# Controller.net
KiCad netlist of a schematic drawn in Altium Designer
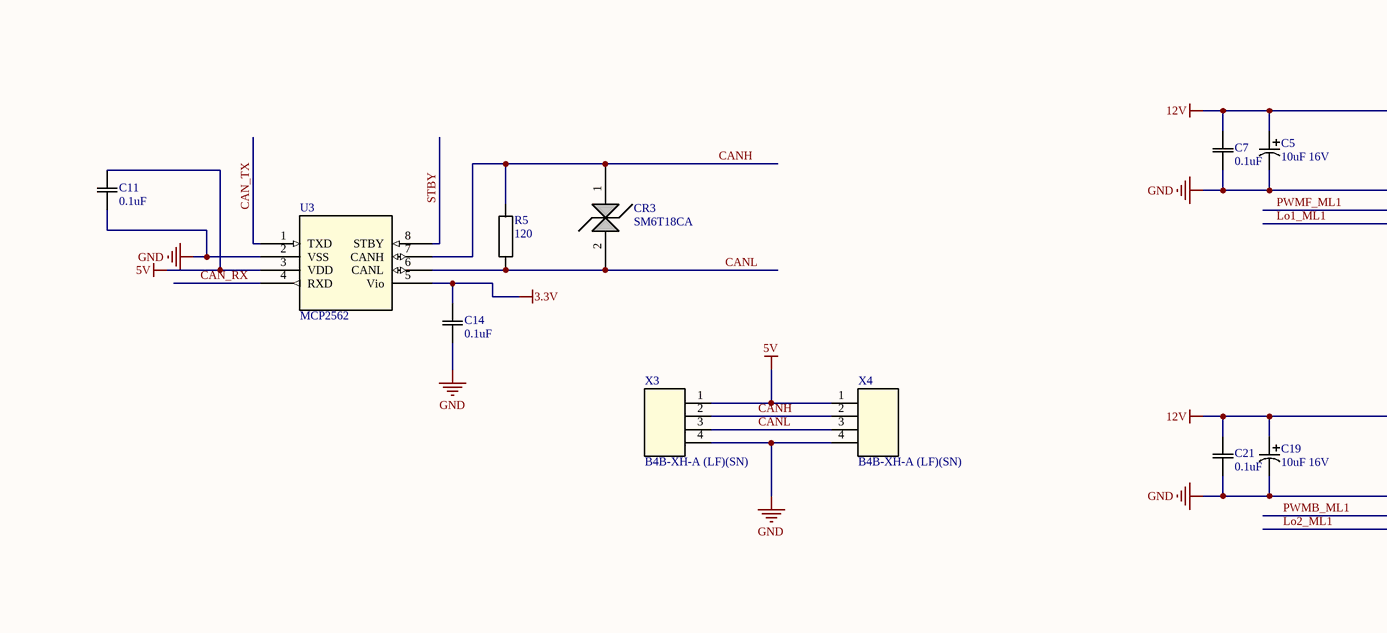
[diagram p0: Controller.SchDoc, top left]
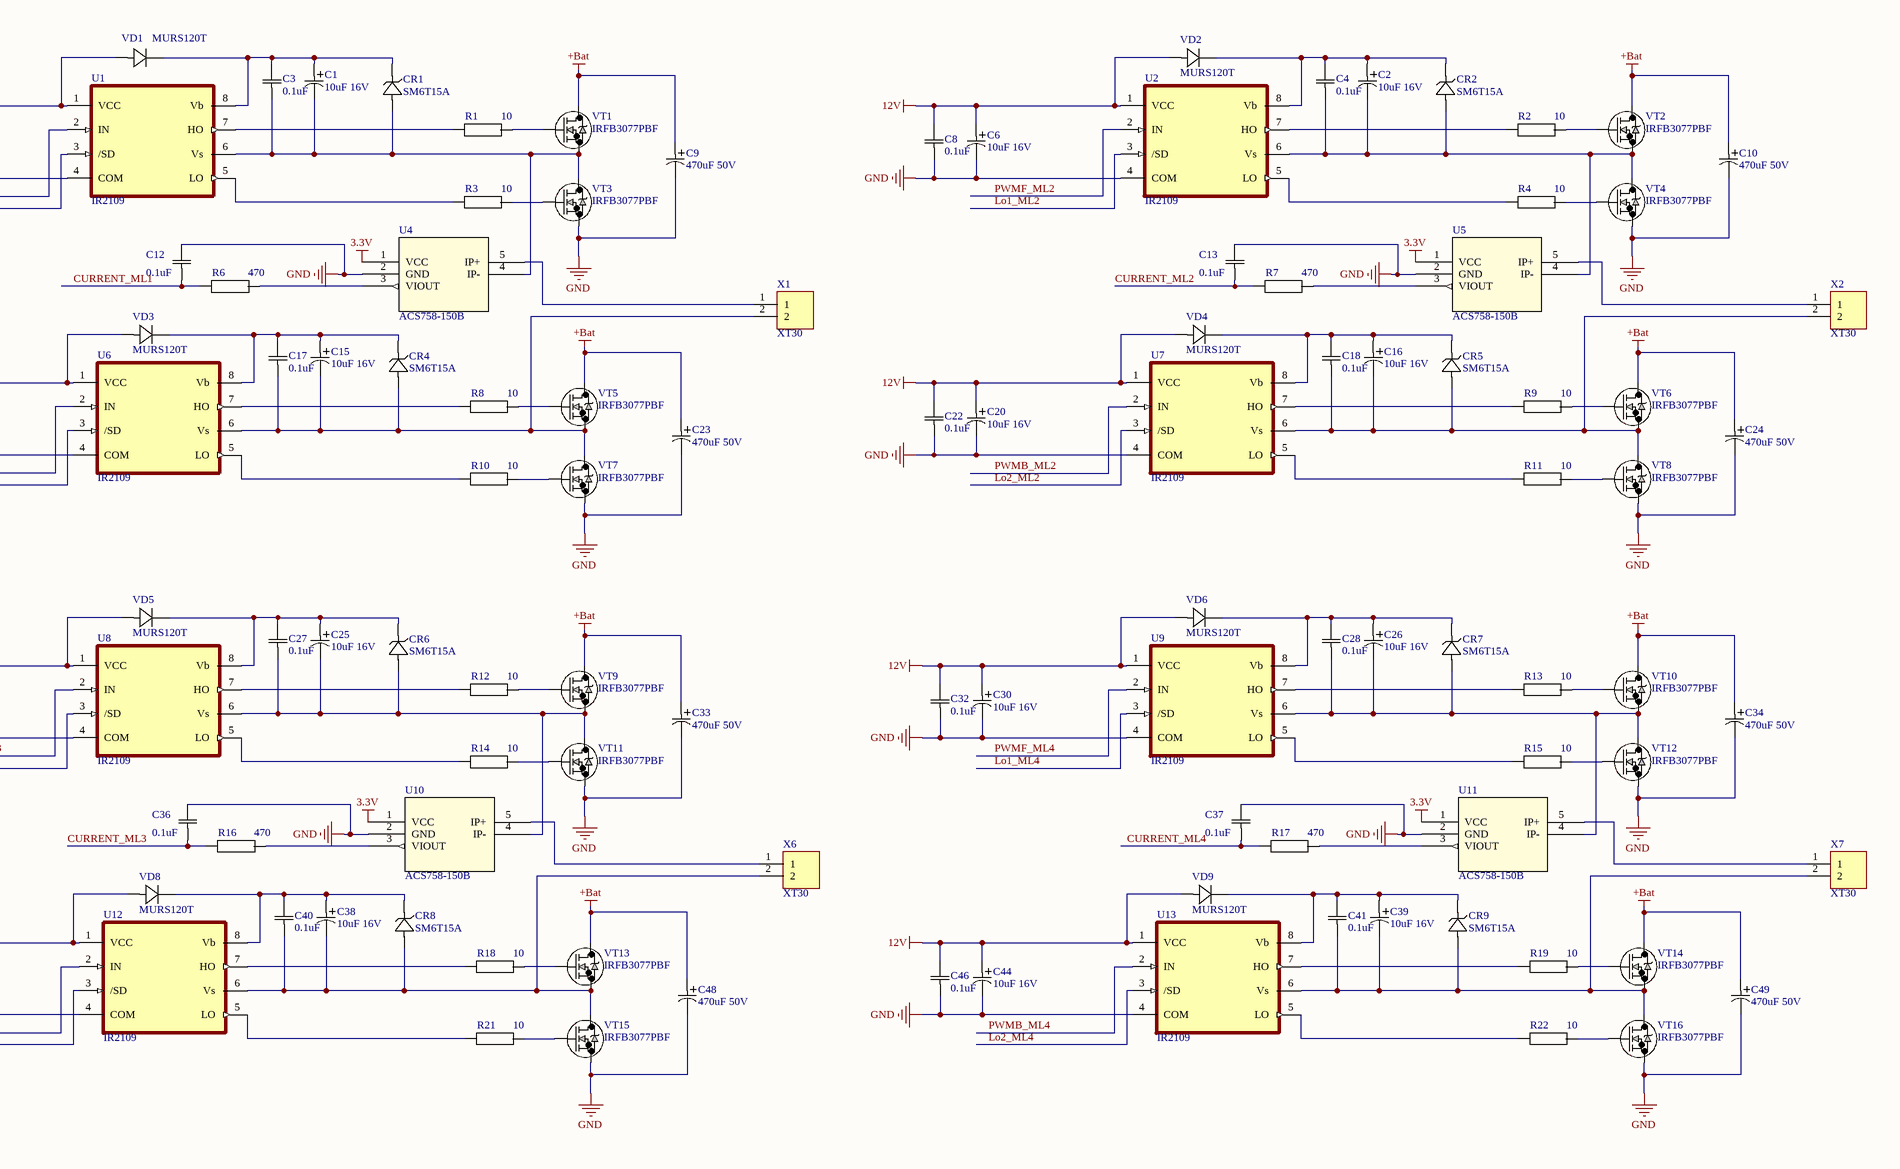
[diagram p1: Controller.SchDoc, top right]
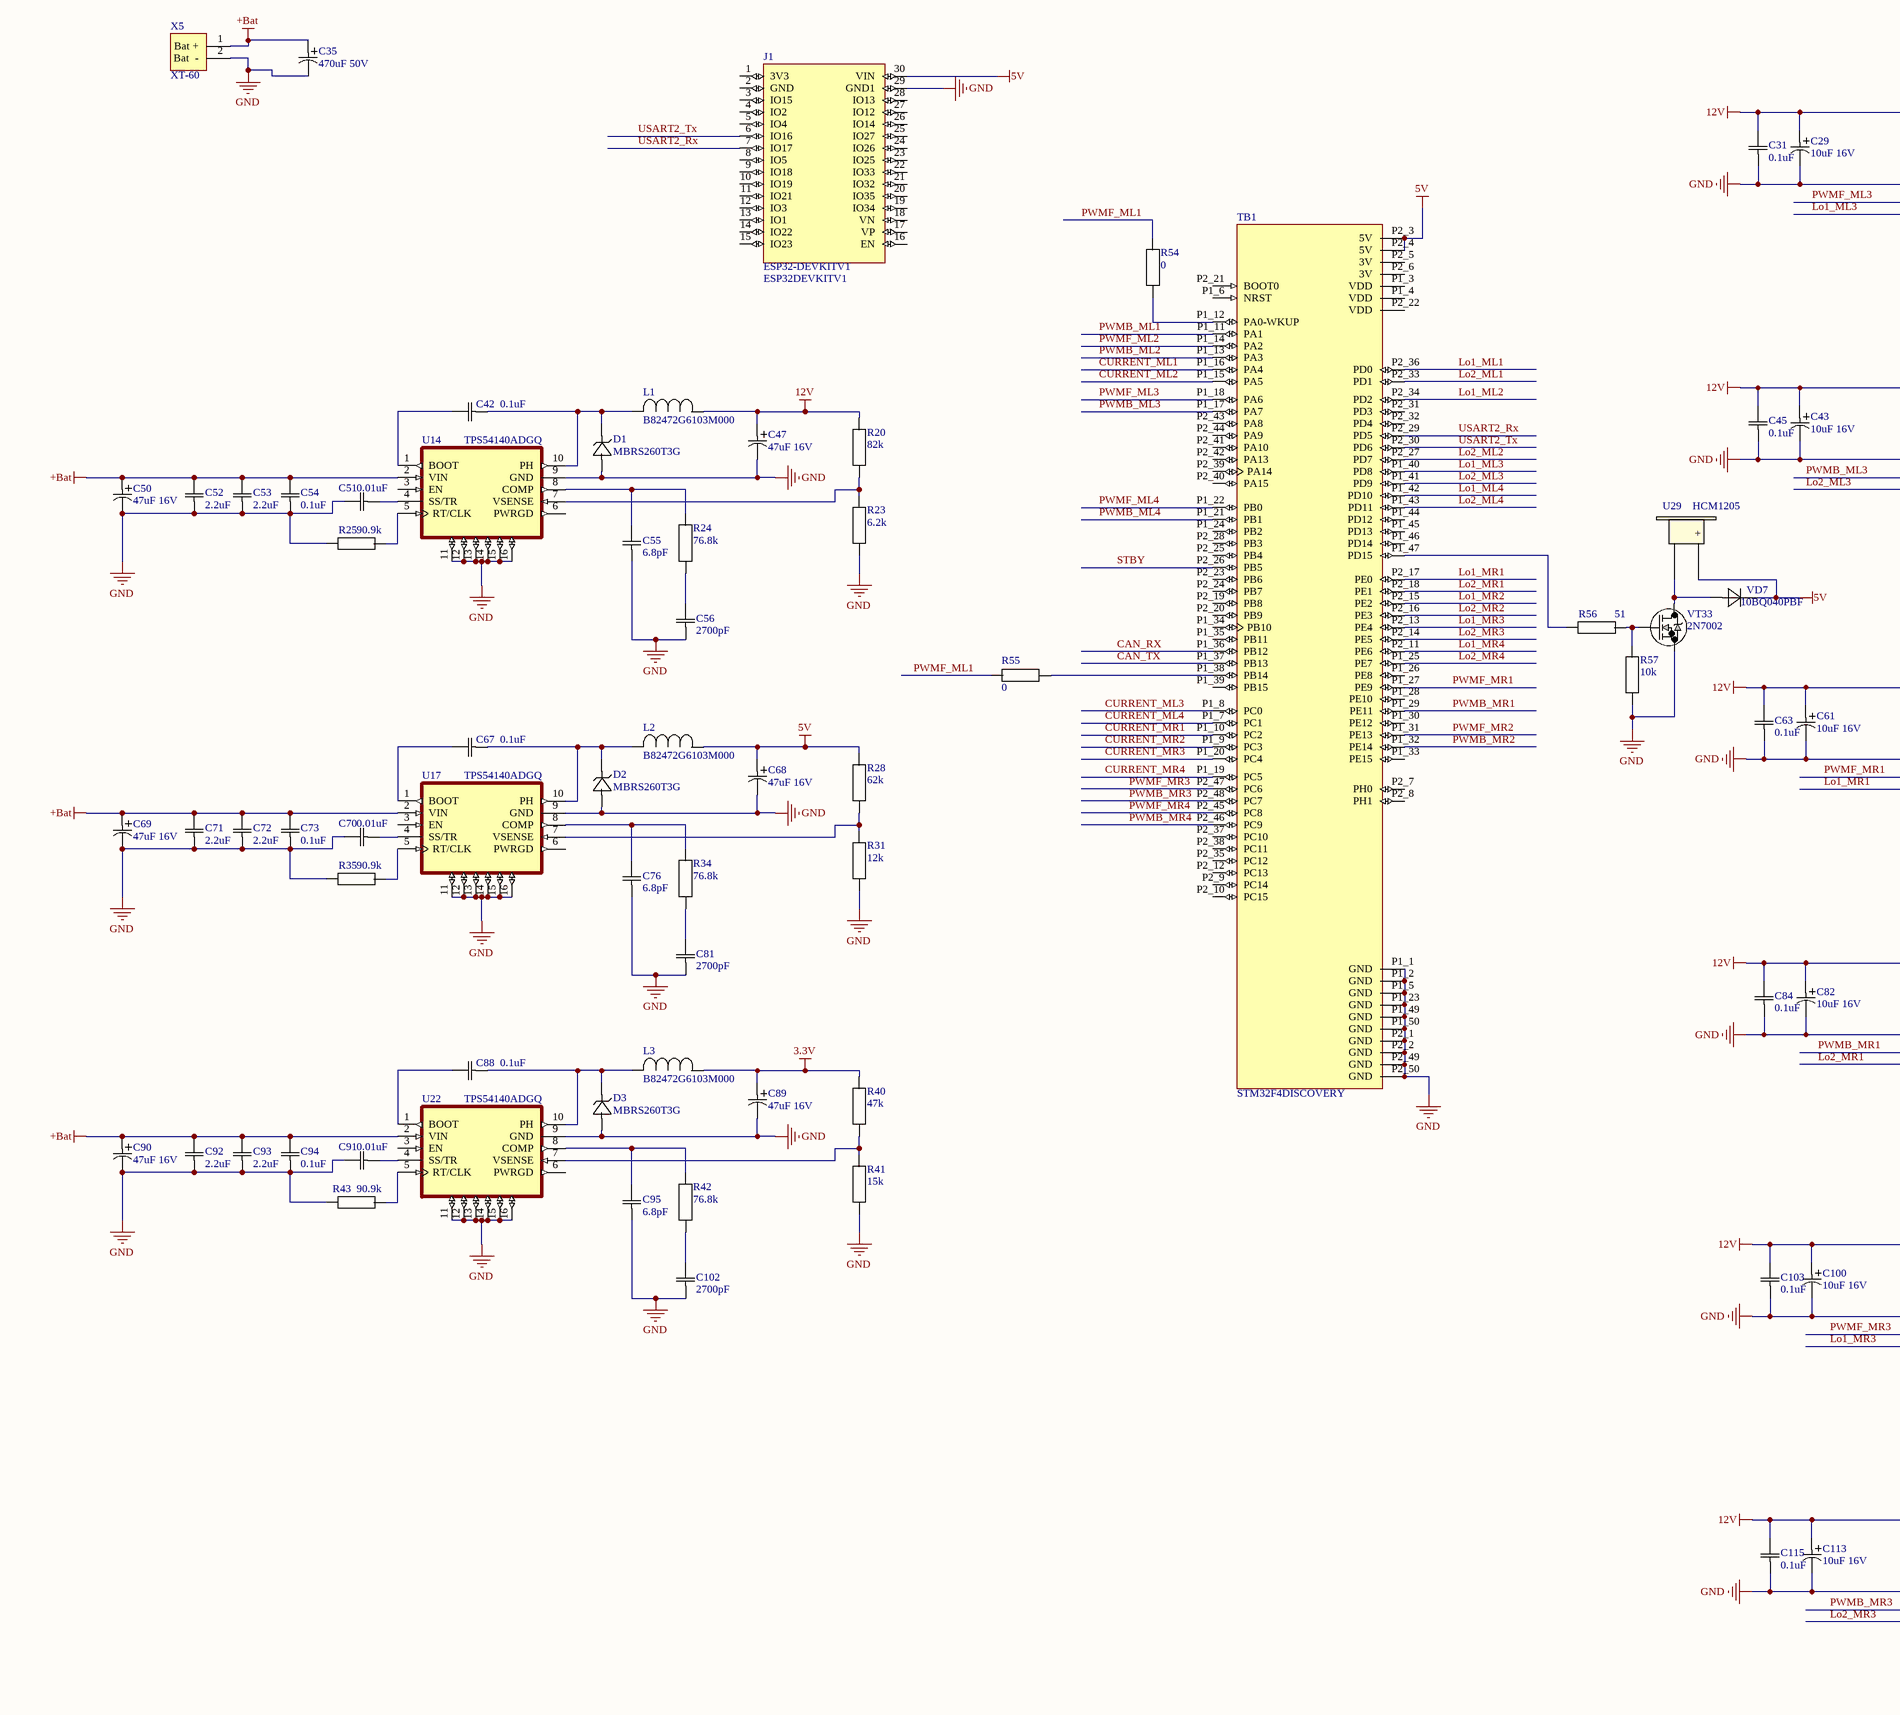
[diagram p2: Controller.SchDoc, bottom left]
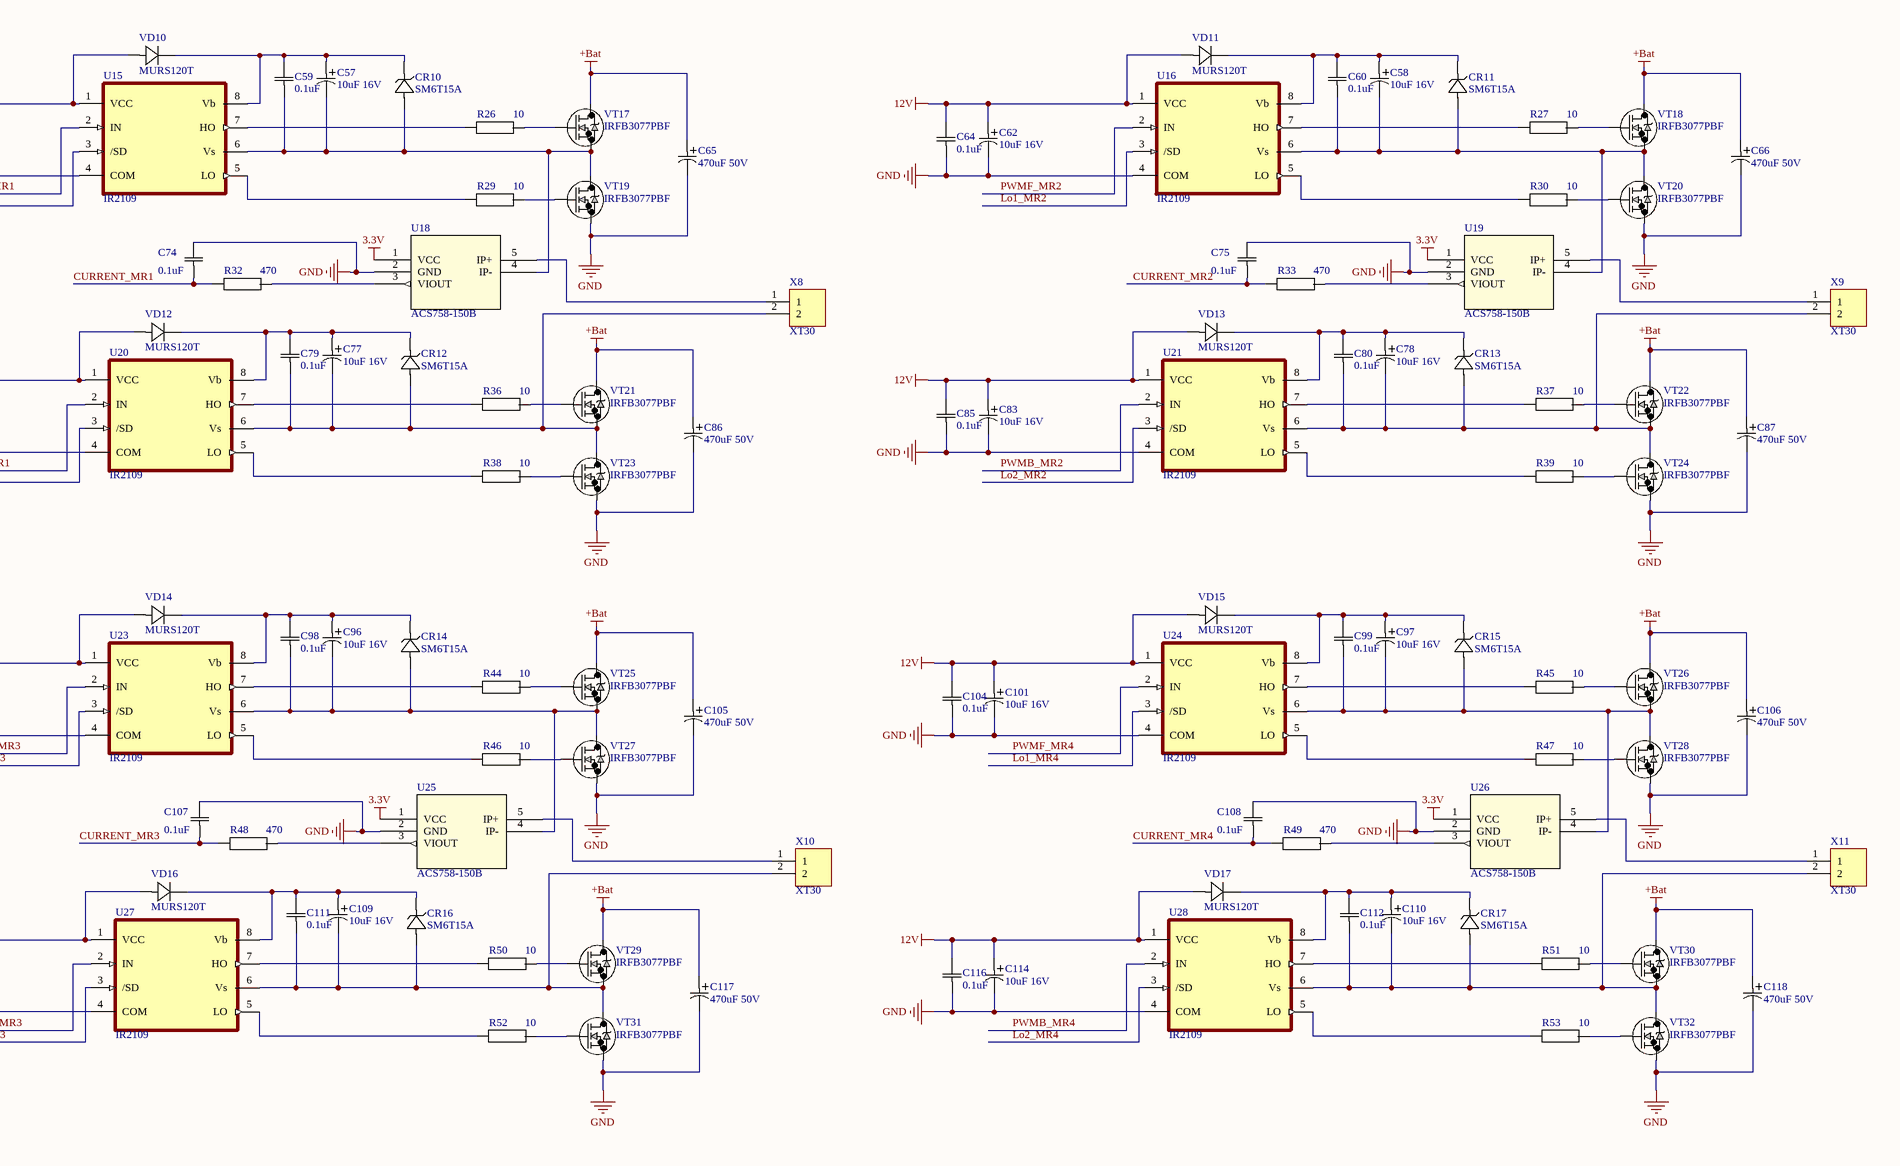
[diagram p3: Controller.SchDoc, bottom right]

(export (version "E")
  (design (tool "Eeschema 10.0.6"))
  (components
    (comp (ref "C1")
      (value "10uF 16V")
      (footprint "PCAP_5x11-THRU-E")
      (description "No Description Available")
      (fields
        (field (name "MANUFACTURER_PART_NUMBER") "UPS1C470MDD")
        (field (name "COPYRIGHT") "Copyright (C) 2018 Accelerated Designs. All rights reserved")
      )
      (libsource (lib "47u") (part "UPS1C470MDD"))
    )
    (comp (ref "C2")
      (value "10uF 16V")
      (footprint "PCAP_5x11-THRU-E")
      (description "No Description Available")
      (fields
        (field (name "MANUFACTURER_PART_NUMBER") "UPS1C470MDD")
        (field (name "COPYRIGHT") "Copyright (C) 2018 Accelerated Designs. All rights reserved")
      )
      (libsource (lib "47u") (part "UPS1C470MDD"))
    )
    (comp (ref "C3")
      (value "0.1uF")
      (footprint "0603")
      (description "No Description Available")
      (fields
        (field (name "MANUFACTURER_PART_NUMBER") "0603ZC224JAT2A")
        (field (name "COPYRIGHT") "Copyright (C) 2018 Accelerated Designs. All rights reserved")
      )
      (libsource (lib "Cap0603") (part "0603ZC224JAT2A"))
    )
    (comp (ref "C4")
      (value "0.1uF")
      (footprint "0603")
      (description "No Description Available")
      (fields
        (field (name "MANUFACTURER_PART_NUMBER") "0603ZC224JAT2A")
        (field (name "COPYRIGHT") "Copyright (C) 2018 Accelerated Designs. All rights reserved")
      )
      (libsource (lib "Cap0603") (part "0603ZC224JAT2A"))
    )
    (comp (ref "C5")
      (value "10uF 16V")
      (footprint "PCAP_5x11-THRU-E")
      (description "No Description Available")
      (fields
        (field (name "MANUFACTURER_PART_NUMBER") "UPS1C470MDD")
        (field (name "COPYRIGHT") "Copyright (C) 2018 Accelerated Designs. All rights reserved")
      )
      (libsource (lib "47u") (part "UPS1C470MDD"))
    )
    (comp (ref "C6")
      (value "10uF 16V")
      (footprint "PCAP_5x11-THRU-E")
      (description "No Description Available")
      (fields
        (field (name "MANUFACTURER_PART_NUMBER") "UPS1C470MDD")
        (field (name "COPYRIGHT") "Copyright (C) 2018 Accelerated Designs. All rights reserved")
      )
      (libsource (lib "47u") (part "UPS1C470MDD"))
    )
    (comp (ref "C7")
      (value "0.1uF")
      (footprint "0603")
      (description "No Description Available")
      (fields
        (field (name "MANUFACTURER_PART_NUMBER") "0603ZC224JAT2A")
        (field (name "COPYRIGHT") "Copyright (C) 2018 Accelerated Designs. All rights reserved")
      )
      (libsource (lib "Cap0603") (part "0603ZC224JAT2A"))
    )
    (comp (ref "C8")
      (value "0.1uF")
      (footprint "0603")
      (description "No Description Available")
      (fields
        (field (name "MANUFACTURER_PART_NUMBER") "0603ZC224JAT2A")
        (field (name "COPYRIGHT") "Copyright (C) 2018 Accelerated Designs. All rights reserved")
      )
      (libsource (lib "Cap0603") (part "0603ZC224JAT2A"))
    )
    (comp (ref "C9")
      (value "470uF 50V")
      (footprint "CAP_UAQ_12P5X20")
      (description "No Description Available")
      (fields
        (field (name "MANUFACTURER_PART_NUMBER") "UVR1H471MHD1TO")
        (field (name "COPYRIGHT") "Copyright (C) 2018 Accelerated Designs. All rights reserved")
      )
      (libsource (lib "470uF") (part "UVR1H471MHD1TO"))
    )
    (comp (ref "C10")
      (value "470uF 50V")
      (footprint "CAP_UAQ_12P5X20")
      (description "No Description Available")
      (fields
        (field (name "MANUFACTURER_PART_NUMBER") "UVR1H471MHD1TO")
        (field (name "COPYRIGHT") "Copyright (C) 2018 Accelerated Designs. All rights reserved")
      )
      (libsource (lib "470uF") (part "UVR1H471MHD1TO"))
    )
    (comp (ref "C11")
      (value "0.1uF")
      (footprint "0603")
      (description "No Description Available")
      (fields
        (field (name "MANUFACTURER_PART_NUMBER") "0603ZC224JAT2A")
        (field (name "COPYRIGHT") "Copyright (C) 2018 Accelerated Designs. All rights reserved")
      )
      (libsource (lib "Cap0603") (part "0603ZC224JAT2A"))
    )
    (comp (ref "C12")
      (value "0.1uF")
      (footprint "0603")
      (description "No Description Available")
      (fields
        (field (name "MANUFACTURER_PART_NUMBER") "0603ZC224JAT2A")
        (field (name "COPYRIGHT") "Copyright (C) 2018 Accelerated Designs. All rights reserved")
      )
      (libsource (lib "Cap0603") (part "0603ZC224JAT2A"))
    )
    (comp (ref "C13")
      (value "0.1uF")
      (footprint "0603")
      (description "No Description Available")
      (fields
        (field (name "MANUFACTURER_PART_NUMBER") "0603ZC224JAT2A")
        (field (name "COPYRIGHT") "Copyright (C) 2018 Accelerated Designs. All rights reserved")
      )
      (libsource (lib "Cap0603") (part "0603ZC224JAT2A"))
    )
    (comp (ref "C14")
      (value "0.1uF")
      (footprint "0603")
      (description "No Description Available")
      (fields
        (field (name "MANUFACTURER_PART_NUMBER") "0603ZC224JAT2A")
        (field (name "COPYRIGHT") "Copyright (C) 2018 Accelerated Designs. All rights reserved")
      )
      (libsource (lib "Cap0603") (part "0603ZC224JAT2A"))
    )
    (comp (ref "C15")
      (value "10uF 16V")
      (footprint "PCAP_5x11-THRU-E")
      (description "No Description Available")
      (fields
        (field (name "MANUFACTURER_PART_NUMBER") "UPS1C470MDD")
        (field (name "COPYRIGHT") "Copyright (C) 2018 Accelerated Designs. All rights reserved")
      )
      (libsource (lib "47u") (part "UPS1C470MDD"))
    )
    (comp (ref "C16")
      (value "10uF 16V")
      (footprint "PCAP_5x11-THRU-E")
      (description "No Description Available")
      (fields
        (field (name "MANUFACTURER_PART_NUMBER") "UPS1C470MDD")
        (field (name "COPYRIGHT") "Copyright (C) 2018 Accelerated Designs. All rights reserved")
      )
      (libsource (lib "47u") (part "UPS1C470MDD"))
    )
    (comp (ref "C17")
      (value "0.1uF")
      (footprint "0603")
      (description "No Description Available")
      (fields
        (field (name "MANUFACTURER_PART_NUMBER") "0603ZC224JAT2A")
        (field (name "COPYRIGHT") "Copyright (C) 2018 Accelerated Designs. All rights reserved")
      )
      (libsource (lib "Cap0603") (part "0603ZC224JAT2A"))
    )
    (comp (ref "C18")
      (value "0.1uF")
      (footprint "0603")
      (description "No Description Available")
      (fields
        (field (name "MANUFACTURER_PART_NUMBER") "0603ZC224JAT2A")
        (field (name "COPYRIGHT") "Copyright (C) 2018 Accelerated Designs. All rights reserved")
      )
      (libsource (lib "Cap0603") (part "0603ZC224JAT2A"))
    )
    (comp (ref "C19")
      (value "10uF 16V")
      (footprint "PCAP_5x11-THRU-E")
      (description "No Description Available")
      (fields
        (field (name "MANUFACTURER_PART_NUMBER") "UPS1C470MDD")
        (field (name "COPYRIGHT") "Copyright (C) 2018 Accelerated Designs. All rights reserved")
      )
      (libsource (lib "47u") (part "UPS1C470MDD"))
    )
    (comp (ref "C20")
      (value "10uF 16V")
      (footprint "PCAP_5x11-THRU-E")
      (description "No Description Available")
      (fields
        (field (name "MANUFACTURER_PART_NUMBER") "UPS1C470MDD")
        (field (name "COPYRIGHT") "Copyright (C) 2018 Accelerated Designs. All rights reserved")
      )
      (libsource (lib "47u") (part "UPS1C470MDD"))
    )
    (comp (ref "C21")
      (value "0.1uF")
      (footprint "0603")
      (description "No Description Available")
      (fields
        (field (name "MANUFACTURER_PART_NUMBER") "0603ZC224JAT2A")
        (field (name "COPYRIGHT") "Copyright (C) 2018 Accelerated Designs. All rights reserved")
      )
      (libsource (lib "Cap0603") (part "0603ZC224JAT2A"))
    )
    (comp (ref "C22")
      (value "0.1uF")
      (footprint "0603")
      (description "No Description Available")
      (fields
        (field (name "MANUFACTURER_PART_NUMBER") "0603ZC224JAT2A")
        (field (name "COPYRIGHT") "Copyright (C) 2018 Accelerated Designs. All rights reserved")
      )
      (libsource (lib "Cap0603") (part "0603ZC224JAT2A"))
    )
    (comp (ref "C23")
      (value "470uF 50V")
      (footprint "CAP_UAQ_12P5X20")
      (description "No Description Available")
      (fields
        (field (name "MANUFACTURER_PART_NUMBER") "UVR1H471MHD1TO")
        (field (name "COPYRIGHT") "Copyright (C) 2018 Accelerated Designs. All rights reserved")
      )
      (libsource (lib "470uF") (part "UVR1H471MHD1TO"))
    )
    (comp (ref "C24")
      (value "470uF 50V")
      (footprint "CAP_UAQ_12P5X20")
      (description "No Description Available")
      (fields
        (field (name "MANUFACTURER_PART_NUMBER") "UVR1H471MHD1TO")
        (field (name "COPYRIGHT") "Copyright (C) 2018 Accelerated Designs. All rights reserved")
      )
      (libsource (lib "470uF") (part "UVR1H471MHD1TO"))
    )
    (comp (ref "C25")
      (value "10uF 16V")
      (footprint "PCAP_5x11-THRU-E")
      (description "No Description Available")
      (fields
        (field (name "MANUFACTURER_PART_NUMBER") "UPS1C470MDD")
        (field (name "COPYRIGHT") "Copyright (C) 2018 Accelerated Designs. All rights reserved")
      )
      (libsource (lib "47u") (part "UPS1C470MDD"))
    )
    (comp (ref "C26")
      (value "10uF 16V")
      (footprint "PCAP_5x11-THRU-E")
      (description "No Description Available")
      (fields
        (field (name "MANUFACTURER_PART_NUMBER") "UPS1C470MDD")
        (field (name "COPYRIGHT") "Copyright (C) 2018 Accelerated Designs. All rights reserved")
      )
      (libsource (lib "47u") (part "UPS1C470MDD"))
    )
    (comp (ref "C27")
      (value "0.1uF")
      (footprint "0603")
      (description "No Description Available")
      (fields
        (field (name "MANUFACTURER_PART_NUMBER") "0603ZC224JAT2A")
        (field (name "COPYRIGHT") "Copyright (C) 2018 Accelerated Designs. All rights reserved")
      )
      (libsource (lib "Cap0603") (part "0603ZC224JAT2A"))
    )
    (comp (ref "C28")
      (value "0.1uF")
      (footprint "0603")
      (description "No Description Available")
      (fields
        (field (name "MANUFACTURER_PART_NUMBER") "0603ZC224JAT2A")
        (field (name "COPYRIGHT") "Copyright (C) 2018 Accelerated Designs. All rights reserved")
      )
      (libsource (lib "Cap0603") (part "0603ZC224JAT2A"))
    )
    (comp (ref "C29")
      (value "10uF 16V")
      (footprint "PCAP_5x11-THRU-E")
      (description "No Description Available")
      (fields
        (field (name "MANUFACTURER_PART_NUMBER") "UPS1C470MDD")
        (field (name "COPYRIGHT") "Copyright (C) 2018 Accelerated Designs. All rights reserved")
      )
      (libsource (lib "47u") (part "UPS1C470MDD"))
    )
    (comp (ref "C30")
      (value "10uF 16V")
      (footprint "PCAP_5x11-THRU-E")
      (description "No Description Available")
      (fields
        (field (name "MANUFACTURER_PART_NUMBER") "UPS1C470MDD")
        (field (name "COPYRIGHT") "Copyright (C) 2018 Accelerated Designs. All rights reserved")
      )
      (libsource (lib "47u") (part "UPS1C470MDD"))
    )
    (comp (ref "C31")
      (value "0.1uF")
      (footprint "0603")
      (description "No Description Available")
      (fields
        (field (name "MANUFACTURER_PART_NUMBER") "0603ZC224JAT2A")
        (field (name "COPYRIGHT") "Copyright (C) 2018 Accelerated Designs. All rights reserved")
      )
      (libsource (lib "Cap0603") (part "0603ZC224JAT2A"))
    )
    (comp (ref "C32")
      (value "0.1uF")
      (footprint "0603")
      (description "No Description Available")
      (fields
        (field (name "MANUFACTURER_PART_NUMBER") "0603ZC224JAT2A")
        (field (name "COPYRIGHT") "Copyright (C) 2018 Accelerated Designs. All rights reserved")
      )
      (libsource (lib "Cap0603") (part "0603ZC224JAT2A"))
    )
    (comp (ref "C33")
      (value "470uF 50V")
      (footprint "CAP_UAQ_12P5X20")
      (description "No Description Available")
      (fields
        (field (name "MANUFACTURER_PART_NUMBER") "UVR1H471MHD1TO")
        (field (name "COPYRIGHT") "Copyright (C) 2018 Accelerated Designs. All rights reserved")
      )
      (libsource (lib "470uF") (part "UVR1H471MHD1TO"))
    )
    (comp (ref "C34")
      (value "470uF 50V")
      (footprint "CAP_UAQ_12P5X20")
      (description "No Description Available")
      (fields
        (field (name "MANUFACTURER_PART_NUMBER") "UVR1H471MHD1TO")
        (field (name "COPYRIGHT") "Copyright (C) 2018 Accelerated Designs. All rights reserved")
      )
      (libsource (lib "470uF") (part "UVR1H471MHD1TO"))
    )
    (comp (ref "C35")
      (value "470uF 50V")
      (footprint "CAP_UAQ_12P5X20")
      (description "No Description Available")
      (fields
        (field (name "MANUFACTURER_PART_NUMBER") "UVR1H471MHD1TO")
        (field (name "COPYRIGHT") "Copyright (C) 2018 Accelerated Designs. All rights reserved")
      )
      (libsource (lib "470uF") (part "UVR1H471MHD1TO"))
    )
    (comp (ref "C36")
      (value "0.1uF")
      (footprint "0603")
      (description "No Description Available")
      (fields
        (field (name "MANUFACTURER_PART_NUMBER") "0603ZC224JAT2A")
        (field (name "COPYRIGHT") "Copyright (C) 2018 Accelerated Designs. All rights reserved")
      )
      (libsource (lib "Cap0603") (part "0603ZC224JAT2A"))
    )
    (comp (ref "C37")
      (value "0.1uF")
      (footprint "0603")
      (description "No Description Available")
      (fields
        (field (name "MANUFACTURER_PART_NUMBER") "0603ZC224JAT2A")
        (field (name "COPYRIGHT") "Copyright (C) 2018 Accelerated Designs. All rights reserved")
      )
      (libsource (lib "Cap0603") (part "0603ZC224JAT2A"))
    )
    (comp (ref "C38")
      (value "10uF 16V")
      (footprint "PCAP_5x11-THRU-E")
      (description "No Description Available")
      (fields
        (field (name "MANUFACTURER_PART_NUMBER") "UPS1C470MDD")
        (field (name "COPYRIGHT") "Copyright (C) 2018 Accelerated Designs. All rights reserved")
      )
      (libsource (lib "47u") (part "UPS1C470MDD"))
    )
    (comp (ref "C39")
      (value "10uF 16V")
      (footprint "PCAP_5x11-THRU-E")
      (description "No Description Available")
      (fields
        (field (name "MANUFACTURER_PART_NUMBER") "UPS1C470MDD")
        (field (name "COPYRIGHT") "Copyright (C) 2018 Accelerated Designs. All rights reserved")
      )
      (libsource (lib "47u") (part "UPS1C470MDD"))
    )
    (comp (ref "C40")
      (value "0.1uF")
      (footprint "0603")
      (description "No Description Available")
      (fields
        (field (name "MANUFACTURER_PART_NUMBER") "0603ZC224JAT2A")
        (field (name "COPYRIGHT") "Copyright (C) 2018 Accelerated Designs. All rights reserved")
      )
      (libsource (lib "Cap0603") (part "0603ZC224JAT2A"))
    )
    (comp (ref "C41")
      (value "0.1uF")
      (footprint "0603")
      (description "No Description Available")
      (fields
        (field (name "MANUFACTURER_PART_NUMBER") "0603ZC224JAT2A")
        (field (name "COPYRIGHT") "Copyright (C) 2018 Accelerated Designs. All rights reserved")
      )
      (libsource (lib "Cap0603") (part "0603ZC224JAT2A"))
    )
    (comp (ref "C42")
      (value "0.1uF")
      (footprint "0603")
      (description "No Description Available")
      (fields
        (field (name "MANUFACTURER_PART_NUMBER") "0603ZC224JAT2A")
        (field (name "COPYRIGHT") "Copyright (C) 2018 Accelerated Designs. All rights reserved")
      )
      (libsource (lib "Cap0603") (part "0603ZC224JAT2A"))
    )
    (comp (ref "C43")
      (value "10uF 16V")
      (footprint "PCAP_5x11-THRU-E")
      (description "No Description Available")
      (fields
        (field (name "MANUFACTURER_PART_NUMBER") "UPS1C470MDD")
        (field (name "COPYRIGHT") "Copyright (C) 2018 Accelerated Designs. All rights reserved")
      )
      (libsource (lib "47u") (part "UPS1C470MDD"))
    )
    (comp (ref "C44")
      (value "10uF 16V")
      (footprint "PCAP_5x11-THRU-E")
      (description "No Description Available")
      (fields
        (field (name "MANUFACTURER_PART_NUMBER") "UPS1C470MDD")
        (field (name "COPYRIGHT") "Copyright (C) 2018 Accelerated Designs. All rights reserved")
      )
      (libsource (lib "47u") (part "UPS1C470MDD"))
    )
    (comp (ref "C45")
      (value "0.1uF")
      (footprint "0603")
      (description "No Description Available")
      (fields
        (field (name "MANUFACTURER_PART_NUMBER") "0603ZC224JAT2A")
        (field (name "COPYRIGHT") "Copyright (C) 2018 Accelerated Designs. All rights reserved")
      )
      (libsource (lib "Cap0603") (part "0603ZC224JAT2A"))
    )
    (comp (ref "C46")
      (value "0.1uF")
      (footprint "0603")
      (description "No Description Available")
      (fields
        (field (name "MANUFACTURER_PART_NUMBER") "0603ZC224JAT2A")
        (field (name "COPYRIGHT") "Copyright (C) 2018 Accelerated Designs. All rights reserved")
      )
      (libsource (lib "Cap0603") (part "0603ZC224JAT2A"))
    )
    (comp (ref "C47")
      (value "47uF 16V")
      (footprint "PCAP_5x11-THRU-E")
      (description "No Description Available")
      (fields
        (field (name "MANUFACTURER_PART_NUMBER") "UPS1C470MDD")
        (field (name "COPYRIGHT") "Copyright (C) 2018 Accelerated Designs. All rights reserved")
      )
      (libsource (lib "47u") (part "UPS1C470MDD"))
    )
    (comp (ref "C48")
      (value "470uF 50V")
      (footprint "CAP_UAQ_12P5X20")
      (description "No Description Available")
      (fields
        (field (name "MANUFACTURER_PART_NUMBER") "UVR1H471MHD1TO")
        (field (name "COPYRIGHT") "Copyright (C) 2018 Accelerated Designs. All rights reserved")
      )
      (libsource (lib "470uF") (part "UVR1H471MHD1TO"))
    )
    (comp (ref "C49")
      (value "470uF 50V")
      (footprint "CAP_UAQ_12P5X20")
      (description "No Description Available")
      (fields
        (field (name "MANUFACTURER_PART_NUMBER") "UVR1H471MHD1TO")
        (field (name "COPYRIGHT") "Copyright (C) 2018 Accelerated Designs. All rights reserved")
      )
      (libsource (lib "470uF") (part "UVR1H471MHD1TO"))
    )
    (comp (ref "C50")
      (value "47uF 16V")
      (footprint "PCAP_5x11-THRU-E")
      (description "No Description Available")
      (fields
        (field (name "MANUFACTURER_PART_NUMBER") "UPS1C470MDD")
        (field (name "COPYRIGHT") "Copyright (C) 2018 Accelerated Designs. All rights reserved")
      )
      (libsource (lib "47u") (part "UPS1C470MDD"))
    )
    (comp (ref "C51")
      (value "0.01uF")
      (footprint "0603")
      (description "No Description Available")
      (fields
        (field (name "MANUFACTURER_PART_NUMBER") "0603ZC224JAT2A")
        (field (name "COPYRIGHT") "Copyright (C) 2018 Accelerated Designs. All rights reserved")
      )
      (libsource (lib "Cap0603") (part "0603ZC224JAT2A"))
    )
    (comp (ref "C52")
      (value "2.2uF")
      (footprint "CAP_0805J_AVX")
      (description "No Description Available")
      (fields
        (field (name "MANUFACTURER_PART_NUMBER") "08051A102JAT2A")
        (field (name "COPYRIGHT") "Copyright (C) 2018 Accelerated Designs. All rights reserved")
      )
      (libsource (lib "Cap0805") (part "08051A102JAT2A"))
    )
    (comp (ref "C53")
      (value "2.2uF")
      (footprint "CAP_0805J_AVX")
      (description "No Description Available")
      (fields
        (field (name "MANUFACTURER_PART_NUMBER") "08051A102JAT2A")
        (field (name "COPYRIGHT") "Copyright (C) 2018 Accelerated Designs. All rights reserved")
      )
      (libsource (lib "Cap0805") (part "08051A102JAT2A"))
    )
    (comp (ref "C54")
      (value "0.1uF")
      (footprint "0603")
      (description "No Description Available")
      (fields
        (field (name "MANUFACTURER_PART_NUMBER") "0603ZC224JAT2A")
        (field (name "COPYRIGHT") "Copyright (C) 2018 Accelerated Designs. All rights reserved")
      )
      (libsource (lib "Cap0603") (part "0603ZC224JAT2A"))
    )
    (comp (ref "C55")
      (value "6.8pF")
      (footprint "0603")
      (description "No Description Available")
      (fields
        (field (name "MANUFACTURER_PART_NUMBER") "0603ZC224JAT2A")
        (field (name "COPYRIGHT") "Copyright (C) 2018 Accelerated Designs. All rights reserved")
      )
      (libsource (lib "Cap0603") (part "0603ZC224JAT2A"))
    )
    (comp (ref "C56")
      (value "2700pF")
      (footprint "0603")
      (description "No Description Available")
      (fields
        (field (name "MANUFACTURER_PART_NUMBER") "0603ZC224JAT2A")
        (field (name "COPYRIGHT") "Copyright (C) 2018 Accelerated Designs. All rights reserved")
      )
      (libsource (lib "Cap0603") (part "0603ZC224JAT2A"))
    )
    (comp (ref "C57")
      (value "10uF 16V")
      (footprint "PCAP_5x11-THRU-E")
      (description "No Description Available")
      (fields
        (field (name "MANUFACTURER_PART_NUMBER") "UPS1C470MDD")
        (field (name "COPYRIGHT") "Copyright (C) 2018 Accelerated Designs. All rights reserved")
      )
      (libsource (lib "47u") (part "UPS1C470MDD"))
    )
    (comp (ref "C58")
      (value "10uF 16V")
      (footprint "PCAP_5x11-THRU-E")
      (description "No Description Available")
      (fields
        (field (name "MANUFACTURER_PART_NUMBER") "UPS1C470MDD")
        (field (name "COPYRIGHT") "Copyright (C) 2018 Accelerated Designs. All rights reserved")
      )
      (libsource (lib "47u") (part "UPS1C470MDD"))
    )
    (comp (ref "C59")
      (value "0.1uF")
      (footprint "0603")
      (description "No Description Available")
      (fields
        (field (name "MANUFACTURER_PART_NUMBER") "0603ZC224JAT2A")
        (field (name "COPYRIGHT") "Copyright (C) 2018 Accelerated Designs. All rights reserved")
      )
      (libsource (lib "Cap0603") (part "0603ZC224JAT2A"))
    )
    (comp (ref "C60")
      (value "0.1uF")
      (footprint "0603")
      (description "No Description Available")
      (fields
        (field (name "MANUFACTURER_PART_NUMBER") "0603ZC224JAT2A")
        (field (name "COPYRIGHT") "Copyright (C) 2018 Accelerated Designs. All rights reserved")
      )
      (libsource (lib "Cap0603") (part "0603ZC224JAT2A"))
    )
    (comp (ref "C61")
      (value "10uF 16V")
      (footprint "PCAP_5x11-THRU-E")
      (description "No Description Available")
      (fields
        (field (name "MANUFACTURER_PART_NUMBER") "UPS1C470MDD")
        (field (name "COPYRIGHT") "Copyright (C) 2018 Accelerated Designs. All rights reserved")
      )
      (libsource (lib "47u") (part "UPS1C470MDD"))
    )
    (comp (ref "C62")
      (value "10uF 16V")
      (footprint "PCAP_5x11-THRU-E")
      (description "No Description Available")
      (fields
        (field (name "MANUFACTURER_PART_NUMBER") "UPS1C470MDD")
        (field (name "COPYRIGHT") "Copyright (C) 2018 Accelerated Designs. All rights reserved")
      )
      (libsource (lib "47u") (part "UPS1C470MDD"))
    )
    (comp (ref "C63")
      (value "0.1uF")
      (footprint "0603")
      (description "No Description Available")
      (fields
        (field (name "MANUFACTURER_PART_NUMBER") "0603ZC224JAT2A")
        (field (name "COPYRIGHT") "Copyright (C) 2018 Accelerated Designs. All rights reserved")
      )
      (libsource (lib "Cap0603") (part "0603ZC224JAT2A"))
    )
    (comp (ref "C64")
      (value "0.1uF")
      (footprint "0603")
      (description "No Description Available")
      (fields
        (field (name "MANUFACTURER_PART_NUMBER") "0603ZC224JAT2A")
        (field (name "COPYRIGHT") "Copyright (C) 2018 Accelerated Designs. All rights reserved")
      )
      (libsource (lib "Cap0603") (part "0603ZC224JAT2A"))
    )
    (comp (ref "C65")
      (value "470uF 50V")
      (footprint "CAP_UAQ_12P5X20")
      (description "No Description Available")
      (fields
        (field (name "MANUFACTURER_PART_NUMBER") "UVR1H471MHD1TO")
        (field (name "COPYRIGHT") "Copyright (C) 2018 Accelerated Designs. All rights reserved")
      )
      (libsource (lib "470uF") (part "UVR1H471MHD1TO"))
    )
    (comp (ref "C66")
      (value "470uF 50V")
      (footprint "CAP_UAQ_12P5X20")
      (description "No Description Available")
      (fields
        (field (name "MANUFACTURER_PART_NUMBER") "UVR1H471MHD1TO")
        (field (name "COPYRIGHT") "Copyright (C) 2018 Accelerated Designs. All rights reserved")
      )
      (libsource (lib "470uF") (part "UVR1H471MHD1TO"))
    )
    (comp (ref "C67")
      (value "0.1uF")
      (footprint "0603")
      (description "No Description Available")
      (fields
        (field (name "MANUFACTURER_PART_NUMBER") "0603ZC224JAT2A")
        (field (name "COPYRIGHT") "Copyright (C) 2018 Accelerated Designs. All rights reserved")
      )
      (libsource (lib "Cap0603") (part "0603ZC224JAT2A"))
    )
    (comp (ref "C68")
      (value "47uF 16V")
      (footprint "PCAP_5x11-THRU-E")
      (description "No Description Available")
      (fields
        (field (name "MANUFACTURER_PART_NUMBER") "UPS1C470MDD")
        (field (name "COPYRIGHT") "Copyright (C) 2018 Accelerated Designs. All rights reserved")
      )
      (libsource (lib "47u") (part "UPS1C470MDD"))
    )
    (comp (ref "C69")
      (value "47uF 16V")
      (footprint "PCAP_5x11-THRU-E")
      (description "No Description Available")
      (fields
        (field (name "MANUFACTURER_PART_NUMBER") "UPS1C470MDD")
        (field (name "COPYRIGHT") "Copyright (C) 2018 Accelerated Designs. All rights reserved")
      )
      (libsource (lib "47u") (part "UPS1C470MDD"))
    )
    (comp (ref "C70")
      (value "0.01uF")
      (footprint "0603")
      (description "No Description Available")
      (fields
        (field (name "MANUFACTURER_PART_NUMBER") "0603ZC224JAT2A")
        (field (name "COPYRIGHT") "Copyright (C) 2018 Accelerated Designs. All rights reserved")
      )
      (libsource (lib "Cap0603") (part "0603ZC224JAT2A"))
    )
    (comp (ref "C71")
      (value "2.2uF")
      (footprint "CAP_0805J_AVX")
      (description "No Description Available")
      (fields
        (field (name "MANUFACTURER_PART_NUMBER") "08051A102JAT2A")
        (field (name "COPYRIGHT") "Copyright (C) 2018 Accelerated Designs. All rights reserved")
      )
      (libsource (lib "Cap0805") (part "08051A102JAT2A"))
    )
    (comp (ref "C72")
      (value "2.2uF")
      (footprint "CAP_0805J_AVX")
      (description "No Description Available")
      (fields
        (field (name "MANUFACTURER_PART_NUMBER") "08051A102JAT2A")
        (field (name "COPYRIGHT") "Copyright (C) 2018 Accelerated Designs. All rights reserved")
      )
      (libsource (lib "Cap0805") (part "08051A102JAT2A"))
    )
    (comp (ref "C73")
      (value "0.1uF")
      (footprint "0603")
      (description "No Description Available")
      (fields
        (field (name "MANUFACTURER_PART_NUMBER") "0603ZC224JAT2A")
        (field (name "COPYRIGHT") "Copyright (C) 2018 Accelerated Designs. All rights reserved")
      )
      (libsource (lib "Cap0603") (part "0603ZC224JAT2A"))
    )
    (comp (ref "C74")
      (value "0.1uF")
      (footprint "0603")
      (description "No Description Available")
      (fields
        (field (name "MANUFACTURER_PART_NUMBER") "0603ZC224JAT2A")
        (field (name "COPYRIGHT") "Copyright (C) 2018 Accelerated Designs. All rights reserved")
      )
      (libsource (lib "Cap0603") (part "0603ZC224JAT2A"))
    )
    (comp (ref "C75")
      (value "0.1uF")
      (footprint "0603")
      (description "No Description Available")
      (fields
        (field (name "MANUFACTURER_PART_NUMBER") "0603ZC224JAT2A")
        (field (name "COPYRIGHT") "Copyright (C) 2018 Accelerated Designs. All rights reserved")
      )
      (libsource (lib "Cap0603") (part "0603ZC224JAT2A"))
    )
    (comp (ref "C76")
      (value "6.8pF")
      (footprint "0603")
      (description "No Description Available")
      (fields
        (field (name "MANUFACTURER_PART_NUMBER") "0603ZC224JAT2A")
        (field (name "COPYRIGHT") "Copyright (C) 2018 Accelerated Designs. All rights reserved")
      )
      (libsource (lib "Cap0603") (part "0603ZC224JAT2A"))
    )
    (comp (ref "C77")
      (value "10uF 16V")
      (footprint "PCAP_5x11-THRU-E")
      (description "No Description Available")
      (fields
        (field (name "MANUFACTURER_PART_NUMBER") "UPS1C470MDD")
        (field (name "COPYRIGHT") "Copyright (C) 2018 Accelerated Designs. All rights reserved")
      )
      (libsource (lib "47u") (part "UPS1C470MDD"))
    )
    (comp (ref "C78")
      (value "10uF 16V")
      (footprint "PCAP_5x11-THRU-E")
      (description "No Description Available")
      (fields
        (field (name "MANUFACTURER_PART_NUMBER") "UPS1C470MDD")
        (field (name "COPYRIGHT") "Copyright (C) 2018 Accelerated Designs. All rights reserved")
      )
      (libsource (lib "47u") (part "UPS1C470MDD"))
    )
    (comp (ref "C79")
      (value "0.1uF")
      (footprint "0603")
      (description "No Description Available")
      (fields
        (field (name "MANUFACTURER_PART_NUMBER") "0603ZC224JAT2A")
        (field (name "COPYRIGHT") "Copyright (C) 2018 Accelerated Designs. All rights reserved")
      )
      (libsource (lib "Cap0603") (part "0603ZC224JAT2A"))
    )
    (comp (ref "C80")
      (value "0.1uF")
      (footprint "0603")
      (description "No Description Available")
      (fields
        (field (name "MANUFACTURER_PART_NUMBER") "0603ZC224JAT2A")
        (field (name "COPYRIGHT") "Copyright (C) 2018 Accelerated Designs. All rights reserved")
      )
      (libsource (lib "Cap0603") (part "0603ZC224JAT2A"))
    )
    (comp (ref "C81")
      (value "2700pF")
      (footprint "0603")
      (description "No Description Available")
      (fields
        (field (name "MANUFACTURER_PART_NUMBER") "0603ZC224JAT2A")
        (field (name "COPYRIGHT") "Copyright (C) 2018 Accelerated Designs. All rights reserved")
      )
      (libsource (lib "Cap0603") (part "0603ZC224JAT2A"))
    )
    (comp (ref "C82")
      (value "10uF 16V")
      (footprint "PCAP_5x11-THRU-E")
      (description "No Description Available")
      (fields
        (field (name "MANUFACTURER_PART_NUMBER") "UPS1C470MDD")
        (field (name "COPYRIGHT") "Copyright (C) 2018 Accelerated Designs. All rights reserved")
      )
      (libsource (lib "47u") (part "UPS1C470MDD"))
    )
    (comp (ref "C83")
      (value "10uF 16V")
      (footprint "PCAP_5x11-THRU-E")
      (description "No Description Available")
      (fields
        (field (name "MANUFACTURER_PART_NUMBER") "UPS1C470MDD")
        (field (name "COPYRIGHT") "Copyright (C) 2018 Accelerated Designs. All rights reserved")
      )
      (libsource (lib "47u") (part "UPS1C470MDD"))
    )
    (comp (ref "C84")
      (value "0.1uF")
      (footprint "0603")
      (description "No Description Available")
      (fields
        (field (name "MANUFACTURER_PART_NUMBER") "0603ZC224JAT2A")
        (field (name "COPYRIGHT") "Copyright (C) 2018 Accelerated Designs. All rights reserved")
      )
      (libsource (lib "Cap0603") (part "0603ZC224JAT2A"))
    )
    (comp (ref "C85")
      (value "0.1uF")
      (footprint "0603")
      (description "No Description Available")
      (fields
        (field (name "MANUFACTURER_PART_NUMBER") "0603ZC224JAT2A")
        (field (name "COPYRIGHT") "Copyright (C) 2018 Accelerated Designs. All rights reserved")
      )
      (libsource (lib "Cap0603") (part "0603ZC224JAT2A"))
    )
    (comp (ref "C86")
      (value "470uF 50V")
      (footprint "CAP_UAQ_12P5X20")
      (description "No Description Available")
      (fields
        (field (name "MANUFACTURER_PART_NUMBER") "UVR1H471MHD1TO")
        (field (name "COPYRIGHT") "Copyright (C) 2018 Accelerated Designs. All rights reserved")
      )
      (libsource (lib "470uF") (part "UVR1H471MHD1TO"))
    )
    (comp (ref "C87")
      (value "470uF 50V")
      (footprint "CAP_UAQ_12P5X20")
      (description "No Description Available")
      (fields
        (field (name "MANUFACTURER_PART_NUMBER") "UVR1H471MHD1TO")
        (field (name "COPYRIGHT") "Copyright (C) 2018 Accelerated Designs. All rights reserved")
      )
      (libsource (lib "470uF") (part "UVR1H471MHD1TO"))
    )
    (comp (ref "C88")
      (value "0.1uF")
      (footprint "0603")
      (description "No Description Available")
      (fields
        (field (name "MANUFACTURER_PART_NUMBER") "0603ZC224JAT2A")
        (field (name "COPYRIGHT") "Copyright (C) 2018 Accelerated Designs. All rights reserved")
      )
      (libsource (lib "Cap0603") (part "0603ZC224JAT2A"))
    )
    (comp (ref "C89")
      (value "47uF 16V")
      (footprint "PCAP_5x11-THRU-E")
      (description "No Description Available")
      (fields
        (field (name "MANUFACTURER_PART_NUMBER") "UPS1C470MDD")
        (field (name "COPYRIGHT") "Copyright (C) 2018 Accelerated Designs. All rights reserved")
      )
      (libsource (lib "47u") (part "UPS1C470MDD"))
    )
    (comp (ref "C90")
      (value "47uF 16V")
      (footprint "PCAP_5x11-THRU-E")
      (description "No Description Available")
      (fields
        (field (name "MANUFACTURER_PART_NUMBER") "UPS1C470MDD")
        (field (name "COPYRIGHT") "Copyright (C) 2018 Accelerated Designs. All rights reserved")
      )
      (libsource (lib "47u") (part "UPS1C470MDD"))
    )
    (comp (ref "C91")
      (value "0.01uF")
      (footprint "0603")
      (description "No Description Available")
      (fields
        (field (name "MANUFACTURER_PART_NUMBER") "0603ZC224JAT2A")
        (field (name "COPYRIGHT") "Copyright (C) 2018 Accelerated Designs. All rights reserved")
      )
      (libsource (lib "Cap0603") (part "0603ZC224JAT2A"))
    )
    (comp (ref "C92")
      (value "2.2uF")
      (footprint "CAP_0805J_AVX")
      (description "No Description Available")
      (fields
        (field (name "MANUFACTURER_PART_NUMBER") "08051A102JAT2A")
        (field (name "COPYRIGHT") "Copyright (C) 2018 Accelerated Designs. All rights reserved")
      )
      (libsource (lib "Cap0805") (part "08051A102JAT2A"))
    )
    (comp (ref "C93")
      (value "2.2uF")
      (footprint "CAP_0805J_AVX")
      (description "No Description Available")
      (fields
        (field (name "MANUFACTURER_PART_NUMBER") "08051A102JAT2A")
        (field (name "COPYRIGHT") "Copyright (C) 2018 Accelerated Designs. All rights reserved")
      )
      (libsource (lib "Cap0805") (part "08051A102JAT2A"))
    )
    (comp (ref "C94")
      (value "0.1uF")
      (footprint "0603")
      (description "No Description Available")
      (fields
        (field (name "MANUFACTURER_PART_NUMBER") "0603ZC224JAT2A")
        (field (name "COPYRIGHT") "Copyright (C) 2018 Accelerated Designs. All rights reserved")
      )
      (libsource (lib "Cap0603") (part "0603ZC224JAT2A"))
    )
    (comp (ref "C95")
      (value "6.8pF")
      (footprint "0603")
      (description "No Description Available")
      (fields
        (field (name "MANUFACTURER_PART_NUMBER") "0603ZC224JAT2A")
        (field (name "COPYRIGHT") "Copyright (C) 2018 Accelerated Designs. All rights reserved")
      )
      (libsource (lib "Cap0603") (part "0603ZC224JAT2A"))
    )
    (comp (ref "C96")
      (value "10uF 16V")
      (footprint "PCAP_5x11-THRU-E")
      (description "No Description Available")
      (fields
        (field (name "MANUFACTURER_PART_NUMBER") "UPS1C470MDD")
        (field (name "COPYRIGHT") "Copyright (C) 2018 Accelerated Designs. All rights reserved")
      )
      (libsource (lib "47u") (part "UPS1C470MDD"))
    )
    (comp (ref "C97")
      (value "10uF 16V")
      (footprint "PCAP_5x11-THRU-E")
      (description "No Description Available")
      (fields
        (field (name "MANUFACTURER_PART_NUMBER") "UPS1C470MDD")
        (field (name "COPYRIGHT") "Copyright (C) 2018 Accelerated Designs. All rights reserved")
      )
      (libsource (lib "47u") (part "UPS1C470MDD"))
    )
    (comp (ref "C98")
      (value "0.1uF")
      (footprint "0603")
      (description "No Description Available")
      (fields
        (field (name "MANUFACTURER_PART_NUMBER") "0603ZC224JAT2A")
        (field (name "COPYRIGHT") "Copyright (C) 2018 Accelerated Designs. All rights reserved")
      )
      (libsource (lib "Cap0603") (part "0603ZC224JAT2A"))
    )
    (comp (ref "C99")
      (value "0.1uF")
      (footprint "0603")
      (description "No Description Available")
      (fields
        (field (name "MANUFACTURER_PART_NUMBER") "0603ZC224JAT2A")
        (field (name "COPYRIGHT") "Copyright (C) 2018 Accelerated Designs. All rights reserved")
      )
      (libsource (lib "Cap0603") (part "0603ZC224JAT2A"))
    )
    (comp (ref "C100")
      (value "10uF 16V")
      (footprint "PCAP_5x11-THRU-E")
      (description "No Description Available")
      (fields
        (field (name "MANUFACTURER_PART_NUMBER") "UPS1C470MDD")
        (field (name "COPYRIGHT") "Copyright (C) 2018 Accelerated Designs. All rights reserved")
      )
      (libsource (lib "47u") (part "UPS1C470MDD"))
    )
    (comp (ref "C101")
      (value "10uF 16V")
      (footprint "PCAP_5x11-THRU-E")
      (description "No Description Available")
      (fields
        (field (name "MANUFACTURER_PART_NUMBER") "UPS1C470MDD")
        (field (name "COPYRIGHT") "Copyright (C) 2018 Accelerated Designs. All rights reserved")
      )
      (libsource (lib "47u") (part "UPS1C470MDD"))
    )
    (comp (ref "C102")
      (value "2700pF")
      (footprint "0603")
      (description "No Description Available")
      (fields
        (field (name "MANUFACTURER_PART_NUMBER") "0603ZC224JAT2A")
        (field (name "COPYRIGHT") "Copyright (C) 2018 Accelerated Designs. All rights reserved")
      )
      (libsource (lib "Cap0603") (part "0603ZC224JAT2A"))
    )
    (comp (ref "C103")
      (value "0.1uF")
      (footprint "0603")
      (description "No Description Available")
      (fields
        (field (name "MANUFACTURER_PART_NUMBER") "0603ZC224JAT2A")
        (field (name "COPYRIGHT") "Copyright (C) 2018 Accelerated Designs. All rights reserved")
      )
      (libsource (lib "Cap0603") (part "0603ZC224JAT2A"))
    )
    (comp (ref "C104")
      (value "0.1uF")
      (footprint "0603")
      (description "No Description Available")
      (fields
        (field (name "MANUFACTURER_PART_NUMBER") "0603ZC224JAT2A")
        (field (name "COPYRIGHT") "Copyright (C) 2018 Accelerated Designs. All rights reserved")
      )
      (libsource (lib "Cap0603") (part "0603ZC224JAT2A"))
    )
    (comp (ref "C105")
      (value "470uF 50V")
      (footprint "CAP_UAQ_12P5X20")
      (description "No Description Available")
      (fields
        (field (name "MANUFACTURER_PART_NUMBER") "UVR1H471MHD1TO")
        (field (name "COPYRIGHT") "Copyright (C) 2018 Accelerated Designs. All rights reserved")
      )
      (libsource (lib "470uF") (part "UVR1H471MHD1TO"))
    )
    (comp (ref "C106")
      (value "470uF 50V")
      (footprint "CAP_UAQ_12P5X20")
      (description "No Description Available")
      (fields
        (field (name "MANUFACTURER_PART_NUMBER") "UVR1H471MHD1TO")
        (field (name "COPYRIGHT") "Copyright (C) 2018 Accelerated Designs. All rights reserved")
      )
      (libsource (lib "470uF") (part "UVR1H471MHD1TO"))
    )
    (comp (ref "C107")
      (value "0.1uF")
      (footprint "0603")
      (description "No Description Available")
      (fields
        (field (name "MANUFACTURER_PART_NUMBER") "0603ZC224JAT2A")
        (field (name "COPYRIGHT") "Copyright (C) 2018 Accelerated Designs. All rights reserved")
      )
      (libsource (lib "Cap0603") (part "0603ZC224JAT2A"))
    )
    (comp (ref "C108")
      (value "0.1uF")
      (footprint "0603")
      (description "No Description Available")
      (fields
        (field (name "MANUFACTURER_PART_NUMBER") "0603ZC224JAT2A")
        (field (name "COPYRIGHT") "Copyright (C) 2018 Accelerated Designs. All rights reserved")
      )
      (libsource (lib "Cap0603") (part "0603ZC224JAT2A"))
    )
    (comp (ref "C109")
      (value "10uF 16V")
      (footprint "PCAP_5x11-THRU-E")
      (description "No Description Available")
      (fields
        (field (name "MANUFACTURER_PART_NUMBER") "UPS1C470MDD")
        (field (name "COPYRIGHT") "Copyright (C) 2018 Accelerated Designs. All rights reserved")
      )
      (libsource (lib "47u") (part "UPS1C470MDD"))
    )
    (comp (ref "C110")
      (value "10uF 16V")
      (footprint "PCAP_5x11-THRU-E")
      (description "No Description Available")
      (fields
        (field (name "MANUFACTURER_PART_NUMBER") "UPS1C470MDD")
        (field (name "COPYRIGHT") "Copyright (C) 2018 Accelerated Designs. All rights reserved")
      )
      (libsource (lib "47u") (part "UPS1C470MDD"))
    )
    (comp (ref "C111")
      (value "0.1uF")
      (footprint "0603")
      (description "No Description Available")
      (fields
        (field (name "MANUFACTURER_PART_NUMBER") "0603ZC224JAT2A")
        (field (name "COPYRIGHT") "Copyright (C) 2018 Accelerated Designs. All rights reserved")
      )
      (libsource (lib "Cap0603") (part "0603ZC224JAT2A"))
    )
    (comp (ref "C112")
      (value "0.1uF")
      (footprint "0603")
      (description "No Description Available")
      (fields
        (field (name "MANUFACTURER_PART_NUMBER") "0603ZC224JAT2A")
        (field (name "COPYRIGHT") "Copyright (C) 2018 Accelerated Designs. All rights reserved")
      )
      (libsource (lib "Cap0603") (part "0603ZC224JAT2A"))
    )
    (comp (ref "C113")
      (value "10uF 16V")
      (footprint "PCAP_5x11-THRU-E")
      (description "No Description Available")
      (fields
        (field (name "MANUFACTURER_PART_NUMBER") "UPS1C470MDD")
        (field (name "COPYRIGHT") "Copyright (C) 2018 Accelerated Designs. All rights reserved")
      )
      (libsource (lib "47u") (part "UPS1C470MDD"))
    )
    (comp (ref "C114")
      (value "10uF 16V")
      (footprint "PCAP_5x11-THRU-E")
      (description "No Description Available")
      (fields
        (field (name "MANUFACTURER_PART_NUMBER") "UPS1C470MDD")
        (field (name "COPYRIGHT") "Copyright (C) 2018 Accelerated Designs. All rights reserved")
      )
      (libsource (lib "47u") (part "UPS1C470MDD"))
    )
    (comp (ref "C115")
      (value "0.1uF")
      (footprint "0603")
      (description "No Description Available")
      (fields
        (field (name "MANUFACTURER_PART_NUMBER") "0603ZC224JAT2A")
        (field (name "COPYRIGHT") "Copyright (C) 2018 Accelerated Designs. All rights reserved")
      )
      (libsource (lib "Cap0603") (part "0603ZC224JAT2A"))
    )
    (comp (ref "C116")
      (value "0.1uF")
      (footprint "0603")
      (description "No Description Available")
      (fields
        (field (name "MANUFACTURER_PART_NUMBER") "0603ZC224JAT2A")
        (field (name "COPYRIGHT") "Copyright (C) 2018 Accelerated Designs. All rights reserved")
      )
      (libsource (lib "Cap0603") (part "0603ZC224JAT2A"))
    )
    (comp (ref "C117")
      (value "470uF 50V")
      (footprint "CAP_UAQ_12P5X20")
      (description "No Description Available")
      (fields
        (field (name "MANUFACTURER_PART_NUMBER") "UVR1H471MHD1TO")
        (field (name "COPYRIGHT") "Copyright (C) 2018 Accelerated Designs. All rights reserved")
      )
      (libsource (lib "470uF") (part "UVR1H471MHD1TO"))
    )
    (comp (ref "C118")
      (value "470uF 50V")
      (footprint "CAP_UAQ_12P5X20")
      (description "No Description Available")
      (fields
        (field (name "MANUFACTURER_PART_NUMBER") "UVR1H471MHD1TO")
        (field (name "COPYRIGHT") "Copyright (C) 2018 Accelerated Designs. All rights reserved")
      )
      (libsource (lib "470uF") (part "UVR1H471MHD1TO"))
    )
    (comp (ref "CR1")
      (value "SM6T15A")
      (footprint "SMB_STM")
      (description "No Description Available")
      (fields (field (name "COPYRIGHT") "Copyright (C) 2018 Accelerated Designs. All rights reserved"))
      (libsource (lib "SM6T15A") (part "SM6T15A"))
    )
    (comp (ref "CR2")
      (value "SM6T15A")
      (footprint "SMB_STM")
      (description "No Description Available")
      (fields (field (name "COPYRIGHT") "Copyright (C) 2018 Accelerated Designs. All rights reserved"))
      (libsource (lib "SM6T15A") (part "SM6T15A"))
    )
    (comp (ref "CR3")
      (value "SM6T18CA")
      (footprint "SMB_STM")
      (description "No Description Available")
      (fields (field (name "COPYRIGHT") "Copyright (C) 2018 Accelerated Designs. All rights reserved"))
      (libsource (lib "SM6T18CA") (part "SM6T18CA"))
    )
    (comp (ref "CR4")
      (value "SM6T15A")
      (footprint "SMB_STM")
      (description "No Description Available")
      (fields (field (name "COPYRIGHT") "Copyright (C) 2018 Accelerated Designs. All rights reserved"))
      (libsource (lib "SM6T15A") (part "SM6T15A"))
    )
    (comp (ref "CR5")
      (value "SM6T15A")
      (footprint "SMB_STM")
      (description "No Description Available")
      (fields (field (name "COPYRIGHT") "Copyright (C) 2018 Accelerated Designs. All rights reserved"))
      (libsource (lib "SM6T15A") (part "SM6T15A"))
    )
    (comp (ref "CR6")
      (value "SM6T15A")
      (footprint "SMB_STM")
      (description "No Description Available")
      (fields (field (name "COPYRIGHT") "Copyright (C) 2018 Accelerated Designs. All rights reserved"))
      (libsource (lib "SM6T15A") (part "SM6T15A"))
    )
    (comp (ref "CR7")
      (value "SM6T15A")
      (footprint "SMB_STM")
      (description "No Description Available")
      (fields (field (name "COPYRIGHT") "Copyright (C) 2018 Accelerated Designs. All rights reserved"))
      (libsource (lib "SM6T15A") (part "SM6T15A"))
    )
    (comp (ref "CR8")
      (value "SM6T15A")
      (footprint "SMB_STM")
      (description "No Description Available")
      (fields (field (name "COPYRIGHT") "Copyright (C) 2018 Accelerated Designs. All rights reserved"))
      (libsource (lib "SM6T15A") (part "SM6T15A"))
    )
    (comp (ref "CR9")
      (value "SM6T15A")
      (footprint "SMB_STM")
      (description "No Description Available")
      (fields (field (name "COPYRIGHT") "Copyright (C) 2018 Accelerated Designs. All rights reserved"))
      (libsource (lib "SM6T15A") (part "SM6T15A"))
    )
    (comp (ref "CR10")
      (value "SM6T15A")
      (footprint "SMB_STM")
      (description "No Description Available")
      (fields (field (name "COPYRIGHT") "Copyright (C) 2018 Accelerated Designs. All rights reserved"))
      (libsource (lib "SM6T15A") (part "SM6T15A"))
    )
    (comp (ref "CR11")
      (value "SM6T15A")
      (footprint "SMB_STM")
      (description "No Description Available")
      (fields (field (name "COPYRIGHT") "Copyright (C) 2018 Accelerated Designs. All rights reserved"))
      (libsource (lib "SM6T15A") (part "SM6T15A"))
    )
    (comp (ref "CR12")
      (value "SM6T15A")
      (footprint "SMB_STM")
      (description "No Description Available")
      (fields (field (name "COPYRIGHT") "Copyright (C) 2018 Accelerated Designs. All rights reserved"))
      (libsource (lib "SM6T15A") (part "SM6T15A"))
    )
    (comp (ref "CR13")
      (value "SM6T15A")
      (footprint "SMB_STM")
      (description "No Description Available")
      (fields (field (name "COPYRIGHT") "Copyright (C) 2018 Accelerated Designs. All rights reserved"))
      (libsource (lib "SM6T15A") (part "SM6T15A"))
    )
    (comp (ref "CR14")
      (value "SM6T15A")
      (footprint "SMB_STM")
      (description "No Description Available")
      (fields (field (name "COPYRIGHT") "Copyright (C) 2018 Accelerated Designs. All rights reserved"))
      (libsource (lib "SM6T15A") (part "SM6T15A"))
    )
    (comp (ref "CR15")
      (value "SM6T15A")
      (footprint "SMB_STM")
      (description "No Description Available")
      (fields (field (name "COPYRIGHT") "Copyright (C) 2018 Accelerated Designs. All rights reserved"))
      (libsource (lib "SM6T15A") (part "SM6T15A"))
    )
    (comp (ref "CR16")
      (value "SM6T15A")
      (footprint "SMB_STM")
      (description "No Description Available")
      (fields (field (name "COPYRIGHT") "Copyright (C) 2018 Accelerated Designs. All rights reserved"))
      (libsource (lib "SM6T15A") (part "SM6T15A"))
    )
    (comp (ref "CR17")
      (value "SM6T15A")
      (footprint "SMB_STM")
      (description "No Description Available")
      (fields (field (name "COPYRIGHT") "Copyright (C) 2018 Accelerated Designs. All rights reserved"))
      (libsource (lib "SM6T15A") (part "SM6T15A"))
    )
    (comp (ref "D1")
      (value "MBRS260T3G")
      (footprint "SMB")
      (description "Diode Schottky 60V 2A Surface Mount SMB")
      (fields
        (field (name "MF") "ON Semiconductor")
        (field (name "DIGI-KEY_PART_NUMBER") "MBRS260T3GOSCT-ND")
      )
      (libsource (lib "MBRS260T3G") (part "MBRS260T3G"))
    )
    (comp (ref "D2")
      (value "MBRS260T3G")
      (footprint "SMB")
      (description "Diode Schottky 60V 2A Surface Mount SMB")
      (fields
        (field (name "MF") "ON Semiconductor")
        (field (name "DIGI-KEY_PART_NUMBER") "MBRS260T3GOSCT-ND")
      )
      (libsource (lib "MBRS260T3G") (part "MBRS260T3G"))
    )
    (comp (ref "D3")
      (value "MBRS260T3G")
      (footprint "SMB")
      (description "Diode Schottky 60V 2A Surface Mount SMB")
      (fields
        (field (name "MF") "ON Semiconductor")
        (field (name "DIGI-KEY_PART_NUMBER") "MBRS260T3GOSCT-ND")
      )
      (libsource (lib "MBRS260T3G") (part "MBRS260T3G"))
    )
    (comp (ref "J1")
      (value "ESP32DEVKITV1")
      (footprint "ESP32-DEVKITV1")
      (fields (field (name "MF") "Do it") (field (name "MP") "ESP32 DEVKIT V1"))
      (libsource (lib "ESP32DEVKITV1") (part "ESP32DEVKITV1"))
    )
    (comp (ref "L1")
      (value "B82472G6103M000")
      (footprint "IND_EPCOS_B82472G6_EPC")
      (description "No Description Available")
      (fields (field (name "COPYRIGHT") "Copyright (C) 2018 Accelerated Designs. All rights reserved"))
      (libsource (lib "Ind10uH") (part "B82472G6103M000"))
    )
    (comp (ref "L2")
      (value "B82472G6103M000")
      (footprint "IND_EPCOS_B82472G6_EPC")
      (description "No Description Available")
      (fields (field (name "COPYRIGHT") "Copyright (C) 2018 Accelerated Designs. All rights reserved"))
      (libsource (lib "Ind10uH") (part "B82472G6103M000"))
    )
    (comp (ref "L3")
      (value "B82472G6103M000")
      (footprint "IND_EPCOS_B82472G6_EPC")
      (description "No Description Available")
      (fields (field (name "COPYRIGHT") "Copyright (C) 2018 Accelerated Designs. All rights reserved"))
      (libsource (lib "Ind10uH") (part "B82472G6103M000"))
    )
    (comp (ref "R1")
      (value "10")
      (footprint "RC0603N")
      (description "No Description Available")
      (fields
        (field (name "MANUFACTURER_PART_NUMBER") "ERA-3AEB101V")
        (field (name "COPYRIGHT") "Copyright (C) 2018 Accelerated Designs. All rights reserved")
      )
      (libsource (lib "Res0603") (part "ERA-3AEB101V"))
    )
    (comp (ref "R2")
      (value "10")
      (footprint "RC0603N")
      (description "No Description Available")
      (fields
        (field (name "MANUFACTURER_PART_NUMBER") "ERA-3AEB101V")
        (field (name "COPYRIGHT") "Copyright (C) 2018 Accelerated Designs. All rights reserved")
      )
      (libsource (lib "Res0603") (part "ERA-3AEB101V"))
    )
    (comp (ref "R3")
      (value "10")
      (footprint "RC0603N")
      (description "No Description Available")
      (fields
        (field (name "MANUFACTURER_PART_NUMBER") "ERA-3AEB101V")
        (field (name "COPYRIGHT") "Copyright (C) 2018 Accelerated Designs. All rights reserved")
      )
      (libsource (lib "Res0603") (part "ERA-3AEB101V"))
    )
    (comp (ref "R4")
      (value "10")
      (footprint "RC0603N")
      (description "No Description Available")
      (fields
        (field (name "MANUFACTURER_PART_NUMBER") "ERA-3AEB101V")
        (field (name "COPYRIGHT") "Copyright (C) 2018 Accelerated Designs. All rights reserved")
      )
      (libsource (lib "Res0603") (part "ERA-3AEB101V"))
    )
    (comp (ref "R5")
      (value "120")
      (footprint "RC0603N")
      (description "No Description Available")
      (fields
        (field (name "MANUFACTURER_PART_NUMBER") "ERA-3AEB101V")
        (field (name "COPYRIGHT") "Copyright (C) 2018 Accelerated Designs. All rights reserved")
      )
      (libsource (lib "Res0603") (part "ERA-3AEB101V"))
    )
    (comp (ref "R6")
      (value "470")
      (footprint "RC0603N")
      (description "No Description Available")
      (fields
        (field (name "MANUFACTURER_PART_NUMBER") "ERA-3AEB101V")
        (field (name "COPYRIGHT") "Copyright (C) 2018 Accelerated Designs. All rights reserved")
      )
      (libsource (lib "Res0603") (part "ERA-3AEB101V"))
    )
    (comp (ref "R7")
      (value "470")
      (footprint "RC0603N")
      (description "No Description Available")
      (fields
        (field (name "MANUFACTURER_PART_NUMBER") "ERA-3AEB101V")
        (field (name "COPYRIGHT") "Copyright (C) 2018 Accelerated Designs. All rights reserved")
      )
      (libsource (lib "Res0603") (part "ERA-3AEB101V"))
    )
    (comp (ref "R8")
      (value "10")
      (footprint "RC0603N")
      (description "No Description Available")
      (fields
        (field (name "MANUFACTURER_PART_NUMBER") "ERA-3AEB101V")
        (field (name "COPYRIGHT") "Copyright (C) 2018 Accelerated Designs. All rights reserved")
      )
      (libsource (lib "Res0603") (part "ERA-3AEB101V"))
    )
    (comp (ref "R9")
      (value "10")
      (footprint "RC0603N")
      (description "No Description Available")
      (fields
        (field (name "MANUFACTURER_PART_NUMBER") "ERA-3AEB101V")
        (field (name "COPYRIGHT") "Copyright (C) 2018 Accelerated Designs. All rights reserved")
      )
      (libsource (lib "Res0603") (part "ERA-3AEB101V"))
    )
    (comp (ref "R10")
      (value "10")
      (footprint "RC0603N")
      (description "No Description Available")
      (fields
        (field (name "MANUFACTURER_PART_NUMBER") "ERA-3AEB101V")
        (field (name "COPYRIGHT") "Copyright (C) 2018 Accelerated Designs. All rights reserved")
      )
      (libsource (lib "Res0603") (part "ERA-3AEB101V"))
    )
    (comp (ref "R11")
      (value "10")
      (footprint "RC0603N")
      (description "No Description Available")
      (fields
        (field (name "MANUFACTURER_PART_NUMBER") "ERA-3AEB101V")
        (field (name "COPYRIGHT") "Copyright (C) 2018 Accelerated Designs. All rights reserved")
      )
      (libsource (lib "Res0603") (part "ERA-3AEB101V"))
    )
    (comp (ref "R12")
      (value "10")
      (footprint "RC0603N")
      (description "No Description Available")
      (fields
        (field (name "MANUFACTURER_PART_NUMBER") "ERA-3AEB101V")
        (field (name "COPYRIGHT") "Copyright (C) 2018 Accelerated Designs. All rights reserved")
      )
      (libsource (lib "Res0603") (part "ERA-3AEB101V"))
    )
    (comp (ref "R13")
      (value "10")
      (footprint "RC0603N")
      (description "No Description Available")
      (fields
        (field (name "MANUFACTURER_PART_NUMBER") "ERA-3AEB101V")
        (field (name "COPYRIGHT") "Copyright (C) 2018 Accelerated Designs. All rights reserved")
      )
      (libsource (lib "Res0603") (part "ERA-3AEB101V"))
    )
    (comp (ref "R14")
      (value "10")
      (footprint "RC0603N")
      (description "No Description Available")
      (fields
        (field (name "MANUFACTURER_PART_NUMBER") "ERA-3AEB101V")
        (field (name "COPYRIGHT") "Copyright (C) 2018 Accelerated Designs. All rights reserved")
      )
      (libsource (lib "Res0603") (part "ERA-3AEB101V"))
    )
    (comp (ref "R15")
      (value "10")
      (footprint "RC0603N")
      (description "No Description Available")
      (fields
        (field (name "MANUFACTURER_PART_NUMBER") "ERA-3AEB101V")
        (field (name "COPYRIGHT") "Copyright (C) 2018 Accelerated Designs. All rights reserved")
      )
      (libsource (lib "Res0603") (part "ERA-3AEB101V"))
    )
    (comp (ref "R16")
      (value "470")
      (footprint "RC0603N")
      (description "No Description Available")
      (fields
        (field (name "MANUFACTURER_PART_NUMBER") "ERA-3AEB101V")
        (field (name "COPYRIGHT") "Copyright (C) 2018 Accelerated Designs. All rights reserved")
      )
      (libsource (lib "Res0603") (part "ERA-3AEB101V"))
    )
    (comp (ref "R17")
      (value "470")
      (footprint "RC0603N")
      (description "No Description Available")
      (fields
        (field (name "MANUFACTURER_PART_NUMBER") "ERA-3AEB101V")
        (field (name "COPYRIGHT") "Copyright (C) 2018 Accelerated Designs. All rights reserved")
      )
      (libsource (lib "Res0603") (part "ERA-3AEB101V"))
    )
    (comp (ref "R18")
      (value "10")
      (footprint "RC0603N")
      (description "No Description Available")
      (fields
        (field (name "MANUFACTURER_PART_NUMBER") "ERA-3AEB101V")
        (field (name "COPYRIGHT") "Copyright (C) 2018 Accelerated Designs. All rights reserved")
      )
      (libsource (lib "Res0603") (part "ERA-3AEB101V"))
    )
    (comp (ref "R19")
      (value "10")
      (footprint "RC0603N")
      (description "No Description Available")
      (fields
        (field (name "MANUFACTURER_PART_NUMBER") "ERA-3AEB101V")
        (field (name "COPYRIGHT") "Copyright (C) 2018 Accelerated Designs. All rights reserved")
      )
      (libsource (lib "Res0603") (part "ERA-3AEB101V"))
    )
    (comp (ref "R20")
      (value "82k")
      (footprint "RC0603N")
      (description "No Description Available")
      (fields
        (field (name "MANUFACTURER_PART_NUMBER") "ERA-3AEB101V")
        (field (name "COPYRIGHT") "Copyright (C) 2018 Accelerated Designs. All rights reserved")
      )
      (libsource (lib "Res0603") (part "ERA-3AEB101V"))
    )
    (comp (ref "R21")
      (value "10")
      (footprint "RC0603N")
      (description "No Description Available")
      (fields
        (field (name "MANUFACTURER_PART_NUMBER") "ERA-3AEB101V")
        (field (name "COPYRIGHT") "Copyright (C) 2018 Accelerated Designs. All rights reserved")
      )
      (libsource (lib "Res0603") (part "ERA-3AEB101V"))
    )
    (comp (ref "R22")
      (value "10")
      (footprint "RC0603N")
      (description "No Description Available")
      (fields
        (field (name "MANUFACTURER_PART_NUMBER") "ERA-3AEB101V")
        (field (name "COPYRIGHT") "Copyright (C) 2018 Accelerated Designs. All rights reserved")
      )
      (libsource (lib "Res0603") (part "ERA-3AEB101V"))
    )
    (comp (ref "R23")
      (value "6.2k")
      (footprint "RC0603N")
      (description "No Description Available")
      (fields
        (field (name "MANUFACTURER_PART_NUMBER") "ERA-3AEB101V")
        (field (name "COPYRIGHT") "Copyright (C) 2018 Accelerated Designs. All rights reserved")
      )
      (libsource (lib "Res0603") (part "ERA-3AEB101V"))
    )
    (comp (ref "R24")
      (value "76.8k")
      (footprint "RC0603N")
      (description "No Description Available")
      (fields
        (field (name "MANUFACTURER_PART_NUMBER") "ERA-3AEB101V")
        (field (name "COPYRIGHT") "Copyright (C) 2018 Accelerated Designs. All rights reserved")
      )
      (libsource (lib "Res0603") (part "ERA-3AEB101V"))
    )
    (comp (ref "R25")
      (value "90.9k")
      (footprint "RC0603N")
      (description "No Description Available")
      (fields
        (field (name "MANUFACTURER_PART_NUMBER") "ERA-3AEB101V")
        (field (name "COPYRIGHT") "Copyright (C) 2018 Accelerated Designs. All rights reserved")
      )
      (libsource (lib "Res0603") (part "ERA-3AEB101V"))
    )
    (comp (ref "R26")
      (value "10")
      (footprint "RC0603N")
      (description "No Description Available")
      (fields
        (field (name "MANUFACTURER_PART_NUMBER") "ERA-3AEB101V")
        (field (name "COPYRIGHT") "Copyright (C) 2018 Accelerated Designs. All rights reserved")
      )
      (libsource (lib "Res0603") (part "ERA-3AEB101V"))
    )
    (comp (ref "R27")
      (value "10")
      (footprint "RC0603N")
      (description "No Description Available")
      (fields
        (field (name "MANUFACTURER_PART_NUMBER") "ERA-3AEB101V")
        (field (name "COPYRIGHT") "Copyright (C) 2018 Accelerated Designs. All rights reserved")
      )
      (libsource (lib "Res0603") (part "ERA-3AEB101V"))
    )
    (comp (ref "R28")
      (value "62k")
      (footprint "RC0603N")
      (description "No Description Available")
      (fields
        (field (name "MANUFACTURER_PART_NUMBER") "ERA-3AEB101V")
        (field (name "COPYRIGHT") "Copyright (C) 2018 Accelerated Designs. All rights reserved")
      )
      (libsource (lib "Res0603") (part "ERA-3AEB101V"))
    )
    (comp (ref "R29")
      (value "10")
      (footprint "RC0603N")
      (description "No Description Available")
      (fields
        (field (name "MANUFACTURER_PART_NUMBER") "ERA-3AEB101V")
        (field (name "COPYRIGHT") "Copyright (C) 2018 Accelerated Designs. All rights reserved")
      )
      (libsource (lib "Res0603") (part "ERA-3AEB101V"))
    )
    (comp (ref "R30")
      (value "10")
      (footprint "RC0603N")
      (description "No Description Available")
      (fields
        (field (name "MANUFACTURER_PART_NUMBER") "ERA-3AEB101V")
        (field (name "COPYRIGHT") "Copyright (C) 2018 Accelerated Designs. All rights reserved")
      )
      (libsource (lib "Res0603") (part "ERA-3AEB101V"))
    )
    (comp (ref "R31")
      (value "12k")
      (footprint "RC0603N")
      (description "No Description Available")
      (fields
        (field (name "MANUFACTURER_PART_NUMBER") "ERA-3AEB101V")
        (field (name "COPYRIGHT") "Copyright (C) 2018 Accelerated Designs. All rights reserved")
      )
      (libsource (lib "Res0603") (part "ERA-3AEB101V"))
    )
    (comp (ref "R32")
      (value "470")
      (footprint "RC0603N")
      (description "No Description Available")
      (fields
        (field (name "MANUFACTURER_PART_NUMBER") "ERA-3AEB101V")
        (field (name "COPYRIGHT") "Copyright (C) 2018 Accelerated Designs. All rights reserved")
      )
      (libsource (lib "Res0603") (part "ERA-3AEB101V"))
    )
    (comp (ref "R33")
      (value "470")
      (footprint "RC0603N")
      (description "No Description Available")
      (fields
        (field (name "MANUFACTURER_PART_NUMBER") "ERA-3AEB101V")
        (field (name "COPYRIGHT") "Copyright (C) 2018 Accelerated Designs. All rights reserved")
      )
      (libsource (lib "Res0603") (part "ERA-3AEB101V"))
    )
    (comp (ref "R34")
      (value "76.8k")
      (footprint "RC0603N")
      (description "No Description Available")
      (fields
        (field (name "MANUFACTURER_PART_NUMBER") "ERA-3AEB101V")
        (field (name "COPYRIGHT") "Copyright (C) 2018 Accelerated Designs. All rights reserved")
      )
      (libsource (lib "Res0603") (part "ERA-3AEB101V"))
    )
    (comp (ref "R35")
      (value "90.9k")
      (footprint "RC0603N")
      (description "No Description Available")
      (fields
        (field (name "MANUFACTURER_PART_NUMBER") "ERA-3AEB101V")
        (field (name "COPYRIGHT") "Copyright (C) 2018 Accelerated Designs. All rights reserved")
      )
      (libsource (lib "Res0603") (part "ERA-3AEB101V"))
    )
    (comp (ref "R36")
      (value "10")
      (footprint "RC0603N")
      (description "No Description Available")
      (fields
        (field (name "MANUFACTURER_PART_NUMBER") "ERA-3AEB101V")
        (field (name "COPYRIGHT") "Copyright (C) 2018 Accelerated Designs. All rights reserved")
      )
      (libsource (lib "Res0603") (part "ERA-3AEB101V"))
    )
    (comp (ref "R37")
      (value "10")
      (footprint "RC0603N")
      (description "No Description Available")
      (fields
        (field (name "MANUFACTURER_PART_NUMBER") "ERA-3AEB101V")
        (field (name "COPYRIGHT") "Copyright (C) 2018 Accelerated Designs. All rights reserved")
      )
      (libsource (lib "Res0603") (part "ERA-3AEB101V"))
    )
    (comp (ref "R38")
      (value "10")
      (footprint "RC0603N")
      (description "No Description Available")
      (fields
        (field (name "MANUFACTURER_PART_NUMBER") "ERA-3AEB101V")
        (field (name "COPYRIGHT") "Copyright (C) 2018 Accelerated Designs. All rights reserved")
      )
      (libsource (lib "Res0603") (part "ERA-3AEB101V"))
    )
    (comp (ref "R39")
      (value "10")
      (footprint "RC0603N")
      (description "No Description Available")
      (fields
        (field (name "MANUFACTURER_PART_NUMBER") "ERA-3AEB101V")
        (field (name "COPYRIGHT") "Copyright (C) 2018 Accelerated Designs. All rights reserved")
      )
      (libsource (lib "Res0603") (part "ERA-3AEB101V"))
    )
    (comp (ref "R40")
      (value "47k")
      (footprint "RC0603N")
      (description "No Description Available")
      (fields
        (field (name "MANUFACTURER_PART_NUMBER") "ERA-3AEB101V")
        (field (name "COPYRIGHT") "Copyright (C) 2018 Accelerated Designs. All rights reserved")
      )
      (libsource (lib "Res0603") (part "ERA-3AEB101V"))
    )
    (comp (ref "R41")
      (value "15k")
      (footprint "RC0603N")
      (description "No Description Available")
      (fields
        (field (name "MANUFACTURER_PART_NUMBER") "ERA-3AEB101V")
        (field (name "COPYRIGHT") "Copyright (C) 2018 Accelerated Designs. All rights reserved")
      )
      (libsource (lib "Res0603") (part "ERA-3AEB101V"))
    )
    (comp (ref "R42")
      (value "76.8k")
      (footprint "RC0603N")
      (description "No Description Available")
      (fields
        (field (name "MANUFACTURER_PART_NUMBER") "ERA-3AEB101V")
        (field (name "COPYRIGHT") "Copyright (C) 2018 Accelerated Designs. All rights reserved")
      )
      (libsource (lib "Res0603") (part "ERA-3AEB101V"))
    )
    (comp (ref "R43")
      (value "90.9k")
      (footprint "RC0603N")
      (description "No Description Available")
      (fields
        (field (name "MANUFACTURER_PART_NUMBER") "ERA-3AEB101V")
        (field (name "COPYRIGHT") "Copyright (C) 2018 Accelerated Designs. All rights reserved")
      )
      (libsource (lib "Res0603") (part "ERA-3AEB101V"))
    )
    (comp (ref "R44")
      (value "10")
      (footprint "RC0603N")
      (description "No Description Available")
      (fields
        (field (name "MANUFACTURER_PART_NUMBER") "ERA-3AEB101V")
        (field (name "COPYRIGHT") "Copyright (C) 2018 Accelerated Designs. All rights reserved")
      )
      (libsource (lib "Res0603") (part "ERA-3AEB101V"))
    )
    (comp (ref "R45")
      (value "10")
      (footprint "RC0603N")
      (description "No Description Available")
      (fields
        (field (name "MANUFACTURER_PART_NUMBER") "ERA-3AEB101V")
        (field (name "COPYRIGHT") "Copyright (C) 2018 Accelerated Designs. All rights reserved")
      )
      (libsource (lib "Res0603") (part "ERA-3AEB101V"))
    )
    (comp (ref "R46")
      (value "10")
      (footprint "RC0603N")
      (description "No Description Available")
      (fields
        (field (name "MANUFACTURER_PART_NUMBER") "ERA-3AEB101V")
        (field (name "COPYRIGHT") "Copyright (C) 2018 Accelerated Designs. All rights reserved")
      )
      (libsource (lib "Res0603") (part "ERA-3AEB101V"))
    )
    (comp (ref "R47")
      (value "10")
      (footprint "RC0603N")
      (description "No Description Available")
      (fields
        (field (name "MANUFACTURER_PART_NUMBER") "ERA-3AEB101V")
        (field (name "COPYRIGHT") "Copyright (C) 2018 Accelerated Designs. All rights reserved")
      )
      (libsource (lib "Res0603") (part "ERA-3AEB101V"))
    )
    (comp (ref "R48")
      (value "470")
      (footprint "RC0603N")
      (description "No Description Available")
      (fields
        (field (name "MANUFACTURER_PART_NUMBER") "ERA-3AEB101V")
        (field (name "COPYRIGHT") "Copyright (C) 2018 Accelerated Designs. All rights reserved")
      )
      (libsource (lib "Res0603") (part "ERA-3AEB101V"))
    )
    (comp (ref "R49")
      (value "470")
      (footprint "RC0603N")
      (description "No Description Available")
      (fields
        (field (name "MANUFACTURER_PART_NUMBER") "ERA-3AEB101V")
        (field (name "COPYRIGHT") "Copyright (C) 2018 Accelerated Designs. All rights reserved")
      )
      (libsource (lib "Res0603") (part "ERA-3AEB101V"))
    )
    (comp (ref "R50")
      (value "10")
      (footprint "RC0603N")
      (description "No Description Available")
      (fields
        (field (name "MANUFACTURER_PART_NUMBER") "ERA-3AEB101V")
        (field (name "COPYRIGHT") "Copyright (C) 2018 Accelerated Designs. All rights reserved")
      )
      (libsource (lib "Res0603") (part "ERA-3AEB101V"))
    )
    (comp (ref "R51")
      (value "10")
      (footprint "RC0603N")
      (description "No Description Available")
      (fields
        (field (name "MANUFACTURER_PART_NUMBER") "ERA-3AEB101V")
        (field (name "COPYRIGHT") "Copyright (C) 2018 Accelerated Designs. All rights reserved")
      )
      (libsource (lib "Res0603") (part "ERA-3AEB101V"))
    )
    (comp (ref "R52")
      (value "10")
      (footprint "RC0603N")
      (description "No Description Available")
      (fields
        (field (name "MANUFACTURER_PART_NUMBER") "ERA-3AEB101V")
        (field (name "COPYRIGHT") "Copyright (C) 2018 Accelerated Designs. All rights reserved")
      )
      (libsource (lib "Res0603") (part "ERA-3AEB101V"))
    )
    (comp (ref "R53")
      (value "10")
      (footprint "RC0603N")
      (description "No Description Available")
      (fields
        (field (name "MANUFACTURER_PART_NUMBER") "ERA-3AEB101V")
        (field (name "COPYRIGHT") "Copyright (C) 2018 Accelerated Designs. All rights reserved")
      )
      (libsource (lib "Res0603") (part "ERA-3AEB101V"))
    )
    (comp (ref "R54")
      (value "0")
      (footprint "RC0603N")
      (description "No Description Available")
      (fields
        (field (name "MANUFACTURER_PART_NUMBER") "ERA-3AEB101V")
        (field (name "COPYRIGHT") "Copyright (C) 2018 Accelerated Designs. All rights reserved")
      )
      (libsource (lib "Res0603") (part "ERA-3AEB101V"))
    )
    (comp (ref "R55")
      (value "0")
      (footprint "RC0603N")
      (description "No Description Available")
      (fields
        (field (name "MANUFACTURER_PART_NUMBER") "ERA-3AEB101V")
        (field (name "COPYRIGHT") "Copyright (C) 2018 Accelerated Designs. All rights reserved")
      )
      (libsource (lib "Res0603") (part "ERA-3AEB101V"))
    )
    (comp (ref "R56")
      (value "51")
      (footprint "RC0603N")
      (description "No Description Available")
      (fields
        (field (name "MANUFACTURER_PART_NUMBER") "ERA-3AEB101V")
        (field (name "COPYRIGHT") "Copyright (C) 2018 Accelerated Designs. All rights reserved")
      )
      (libsource (lib "Res0603") (part "ERA-3AEB101V"))
    )
    (comp (ref "R57")
      (value "10k")
      (footprint "RC0603N")
      (description "No Description Available")
      (fields
        (field (name "MANUFACTURER_PART_NUMBER") "ERA-3AEB101V")
        (field (name "COPYRIGHT") "Copyright (C) 2018 Accelerated Designs. All rights reserved")
      )
      (libsource (lib "Res0603") (part "ERA-3AEB101V"))
    )
    (comp (ref "TB1")
      (value "STM32F4DISCOVERY")
      (footprint "MODULE_STM32F4DISCOVERY")
      (description "STM32F407VGT6 Discovery STM32F4 ARMÂ® CortexÂ®-M4 MCU 32-Bit Embedded Evaluation Board")
      (fields (field (name "MF") "STMicroelectronics"))
      (libsource (lib "STM32F407Disc") (part "STM32F4DISCOVERY"))
    )
    (comp (ref "U1")
      (value "IR2109")
      (footprint "SOIC127P600X175-8N")
      (fields (field (name "MF") "Infineon"))
      (libsource (lib "IR2109") (part "IR2109"))
    )
    (comp (ref "U2")
      (value "IR2109")
      (footprint "SOIC127P600X175-8N")
      (fields (field (name "MF") "Infineon"))
      (libsource (lib "IR2109") (part "IR2109"))
    )
    (comp (ref "U3")
      (value "MCP2562")
      (footprint "SOIC8-N_MC_MCH")
      (description "No Description Available")
      (fields (field (name "COPYRIGHT") "Copyright (C) 2018 Accelerated Designs. All rights reserved"))
      (libsource (lib "MCP2561") (part "MCP2562"))
    )
    (comp (ref "U4")
      (value "ACS758-150B")
      (footprint "PFF-5_ALM")
      (description "No Description Available")
      (fields
        (field (name "MANUFACTURER_PART_NUMBER") "ACS756SCA-050B-PFF-T")
        (field (name "COPYRIGHT") "Copyright (C) 2018 Accelerated Designs. All rights reserved")
      )
      (libsource (lib "ACS756") (part "ACS756SCA-050B-PFF-T"))
    )
    (comp (ref "U5")
      (value "ACS758-150B")
      (footprint "PFF-5_ALM")
      (description "No Description Available")
      (fields
        (field (name "MANUFACTURER_PART_NUMBER") "ACS756SCA-050B-PFF-T")
        (field (name "COPYRIGHT") "Copyright (C) 2018 Accelerated Designs. All rights reserved")
      )
      (libsource (lib "ACS756") (part "ACS756SCA-050B-PFF-T"))
    )
    (comp (ref "U6")
      (value "IR2109")
      (footprint "SOIC127P600X175-8N")
      (fields (field (name "MF") "Infineon"))
      (libsource (lib "IR2109") (part "IR2109"))
    )
    (comp (ref "U7")
      (value "IR2109")
      (footprint "SOIC127P600X175-8N")
      (fields (field (name "MF") "Infineon"))
      (libsource (lib "IR2109") (part "IR2109"))
    )
    (comp (ref "U8")
      (value "IR2109")
      (footprint "SOIC127P600X175-8N")
      (fields (field (name "MF") "Infineon"))
      (libsource (lib "IR2109") (part "IR2109"))
    )
    (comp (ref "U9")
      (value "IR2109")
      (footprint "SOIC127P600X175-8N")
      (fields (field (name "MF") "Infineon"))
      (libsource (lib "IR2109") (part "IR2109"))
    )
    (comp (ref "U10")
      (value "ACS758-150B")
      (footprint "PFF-5_ALM")
      (description "No Description Available")
      (fields
        (field (name "MANUFACTURER_PART_NUMBER") "ACS756SCA-050B-PFF-T")
        (field (name "COPYRIGHT") "Copyright (C) 2018 Accelerated Designs. All rights reserved")
      )
      (libsource (lib "ACS756") (part "ACS756SCA-050B-PFF-T"))
    )
    (comp (ref "U11")
      (value "ACS758-150B")
      (footprint "PFF-5_ALM")
      (description "No Description Available")
      (fields
        (field (name "MANUFACTURER_PART_NUMBER") "ACS756SCA-050B-PFF-T")
        (field (name "COPYRIGHT") "Copyright (C) 2018 Accelerated Designs. All rights reserved")
      )
      (libsource (lib "ACS756") (part "ACS756SCA-050B-PFF-T"))
    )
    (comp (ref "U12")
      (value "IR2109")
      (footprint "SOIC127P600X175-8N")
      (fields (field (name "MF") "Infineon"))
      (libsource (lib "IR2109") (part "IR2109"))
    )
    (comp (ref "U13")
      (value "IR2109")
      (footprint "SOIC127P600X175-8N")
      (fields (field (name "MF") "Infineon"))
      (libsource (lib "IR2109") (part "IR2109"))
    )
    (comp (ref "U14")
      (value "TPS54140ADGQ")
      (footprint "IC_XTR111AIDGQR")
      (description "3.5V to 42V Input, 1.5A Step-Down Converter with Eco-Mode 10-HVSSOP -40 to 125")
      (fields (field (name "MF") "Texas Instruments"))
      (libsource (lib "TPS54140A") (part "TPS54140ADGQ"))
    )
    (comp (ref "U15")
      (value "IR2109")
      (footprint "SOIC127P600X175-8N")
      (fields (field (name "MF") "Infineon"))
      (libsource (lib "IR2109") (part "IR2109"))
    )
    (comp (ref "U16")
      (value "IR2109")
      (footprint "SOIC127P600X175-8N")
      (fields (field (name "MF") "Infineon"))
      (libsource (lib "IR2109") (part "IR2109"))
    )
    (comp (ref "U17")
      (value "TPS54140ADGQ")
      (footprint "IC_XTR111AIDGQR")
      (description "3.5V to 42V Input, 1.5A Step-Down Converter with Eco-Mode 10-HVSSOP -40 to 125")
      (fields (field (name "MF") "Texas Instruments"))
      (libsource (lib "TPS54140A") (part "TPS54140ADGQ"))
    )
    (comp (ref "U18")
      (value "ACS758-150B")
      (footprint "PFF-5_ALM")
      (description "No Description Available")
      (fields
        (field (name "MANUFACTURER_PART_NUMBER") "ACS756SCA-050B-PFF-T")
        (field (name "COPYRIGHT") "Copyright (C) 2018 Accelerated Designs. All rights reserved")
      )
      (libsource (lib "ACS756") (part "ACS756SCA-050B-PFF-T"))
    )
    (comp (ref "U19")
      (value "ACS758-150B")
      (footprint "PFF-5_ALM")
      (description "No Description Available")
      (fields
        (field (name "MANUFACTURER_PART_NUMBER") "ACS756SCA-050B-PFF-T")
        (field (name "COPYRIGHT") "Copyright (C) 2018 Accelerated Designs. All rights reserved")
      )
      (libsource (lib "ACS756") (part "ACS756SCA-050B-PFF-T"))
    )
    (comp (ref "U20")
      (value "IR2109")
      (footprint "SOIC127P600X175-8N")
      (fields (field (name "MF") "Infineon"))
      (libsource (lib "IR2109") (part "IR2109"))
    )
    (comp (ref "U21")
      (value "IR2109")
      (footprint "SOIC127P600X175-8N")
      (fields (field (name "MF") "Infineon"))
      (libsource (lib "IR2109") (part "IR2109"))
    )
    (comp (ref "U22")
      (value "TPS54140ADGQ")
      (footprint "IC_XTR111AIDGQR")
      (description "3.5V to 42V Input, 1.5A Step-Down Converter with Eco-Mode 10-HVSSOP -40 to 125")
      (fields (field (name "MF") "Texas Instruments"))
      (libsource (lib "TPS54140A") (part "TPS54140ADGQ"))
    )
    (comp (ref "U23")
      (value "IR2109")
      (footprint "SOIC127P600X175-8N")
      (fields (field (name "MF") "Infineon"))
      (libsource (lib "IR2109") (part "IR2109"))
    )
    (comp (ref "U24")
      (value "IR2109")
      (footprint "SOIC127P600X175-8N")
      (fields (field (name "MF") "Infineon"))
      (libsource (lib "IR2109") (part "IR2109"))
    )
    (comp (ref "U25")
      (value "ACS758-150B")
      (footprint "PFF-5_ALM")
      (description "No Description Available")
      (fields
        (field (name "MANUFACTURER_PART_NUMBER") "ACS756SCA-050B-PFF-T")
        (field (name "COPYRIGHT") "Copyright (C) 2018 Accelerated Designs. All rights reserved")
      )
      (libsource (lib "ACS756") (part "ACS756SCA-050B-PFF-T"))
    )
    (comp (ref "U26")
      (value "ACS758-150B")
      (footprint "PFF-5_ALM")
      (description "No Description Available")
      (fields
        (field (name "MANUFACTURER_PART_NUMBER") "ACS756SCA-050B-PFF-T")
        (field (name "COPYRIGHT") "Copyright (C) 2018 Accelerated Designs. All rights reserved")
      )
      (libsource (lib "ACS756") (part "ACS756SCA-050B-PFF-T"))
    )
    (comp (ref "U27")
      (value "IR2109")
      (footprint "SOIC127P600X175-8N")
      (fields (field (name "MF") "Infineon"))
      (libsource (lib "IR2109") (part "IR2109"))
    )
    (comp (ref "U28")
      (value "IR2109")
      (footprint "SOIC127P600X175-8N")
      (fields (field (name "MF") "Infineon"))
      (libsource (lib "IR2109") (part "IR2109"))
    )
    (comp (ref "U29")
      (value "HCM1205")
      (footprint "KXG1205CL")
      (description "No Description Available")
      (fields (field (name "COPYRIGHT") "Copyright (C) 2018 Accelerated Designs. All rights reserved"))
      (libsource (lib "Buzzer") (part "HCM1205"))
    )
    (comp (ref "VD1")
      (value "MURS120T")
      (footprint "DIOM5436X247N")
      (description "No Description Available")
      (fields (field (name "COPYRIGHT") "Copyright (C) 2018 Accelerated Designs. All rights reserved"))
      (libsource (lib "MURS120T3") (part "MURS120T"))
    )
    (comp (ref "VD2")
      (value "MURS120T")
      (footprint "DIOM5436X247N")
      (description "No Description Available")
      (fields (field (name "COPYRIGHT") "Copyright (C) 2018 Accelerated Designs. All rights reserved"))
      (libsource (lib "MURS120T3") (part "MURS120T"))
    )
    (comp (ref "VD3")
      (value "MURS120T")
      (footprint "DIOM5436X247N")
      (description "No Description Available")
      (fields (field (name "COPYRIGHT") "Copyright (C) 2018 Accelerated Designs. All rights reserved"))
      (libsource (lib "MURS120T3") (part "MURS120T"))
    )
    (comp (ref "VD4")
      (value "MURS120T")
      (footprint "DIOM5436X247N")
      (description "No Description Available")
      (fields (field (name "COPYRIGHT") "Copyright (C) 2018 Accelerated Designs. All rights reserved"))
      (libsource (lib "MURS120T3") (part "MURS120T"))
    )
    (comp (ref "VD5")
      (value "MURS120T")
      (footprint "DIOM5436X247N")
      (description "No Description Available")
      (fields (field (name "COPYRIGHT") "Copyright (C) 2018 Accelerated Designs. All rights reserved"))
      (libsource (lib "MURS120T3") (part "MURS120T"))
    )
    (comp (ref "VD6")
      (value "MURS120T")
      (footprint "DIOM5436X247N")
      (description "No Description Available")
      (fields (field (name "COPYRIGHT") "Copyright (C) 2018 Accelerated Designs. All rights reserved"))
      (libsource (lib "MURS120T3") (part "MURS120T"))
    )
    (comp (ref "VD7")
      (value "10BQ040PBF")
      (footprint "DIODE_SMB")
      (description "No Description Available")
      (fields
        (field (name "MANUFACTURER_PART_NUMBER") "VS-10BQ040PBF")
        (field (name "COPYRIGHT") "Copyright (C) 2018 Accelerated Designs. All rights reserved")
      )
      (libsource (lib "10BQ040") (part "VS-10BQ040PBF"))
    )
    (comp (ref "VD8")
      (value "MURS120T")
      (footprint "DIOM5436X247N")
      (description "No Description Available")
      (fields (field (name "COPYRIGHT") "Copyright (C) 2018 Accelerated Designs. All rights reserved"))
      (libsource (lib "MURS120T3") (part "MURS120T"))
    )
    (comp (ref "VD9")
      (value "MURS120T")
      (footprint "DIOM5436X247N")
      (description "No Description Available")
      (fields (field (name "COPYRIGHT") "Copyright (C) 2018 Accelerated Designs. All rights reserved"))
      (libsource (lib "MURS120T3") (part "MURS120T"))
    )
    (comp (ref "VD10")
      (value "MURS120T")
      (footprint "DIOM5436X247N")
      (description "No Description Available")
      (fields (field (name "COPYRIGHT") "Copyright (C) 2018 Accelerated Designs. All rights reserved"))
      (libsource (lib "MURS120T3") (part "MURS120T"))
    )
    (comp (ref "VD11")
      (value "MURS120T")
      (footprint "DIOM5436X247N")
      (description "No Description Available")
      (fields (field (name "COPYRIGHT") "Copyright (C) 2018 Accelerated Designs. All rights reserved"))
      (libsource (lib "MURS120T3") (part "MURS120T"))
    )
    (comp (ref "VD12")
      (value "MURS120T")
      (footprint "DIOM5436X247N")
      (description "No Description Available")
      (fields (field (name "COPYRIGHT") "Copyright (C) 2018 Accelerated Designs. All rights reserved"))
      (libsource (lib "MURS120T3") (part "MURS120T"))
    )
    (comp (ref "VD13")
      (value "MURS120T")
      (footprint "DIOM5436X247N")
      (description "No Description Available")
      (fields (field (name "COPYRIGHT") "Copyright (C) 2018 Accelerated Designs. All rights reserved"))
      (libsource (lib "MURS120T3") (part "MURS120T"))
    )
    (comp (ref "VD14")
      (value "MURS120T")
      (footprint "DIOM5436X247N")
      (description "No Description Available")
      (fields (field (name "COPYRIGHT") "Copyright (C) 2018 Accelerated Designs. All rights reserved"))
      (libsource (lib "MURS120T3") (part "MURS120T"))
    )
    (comp (ref "VD15")
      (value "MURS120T")
      (footprint "DIOM5436X247N")
      (description "No Description Available")
      (fields (field (name "COPYRIGHT") "Copyright (C) 2018 Accelerated Designs. All rights reserved"))
      (libsource (lib "MURS120T3") (part "MURS120T"))
    )
    (comp (ref "VD16")
      (value "MURS120T")
      (footprint "DIOM5436X247N")
      (description "No Description Available")
      (fields (field (name "COPYRIGHT") "Copyright (C) 2018 Accelerated Designs. All rights reserved"))
      (libsource (lib "MURS120T3") (part "MURS120T"))
    )
    (comp (ref "VD17")
      (value "MURS120T")
      (footprint "DIOM5436X247N")
      (description "No Description Available")
      (fields (field (name "COPYRIGHT") "Copyright (C) 2018 Accelerated Designs. All rights reserved"))
      (libsource (lib "MURS120T3") (part "MURS120T"))
    )
    (comp (ref "VT1")
      (value "IRFB3077PBF")
      (footprint "PG-TO220-3")
      (description "No Description Available")
      (fields (field (name "COPYRIGHT") "Copyright (C) 2018 Accelerated Designs. All rights reserved"))
      (libsource (lib "TO220") (part "IRFB3077PBF"))
    )
    (comp (ref "VT2")
      (value "IRFB3077PBF")
      (footprint "PG-TO220-3")
      (description "No Description Available")
      (fields (field (name "COPYRIGHT") "Copyright (C) 2018 Accelerated Designs. All rights reserved"))
      (libsource (lib "TO220") (part "IRFB3077PBF"))
    )
    (comp (ref "VT3")
      (value "IRFB3077PBF")
      (footprint "PG-TO220-3")
      (description "No Description Available")
      (fields (field (name "COPYRIGHT") "Copyright (C) 2018 Accelerated Designs. All rights reserved"))
      (libsource (lib "TO220") (part "IRFB3077PBF"))
    )
    (comp (ref "VT4")
      (value "IRFB3077PBF")
      (footprint "PG-TO220-3")
      (description "No Description Available")
      (fields (field (name "COPYRIGHT") "Copyright (C) 2018 Accelerated Designs. All rights reserved"))
      (libsource (lib "TO220") (part "IRFB3077PBF"))
    )
    (comp (ref "VT5")
      (value "IRFB3077PBF")
      (footprint "PG-TO220-3")
      (description "No Description Available")
      (fields (field (name "COPYRIGHT") "Copyright (C) 2018 Accelerated Designs. All rights reserved"))
      (libsource (lib "TO220") (part "IRFB3077PBF"))
    )
    (comp (ref "VT6")
      (value "IRFB3077PBF")
      (footprint "PG-TO220-3")
      (description "No Description Available")
      (fields (field (name "COPYRIGHT") "Copyright (C) 2018 Accelerated Designs. All rights reserved"))
      (libsource (lib "TO220") (part "IRFB3077PBF"))
    )
    (comp (ref "VT7")
      (value "IRFB3077PBF")
      (footprint "PG-TO220-3")
      (description "No Description Available")
      (fields (field (name "COPYRIGHT") "Copyright (C) 2018 Accelerated Designs. All rights reserved"))
      (libsource (lib "TO220") (part "IRFB3077PBF"))
    )
    (comp (ref "VT8")
      (value "IRFB3077PBF")
      (footprint "PG-TO220-3")
      (description "No Description Available")
      (fields (field (name "COPYRIGHT") "Copyright (C) 2018 Accelerated Designs. All rights reserved"))
      (libsource (lib "TO220") (part "IRFB3077PBF"))
    )
    (comp (ref "VT9")
      (value "IRFB3077PBF")
      (footprint "PG-TO220-3")
      (description "No Description Available")
      (fields (field (name "COPYRIGHT") "Copyright (C) 2018 Accelerated Designs. All rights reserved"))
      (libsource (lib "TO220") (part "IRFB3077PBF"))
    )
    (comp (ref "VT10")
      (value "IRFB3077PBF")
      (footprint "PG-TO220-3")
      (description "No Description Available")
      (fields (field (name "COPYRIGHT") "Copyright (C) 2018 Accelerated Designs. All rights reserved"))
      (libsource (lib "TO220") (part "IRFB3077PBF"))
    )
    (comp (ref "VT11")
      (value "IRFB3077PBF")
      (footprint "PG-TO220-3")
      (description "No Description Available")
      (fields (field (name "COPYRIGHT") "Copyright (C) 2018 Accelerated Designs. All rights reserved"))
      (libsource (lib "TO220") (part "IRFB3077PBF"))
    )
    (comp (ref "VT12")
      (value "IRFB3077PBF")
      (footprint "PG-TO220-3")
      (description "No Description Available")
      (fields (field (name "COPYRIGHT") "Copyright (C) 2018 Accelerated Designs. All rights reserved"))
      (libsource (lib "TO220") (part "IRFB3077PBF"))
    )
    (comp (ref "VT13")
      (value "IRFB3077PBF")
      (footprint "PG-TO220-3")
      (description "No Description Available")
      (fields (field (name "COPYRIGHT") "Copyright (C) 2018 Accelerated Designs. All rights reserved"))
      (libsource (lib "TO220") (part "IRFB3077PBF"))
    )
    (comp (ref "VT14")
      (value "IRFB3077PBF")
      (footprint "PG-TO220-3")
      (description "No Description Available")
      (fields (field (name "COPYRIGHT") "Copyright (C) 2018 Accelerated Designs. All rights reserved"))
      (libsource (lib "TO220") (part "IRFB3077PBF"))
    )
    (comp (ref "VT15")
      (value "IRFB3077PBF")
      (footprint "PG-TO220-3")
      (description "No Description Available")
      (fields (field (name "COPYRIGHT") "Copyright (C) 2018 Accelerated Designs. All rights reserved"))
      (libsource (lib "TO220") (part "IRFB3077PBF"))
    )
    (comp (ref "VT16")
      (value "IRFB3077PBF")
      (footprint "PG-TO220-3")
      (description "No Description Available")
      (fields (field (name "COPYRIGHT") "Copyright (C) 2018 Accelerated Designs. All rights reserved"))
      (libsource (lib "TO220") (part "IRFB3077PBF"))
    )
    (comp (ref "VT17")
      (value "IRFB3077PBF")
      (footprint "PG-TO220-3")
      (description "No Description Available")
      (fields (field (name "COPYRIGHT") "Copyright (C) 2018 Accelerated Designs. All rights reserved"))
      (libsource (lib "TO220") (part "IRFB3077PBF"))
    )
    (comp (ref "VT18")
      (value "IRFB3077PBF")
      (footprint "PG-TO220-3")
      (description "No Description Available")
      (fields (field (name "COPYRIGHT") "Copyright (C) 2018 Accelerated Designs. All rights reserved"))
      (libsource (lib "TO220") (part "IRFB3077PBF"))
    )
    (comp (ref "VT19")
      (value "IRFB3077PBF")
      (footprint "PG-TO220-3")
      (description "No Description Available")
      (fields (field (name "COPYRIGHT") "Copyright (C) 2018 Accelerated Designs. All rights reserved"))
      (libsource (lib "TO220") (part "IRFB3077PBF"))
    )
    (comp (ref "VT20")
      (value "IRFB3077PBF")
      (footprint "PG-TO220-3")
      (description "No Description Available")
      (fields (field (name "COPYRIGHT") "Copyright (C) 2018 Accelerated Designs. All rights reserved"))
      (libsource (lib "TO220") (part "IRFB3077PBF"))
    )
    (comp (ref "VT21")
      (value "IRFB3077PBF")
      (footprint "PG-TO220-3")
      (description "No Description Available")
      (fields (field (name "COPYRIGHT") "Copyright (C) 2018 Accelerated Designs. All rights reserved"))
      (libsource (lib "TO220") (part "IRFB3077PBF"))
    )
    (comp (ref "VT22")
      (value "IRFB3077PBF")
      (footprint "PG-TO220-3")
      (description "No Description Available")
      (fields (field (name "COPYRIGHT") "Copyright (C) 2018 Accelerated Designs. All rights reserved"))
      (libsource (lib "TO220") (part "IRFB3077PBF"))
    )
    (comp (ref "VT23")
      (value "IRFB3077PBF")
      (footprint "PG-TO220-3")
      (description "No Description Available")
      (fields (field (name "COPYRIGHT") "Copyright (C) 2018 Accelerated Designs. All rights reserved"))
      (libsource (lib "TO220") (part "IRFB3077PBF"))
    )
    (comp (ref "VT24")
      (value "IRFB3077PBF")
      (footprint "PG-TO220-3")
      (description "No Description Available")
      (fields (field (name "COPYRIGHT") "Copyright (C) 2018 Accelerated Designs. All rights reserved"))
      (libsource (lib "TO220") (part "IRFB3077PBF"))
    )
    (comp (ref "VT25")
      (value "IRFB3077PBF")
      (footprint "PG-TO220-3")
      (description "No Description Available")
      (fields (field (name "COPYRIGHT") "Copyright (C) 2018 Accelerated Designs. All rights reserved"))
      (libsource (lib "TO220") (part "IRFB3077PBF"))
    )
    (comp (ref "VT26")
      (value "IRFB3077PBF")
      (footprint "PG-TO220-3")
      (description "No Description Available")
      (fields (field (name "COPYRIGHT") "Copyright (C) 2018 Accelerated Designs. All rights reserved"))
      (libsource (lib "TO220") (part "IRFB3077PBF"))
    )
    (comp (ref "VT27")
      (value "IRFB3077PBF")
      (footprint "PG-TO220-3")
      (description "No Description Available")
      (fields (field (name "COPYRIGHT") "Copyright (C) 2018 Accelerated Designs. All rights reserved"))
      (libsource (lib "TO220") (part "IRFB3077PBF"))
    )
    (comp (ref "VT28")
      (value "IRFB3077PBF")
      (footprint "PG-TO220-3")
      (description "No Description Available")
      (fields (field (name "COPYRIGHT") "Copyright (C) 2018 Accelerated Designs. All rights reserved"))
      (libsource (lib "TO220") (part "IRFB3077PBF"))
    )
    (comp (ref "VT29")
      (value "IRFB3077PBF")
      (footprint "PG-TO220-3")
      (description "No Description Available")
      (fields (field (name "COPYRIGHT") "Copyright (C) 2018 Accelerated Designs. All rights reserved"))
      (libsource (lib "TO220") (part "IRFB3077PBF"))
    )
    (comp (ref "VT30")
      (value "IRFB3077PBF")
      (footprint "PG-TO220-3")
      (description "No Description Available")
      (fields (field (name "COPYRIGHT") "Copyright (C) 2018 Accelerated Designs. All rights reserved"))
      (libsource (lib "TO220") (part "IRFB3077PBF"))
    )
    (comp (ref "VT31")
      (value "IRFB3077PBF")
      (footprint "PG-TO220-3")
      (description "No Description Available")
      (fields (field (name "COPYRIGHT") "Copyright (C) 2018 Accelerated Designs. All rights reserved"))
      (libsource (lib "TO220") (part "IRFB3077PBF"))
    )
    (comp (ref "VT32")
      (value "IRFB3077PBF")
      (footprint "PG-TO220-3")
      (description "No Description Available")
      (fields (field (name "COPYRIGHT") "Copyright (C) 2018 Accelerated Designs. All rights reserved"))
      (libsource (lib "TO220") (part "IRFB3077PBF"))
    )
    (comp (ref "VT33")
      (value "2N7002")
      (footprint "TO-236AB")
      (description "No Description Available")
      (fields
        (field (name "MANUFACTURER_PART_NUMBER") "2N7002,215")
        (field (name "COPYRIGHT") "Copyright (C) 2016 Accelerated Designs. All rights reserved")
      )
      (libsource (lib "2N7002") (part "2N7002,215"))
    )
    (comp (ref "X1") (value "XT30") (footprint "XT30") (libsource (lib "XT") (part "XT30")))
    (comp (ref "X2") (value "XT30") (footprint "XT30") (libsource (lib "XT") (part "XT30")))
    (comp (ref "X3")
      (value "B4B-XH-A (LF)(SN)")
      (footprint "CONN_B4B-XH-A (L")
      (description "No Description Available")
      (fields (field (name "COPYRIGHT") "Copyright (C) 2018 Accelerated Designs. All rights reserved"))
      (libsource (lib "B4B-XH-A") (part "B4B-XH-A (LF)(SN"))
    )
    (comp (ref "X4")
      (value "B4B-XH-A (LF)(SN)")
      (footprint "CONN_B4B-XH-A (L")
      (description "No Description Available")
      (fields (field (name "COPYRIGHT") "Copyright (C) 2018 Accelerated Designs. All rights reserved"))
      (libsource (lib "") (part "B4B-XH-A (LF)(SN_1"))
    )
    (comp (ref "X5") (value "XT-60") (footprint "XT-60") (libsource (lib "XT") (part "XT60")))
    (comp (ref "X6") (value "XT30") (footprint "XT30") (libsource (lib "XT") (part "XT30")))
    (comp (ref "X7") (value "XT30") (footprint "XT30") (libsource (lib "XT") (part "XT30")))
    (comp (ref "X8") (value "XT30") (footprint "XT30") (libsource (lib "XT") (part "XT30")))
    (comp (ref "X9") (value "XT30") (footprint "XT30") (libsource (lib "XT") (part "XT30")))
    (comp (ref "X10") (value "XT30") (footprint "XT30") (libsource (lib "XT") (part "XT30")))
    (comp (ref "X11") (value "XT30") (footprint "XT30") (libsource (lib "XT") (part "XT30")))
  )
  (nets
    (net (code "1") (name "+Bat") (class "Default")
      (node (ref "C10") (pin "1") (pinfunction "1_1") (pintype "passive"))
      (node (ref "C105") (pin "1") (pinfunction "1_1") (pintype "passive"))
      (node (ref "C106") (pin "1") (pinfunction "1_1") (pintype "passive"))
      (node (ref "C117") (pin "1") (pinfunction "1_1") (pintype "passive"))
      (node (ref "C118") (pin "1") (pinfunction "1_1") (pintype "passive"))
      (node (ref "C23") (pin "1") (pinfunction "1_1") (pintype "passive"))
      (node (ref "C24") (pin "1") (pinfunction "1_1") (pintype "passive"))
      (node (ref "C33") (pin "1") (pinfunction "1_1") (pintype "passive"))
      (node (ref "C34") (pin "1") (pinfunction "1_1") (pintype "passive"))
      (node (ref "C35") (pin "1") (pinfunction "1_1") (pintype "passive"))
      (node (ref "C48") (pin "1") (pinfunction "1_1") (pintype "passive"))
      (node (ref "C49") (pin "1") (pinfunction "1_1") (pintype "passive"))
      (node (ref "C50") (pin "1") (pinfunction "1_1") (pintype "passive"))
      (node (ref "C52") (pin "2") (pinfunction "2_2") (pintype "passive"))
      (node (ref "C53") (pin "2") (pinfunction "2_2") (pintype "passive"))
      (node (ref "C54") (pin "2") (pinfunction "2_2") (pintype "passive"))
      (node (ref "C65") (pin "1") (pinfunction "1_1") (pintype "passive"))
      (node (ref "C66") (pin "1") (pinfunction "1_1") (pintype "passive"))
      (node (ref "C69") (pin "1") (pinfunction "1_1") (pintype "passive"))
      (node (ref "C71") (pin "2") (pinfunction "2_2") (pintype "passive"))
      (node (ref "C72") (pin "2") (pinfunction "2_2") (pintype "passive"))
      (node (ref "C73") (pin "2") (pinfunction "2_2") (pintype "passive"))
      (node (ref "C86") (pin "1") (pinfunction "1_1") (pintype "passive"))
      (node (ref "C87") (pin "1") (pinfunction "1_1") (pintype "passive"))
      (node (ref "C9") (pin "1") (pinfunction "1_1") (pintype "passive"))
      (node (ref "C90") (pin "1") (pinfunction "1_1") (pintype "passive"))
      (node (ref "C92") (pin "2") (pinfunction "2_2") (pintype "passive"))
      (node (ref "C93") (pin "2") (pinfunction "2_2") (pintype "passive"))
      (node (ref "C94") (pin "2") (pinfunction "2_2") (pintype "passive"))
      (node (ref "U14") (pin "2") (pinfunction "VIN_2") (pintype "input"))
      (node (ref "U17") (pin "2") (pinfunction "VIN_2") (pintype "input"))
      (node (ref "U22") (pin "2") (pinfunction "VIN_2") (pintype "input"))
      (node (ref "VT1") (pin "2") (pinfunction "2_2") (pintype "passive"))
      (node (ref "VT10") (pin "2") (pinfunction "2_2") (pintype "passive"))
      (node (ref "VT13") (pin "2") (pinfunction "2_2") (pintype "passive"))
      (node (ref "VT14") (pin "2") (pinfunction "2_2") (pintype "passive"))
      (node (ref "VT17") (pin "2") (pinfunction "2_2") (pintype "passive"))
      (node (ref "VT18") (pin "2") (pinfunction "2_2") (pintype "passive"))
      (node (ref "VT2") (pin "2") (pinfunction "2_2") (pintype "passive"))
      (node (ref "VT21") (pin "2") (pinfunction "2_2") (pintype "passive"))
      (node (ref "VT22") (pin "2") (pinfunction "2_2") (pintype "passive"))
      (node (ref "VT25") (pin "2") (pinfunction "2_2") (pintype "passive"))
      (node (ref "VT26") (pin "2") (pinfunction "2_2") (pintype "passive"))
      (node (ref "VT29") (pin "2") (pinfunction "2_2") (pintype "passive"))
      (node (ref "VT30") (pin "2") (pinfunction "2_2") (pintype "passive"))
      (node (ref "VT5") (pin "2") (pinfunction "2_2") (pintype "passive"))
      (node (ref "VT6") (pin "2") (pinfunction "2_2") (pintype "passive"))
      (node (ref "VT9") (pin "2") (pinfunction "2_2") (pintype "passive"))
      (node (ref "X5") (pin "1") (pinfunction "Bat_+_1") (pintype "power_in"))
    )
    (net (code "2") (name "/CANH") (class "Default")
      (node (ref "CR3") (pin "1") (pinfunction "CATHODE_1") (pintype "passive"))
      (node (ref "R5") (pin "1") (pinfunction "1_1") (pintype "passive"))
      (node (ref "U3") (pin "7") (pinfunction "CANH_7") (pintype "bidirectional"))
      (node (ref "X3") (pin "2") (pinfunction "2_2") (pintype "passive"))
      (node (ref "X4") (pin "2") (pinfunction "2_2") (pintype "passive"))
    )
    (net (code "3") (name "/CANL") (class "Default")
      (node (ref "CR3") (pin "2") (pinfunction "ANODE_2") (pintype "passive"))
      (node (ref "R5") (pin "2") (pinfunction "2_2") (pintype "passive"))
      (node (ref "U3") (pin "6") (pinfunction "CANL_6") (pintype "bidirectional"))
      (node (ref "X3") (pin "3") (pinfunction "3_3") (pintype "passive"))
      (node (ref "X4") (pin "3") (pinfunction "3_3") (pintype "passive"))
    )
    (net (code "4") (name "/CAN_RX") (class "Default")
      (node (ref "TB1") (pin "P1_36") (pinfunction "PB12_P1_36") (pintype "bidirectional"))
      (node (ref "U3") (pin "4") (pinfunction "RXD_4") (pintype "output"))
    )
    (net (code "5") (name "/CAN_TX") (class "Default")
      (node (ref "TB1") (pin "P1_37") (pinfunction "PB13_P1_37") (pintype "bidirectional"))
      (node (ref "U3") (pin "1") (pinfunction "TXD_1") (pintype "input"))
    )
    (net (code "6") (name "/CURRENT_ML1") (class "Default")
      (node (ref "C12") (pin "1") (pinfunction "1_1") (pintype "passive"))
      (node (ref "R6") (pin "2") (pinfunction "2_2") (pintype "passive"))
      (node (ref "TB1") (pin "P1_16") (pinfunction "PA4_P1_16") (pintype "bidirectional"))
    )
    (net (code "7") (name "/CURRENT_ML2") (class "Default")
      (node (ref "C13") (pin "1") (pinfunction "1_1") (pintype "passive"))
      (node (ref "R7") (pin "2") (pinfunction "2_2") (pintype "passive"))
      (node (ref "TB1") (pin "P1_15") (pinfunction "PA5_P1_15") (pintype "bidirectional"))
    )
    (net (code "8") (name "/CURRENT_ML3") (class "Default")
      (node (ref "C36") (pin "1") (pinfunction "1_1") (pintype "passive"))
      (node (ref "R16") (pin "2") (pinfunction "2_2") (pintype "passive"))
      (node (ref "TB1") (pin "P1_8") (pinfunction "PC0_P1_8") (pintype "bidirectional"))
    )
    (net (code "9") (name "/CURRENT_ML4") (class "Default")
      (node (ref "C37") (pin "1") (pinfunction "1_1") (pintype "passive"))
      (node (ref "R17") (pin "2") (pinfunction "2_2") (pintype "passive"))
      (node (ref "TB1") (pin "P1_7") (pinfunction "PC1_P1_7") (pintype "bidirectional"))
    )
    (net (code "10") (name "/CURRENT_MR1") (class "Default")
      (node (ref "C74") (pin "1") (pinfunction "1_1") (pintype "passive"))
      (node (ref "R32") (pin "2") (pinfunction "2_2") (pintype "passive"))
      (node (ref "TB1") (pin "P1_10") (pinfunction "PC2_P1_10") (pintype "bidirectional"))
    )
    (net (code "11") (name "/CURRENT_MR2") (class "Default")
      (node (ref "C75") (pin "1") (pinfunction "1_1") (pintype "passive"))
      (node (ref "R33") (pin "2") (pinfunction "2_2") (pintype "passive"))
      (node (ref "TB1") (pin "P1_9") (pinfunction "PC3_P1_9") (pintype "bidirectional"))
    )
    (net (code "12") (name "/CURRENT_MR3") (class "Default")
      (node (ref "C107") (pin "1") (pinfunction "1_1") (pintype "passive"))
      (node (ref "R48") (pin "2") (pinfunction "2_2") (pintype "passive"))
      (node (ref "TB1") (pin "P1_20") (pinfunction "PC4_P1_20") (pintype "bidirectional"))
    )
    (net (code "13") (name "/CURRENT_MR4") (class "Default")
      (node (ref "C108") (pin "1") (pinfunction "1_1") (pintype "passive"))
      (node (ref "R49") (pin "2") (pinfunction "2_2") (pintype "passive"))
      (node (ref "TB1") (pin "P1_19") (pinfunction "PC5_P1_19") (pintype "bidirectional"))
    )
    (net (code "14") (name "/Lo1_ML1") (class "Default")
      (node (ref "TB1") (pin "P2_36") (pinfunction "PD0_P2_36") (pintype "bidirectional"))
      (node (ref "U1") (pin "3") (pinfunction "/SD_3") (pintype "input"))
    )
    (net (code "15") (name "/Lo1_ML2") (class "Default")
      (node (ref "TB1") (pin "P2_34") (pinfunction "PD2_P2_34") (pintype "bidirectional"))
      (node (ref "U2") (pin "3") (pinfunction "/SD_3") (pintype "input"))
    )
    (net (code "16") (name "/Lo1_ML3") (class "Default")
      (node (ref "TB1") (pin "P1_40") (pinfunction "PD8_P1_40") (pintype "bidirectional"))
      (node (ref "U8") (pin "3") (pinfunction "/SD_3") (pintype "input"))
    )
    (net (code "17") (name "/Lo1_ML4") (class "Default")
      (node (ref "TB1") (pin "P1_42") (pinfunction "PD10_P1_42") (pintype "bidirectional"))
      (node (ref "U9") (pin "3") (pinfunction "/SD_3") (pintype "input"))
    )
    (net (code "18") (name "/Lo1_MR1") (class "Default")
      (node (ref "TB1") (pin "P2_17") (pinfunction "PE0_P2_17") (pintype "bidirectional"))
      (node (ref "U15") (pin "3") (pinfunction "/SD_3") (pintype "input"))
    )
    (net (code "19") (name "/Lo1_MR2") (class "Default")
      (node (ref "TB1") (pin "P2_15") (pinfunction "PE2_P2_15") (pintype "bidirectional"))
      (node (ref "U16") (pin "3") (pinfunction "/SD_3") (pintype "input"))
    )
    (net (code "20") (name "/Lo1_MR3") (class "Default")
      (node (ref "TB1") (pin "P2_13") (pinfunction "PE4_P2_13") (pintype "bidirectional"))
      (node (ref "U23") (pin "3") (pinfunction "/SD_3") (pintype "input"))
    )
    (net (code "21") (name "/Lo1_MR4") (class "Default")
      (node (ref "TB1") (pin "P2_11") (pinfunction "PE6_P2_11") (pintype "bidirectional"))
      (node (ref "U24") (pin "3") (pinfunction "/SD_3") (pintype "input"))
    )
    (net (code "22") (name "/Lo2_ML1") (class "Default")
      (node (ref "TB1") (pin "P2_33") (pinfunction "PD1_P2_33") (pintype "bidirectional"))
      (node (ref "U6") (pin "3") (pinfunction "/SD_3") (pintype "input"))
    )
    (net (code "23") (name "/Lo2_ML2") (class "Default")
      (node (ref "TB1") (pin "P2_27") (pinfunction "PD7_P2_27") (pintype "bidirectional"))
      (node (ref "U7") (pin "3") (pinfunction "/SD_3") (pintype "input"))
    )
    (net (code "24") (name "/Lo2_ML3") (class "Default")
      (node (ref "TB1") (pin "P1_41") (pinfunction "PD9_P1_41") (pintype "bidirectional"))
      (node (ref "U12") (pin "3") (pinfunction "/SD_3") (pintype "input"))
    )
    (net (code "25") (name "/Lo2_ML4") (class "Default")
      (node (ref "TB1") (pin "P1_43") (pinfunction "PD11_P1_43") (pintype "bidirectional"))
      (node (ref "U13") (pin "3") (pinfunction "/SD_3") (pintype "input"))
    )
    (net (code "26") (name "/Lo2_MR1") (class "Default")
      (node (ref "TB1") (pin "P2_18") (pinfunction "PE1_P2_18") (pintype "bidirectional"))
      (node (ref "U20") (pin "3") (pinfunction "/SD_3") (pintype "input"))
    )
    (net (code "27") (name "/Lo2_MR2") (class "Default")
      (node (ref "TB1") (pin "P2_16") (pinfunction "PE3_P2_16") (pintype "bidirectional"))
      (node (ref "U21") (pin "3") (pinfunction "/SD_3") (pintype "input"))
    )
    (net (code "28") (name "/Lo2_MR3") (class "Default")
      (node (ref "TB1") (pin "P2_14") (pinfunction "PE5_P2_14") (pintype "bidirectional"))
      (node (ref "U27") (pin "3") (pinfunction "/SD_3") (pintype "input"))
    )
    (net (code "29") (name "/Lo2_MR4") (class "Default")
      (node (ref "TB1") (pin "P1_25") (pinfunction "PE7_P1_25") (pintype "bidirectional"))
      (node (ref "U28") (pin "3") (pinfunction "/SD_3") (pintype "input"))
    )
    (net (code "30") (name "/PWMB_ML1") (class "Default")
      (node (ref "TB1") (pin "P1_11") (pinfunction "PA1_P1_11") (pintype "bidirectional"))
      (node (ref "U6") (pin "2") (pinfunction "IN_2") (pintype "input"))
    )
    (net (code "31") (name "/PWMB_ML2") (class "Default")
      (node (ref "TB1") (pin "P1_13") (pinfunction "PA3_P1_13") (pintype "bidirectional"))
      (node (ref "U7") (pin "2") (pinfunction "IN_2") (pintype "input"))
    )
    (net (code "32") (name "/PWMB_ML3") (class "Default")
      (node (ref "TB1") (pin "P1_17") (pinfunction "PA7_P1_17") (pintype "bidirectional"))
      (node (ref "U12") (pin "2") (pinfunction "IN_2") (pintype "input"))
    )
    (net (code "33") (name "/PWMB_ML4") (class "Default")
      (node (ref "TB1") (pin "P1_21") (pinfunction "PB1_P1_21") (pintype "bidirectional"))
      (node (ref "U13") (pin "2") (pinfunction "IN_2") (pintype "input"))
    )
    (net (code "34") (name "/PWMB_MR1") (class "Default")
      (node (ref "TB1") (pin "P1_29") (pinfunction "PE11_P1_29") (pintype "bidirectional"))
      (node (ref "U20") (pin "2") (pinfunction "IN_2") (pintype "input"))
    )
    (net (code "35") (name "/PWMB_MR2") (class "Default")
      (node (ref "TB1") (pin "P1_32") (pinfunction "PE14_P1_32") (pintype "bidirectional"))
      (node (ref "U21") (pin "2") (pinfunction "IN_2") (pintype "input"))
    )
    (net (code "36") (name "/PWMB_MR3") (class "Default")
      (node (ref "TB1") (pin "P2_48") (pinfunction "PC7_P2_48") (pintype "bidirectional"))
      (node (ref "U27") (pin "2") (pinfunction "IN_2") (pintype "input"))
    )
    (net (code "37") (name "/PWMB_MR4") (class "Default")
      (node (ref "TB1") (pin "P2_46") (pinfunction "PC9_P2_46") (pintype "bidirectional"))
      (node (ref "U28") (pin "2") (pinfunction "IN_2") (pintype "input"))
    )
    (net (code "38") (name "/PWMF_ML1") (class "Default")
      (node (ref "R54") (pin "1") (pinfunction "1_1") (pintype "passive"))
      (node (ref "R55") (pin "1") (pinfunction "1_1") (pintype "passive"))
      (node (ref "U1") (pin "2") (pinfunction "IN_2") (pintype "input"))
    )
    (net (code "39") (name "/PWMF_ML2") (class "Default")
      (node (ref "TB1") (pin "P1_14") (pinfunction "PA2_P1_14") (pintype "bidirectional"))
      (node (ref "U2") (pin "2") (pinfunction "IN_2") (pintype "input"))
    )
    (net (code "40") (name "/PWMF_ML3") (class "Default")
      (node (ref "TB1") (pin "P1_18") (pinfunction "PA6_P1_18") (pintype "bidirectional"))
      (node (ref "U8") (pin "2") (pinfunction "IN_2") (pintype "input"))
    )
    (net (code "41") (name "/PWMF_ML4") (class "Default")
      (node (ref "TB1") (pin "P1_22") (pinfunction "PB0_P1_22") (pintype "bidirectional"))
      (node (ref "U9") (pin "2") (pinfunction "IN_2") (pintype "input"))
    )
    (net (code "42") (name "/PWMF_MR1") (class "Default")
      (node (ref "TB1") (pin "P1_27") (pinfunction "PE9_P1_27") (pintype "bidirectional"))
      (node (ref "U15") (pin "2") (pinfunction "IN_2") (pintype "input"))
    )
    (net (code "43") (name "/PWMF_MR2") (class "Default")
      (node (ref "TB1") (pin "P1_31") (pinfunction "PE13_P1_31") (pintype "bidirectional"))
      (node (ref "U16") (pin "2") (pinfunction "IN_2") (pintype "input"))
    )
    (net (code "44") (name "/PWMF_MR3") (class "Default")
      (node (ref "TB1") (pin "P2_47") (pinfunction "PC6_P2_47") (pintype "bidirectional"))
      (node (ref "U23") (pin "2") (pinfunction "IN_2") (pintype "input"))
    )
    (net (code "45") (name "/PWMF_MR4") (class "Default")
      (node (ref "TB1") (pin "P2_45") (pinfunction "PC8_P2_45") (pintype "bidirectional"))
      (node (ref "U24") (pin "2") (pinfunction "IN_2") (pintype "input"))
    )
    (net (code "46") (name "/STBY") (class "Default")
      (node (ref "TB1") (pin "P2_26") (pinfunction "PB5_P2_26") (pintype "bidirectional"))
      (node (ref "U3") (pin "8") (pinfunction "STBY_8") (pintype "input"))
    )
    (net (code "47") (name "/USART2_Rx") (class "Default")
      (node (ref "J1") (pin "7") (pinfunction "IO17_7") (pintype "bidirectional"))
      (node (ref "TB1") (pin "P2_29") (pinfunction "PD5_P2_29") (pintype "bidirectional"))
    )
    (net (code "48") (name "/USART2_Tx") (class "Default")
      (node (ref "J1") (pin "6") (pinfunction "IO16_6") (pintype "bidirectional"))
      (node (ref "TB1") (pin "P2_30") (pinfunction "PD6_P2_30") (pintype "bidirectional"))
    )
    (net (code "49") (name "3.3V") (class "Default")
      (node (ref "C14") (pin "2") (pinfunction "2_2") (pintype "passive"))
      (node (ref "C89") (pin "1") (pinfunction "1_1") (pintype "passive"))
      (node (ref "L3") (pin "1") (pinfunction "1_1") (pintype "passive"))
      (node (ref "R40") (pin "1") (pinfunction "1_1") (pintype "passive"))
      (node (ref "U10") (pin "1") (pinfunction "VCC_1") (pintype "power_in"))
      (node (ref "U11") (pin "1") (pinfunction "VCC_1") (pintype "power_in"))
      (node (ref "U18") (pin "1") (pinfunction "VCC_1") (pintype "power_in"))
      (node (ref "U19") (pin "1") (pinfunction "VCC_1") (pintype "power_in"))
      (node (ref "U25") (pin "1") (pinfunction "VCC_1") (pintype "power_in"))
      (node (ref "U26") (pin "1") (pinfunction "VCC_1") (pintype "power_in"))
      (node (ref "U3") (pin "5") (pinfunction "Vio_5") (pintype "passive"))
      (node (ref "U4") (pin "1") (pinfunction "VCC_1") (pintype "power_in"))
      (node (ref "U5") (pin "1") (pinfunction "VCC_1") (pintype "power_in"))
    )
    (net (code "50") (name "5V") (class "Default")
      (node (ref "C11") (pin "2") (pinfunction "2_2") (pintype "passive"))
      (node (ref "C68") (pin "1") (pinfunction "1_1") (pintype "passive"))
      (node (ref "J1") (pin "30") (pinfunction "VIN_30") (pintype "bidirectional"))
      (node (ref "L2") (pin "1") (pinfunction "1_1") (pintype "passive"))
      (node (ref "R28") (pin "1") (pinfunction "1_1") (pintype "passive"))
      (node (ref "TB1") (pin "P2_3") (pinfunction "5V_P2_3") (pintype "power_in"))
      (node (ref "TB1") (pin "P2_4") (pinfunction "5V_P2_4") (pintype "power_in"))
      (node (ref "U29") (pin "2") (pinfunction "+_2") (pintype "passive"))
      (node (ref "U3") (pin "3") (pinfunction "VDD_3") (pintype "power_in"))
      (node (ref "VD7") (pin "1") (pinfunction "1_1") (pintype "passive"))
      (node (ref "X3") (pin "1") (pinfunction "1_1") (pintype "passive"))
      (node (ref "X4") (pin "1") (pinfunction "1_1") (pintype "passive"))
    )
    (net (code "51") (name "12V") (class "Default")
      (node (ref "C100") (pin "1") (pinfunction "1_1") (pintype "passive"))
      (node (ref "C101") (pin "1") (pinfunction "1_1") (pintype "passive"))
      (node (ref "C103") (pin "2") (pinfunction "2_2") (pintype "passive"))
      (node (ref "C104") (pin "2") (pinfunction "2_2") (pintype "passive"))
      (node (ref "C113") (pin "1") (pinfunction "1_1") (pintype "passive"))
      (node (ref "C114") (pin "1") (pinfunction "1_1") (pintype "passive"))
      (node (ref "C115") (pin "2") (pinfunction "2_2") (pintype "passive"))
      (node (ref "C116") (pin "2") (pinfunction "2_2") (pintype "passive"))
      (node (ref "C19") (pin "1") (pinfunction "1_1") (pintype "passive"))
      (node (ref "C20") (pin "1") (pinfunction "1_1") (pintype "passive"))
      (node (ref "C21") (pin "2") (pinfunction "2_2") (pintype "passive"))
      (node (ref "C22") (pin "2") (pinfunction "2_2") (pintype "passive"))
      (node (ref "C29") (pin "1") (pinfunction "1_1") (pintype "passive"))
      (node (ref "C30") (pin "1") (pinfunction "1_1") (pintype "passive"))
      (node (ref "C31") (pin "2") (pinfunction "2_2") (pintype "passive"))
      (node (ref "C32") (pin "2") (pinfunction "2_2") (pintype "passive"))
      (node (ref "C43") (pin "1") (pinfunction "1_1") (pintype "passive"))
      (node (ref "C44") (pin "1") (pinfunction "1_1") (pintype "passive"))
      (node (ref "C45") (pin "2") (pinfunction "2_2") (pintype "passive"))
      (node (ref "C46") (pin "2") (pinfunction "2_2") (pintype "passive"))
      (node (ref "C47") (pin "1") (pinfunction "1_1") (pintype "passive"))
      (node (ref "C5") (pin "1") (pinfunction "1_1") (pintype "passive"))
      (node (ref "C6") (pin "1") (pinfunction "1_1") (pintype "passive"))
      (node (ref "C61") (pin "1") (pinfunction "1_1") (pintype "passive"))
      (node (ref "C62") (pin "1") (pinfunction "1_1") (pintype "passive"))
      (node (ref "C63") (pin "2") (pinfunction "2_2") (pintype "passive"))
      (node (ref "C64") (pin "2") (pinfunction "2_2") (pintype "passive"))
      (node (ref "C7") (pin "2") (pinfunction "2_2") (pintype "passive"))
      (node (ref "C8") (pin "2") (pinfunction "2_2") (pintype "passive"))
      (node (ref "C82") (pin "1") (pinfunction "1_1") (pintype "passive"))
      (node (ref "C83") (pin "1") (pinfunction "1_1") (pintype "passive"))
      (node (ref "C84") (pin "2") (pinfunction "2_2") (pintype "passive"))
      (node (ref "C85") (pin "2") (pinfunction "2_2") (pintype "passive"))
      (node (ref "L1") (pin "1") (pinfunction "1_1") (pintype "passive"))
      (node (ref "R20") (pin "1") (pinfunction "1_1") (pintype "passive"))
      (node (ref "U1") (pin "1") (pinfunction "VCC_1") (pintype "power_in"))
      (node (ref "U12") (pin "1") (pinfunction "VCC_1") (pintype "power_in"))
      (node (ref "U13") (pin "1") (pinfunction "VCC_1") (pintype "power_in"))
      (node (ref "U15") (pin "1") (pinfunction "VCC_1") (pintype "power_in"))
      (node (ref "U16") (pin "1") (pinfunction "VCC_1") (pintype "power_in"))
      (node (ref "U2") (pin "1") (pinfunction "VCC_1") (pintype "power_in"))
      (node (ref "U20") (pin "1") (pinfunction "VCC_1") (pintype "power_in"))
      (node (ref "U21") (pin "1") (pinfunction "VCC_1") (pintype "power_in"))
      (node (ref "U23") (pin "1") (pinfunction "VCC_1") (pintype "power_in"))
      (node (ref "U24") (pin "1") (pinfunction "VCC_1") (pintype "power_in"))
      (node (ref "U27") (pin "1") (pinfunction "VCC_1") (pintype "power_in"))
      (node (ref "U28") (pin "1") (pinfunction "VCC_1") (pintype "power_in"))
      (node (ref "U6") (pin "1") (pinfunction "VCC_1") (pintype "power_in"))
      (node (ref "U7") (pin "1") (pinfunction "VCC_1") (pintype "power_in"))
      (node (ref "U8") (pin "1") (pinfunction "VCC_1") (pintype "power_in"))
      (node (ref "U9") (pin "1") (pinfunction "VCC_1") (pintype "power_in"))
      (node (ref "VD1") (pin "2") (pinfunction "2_2") (pintype "passive"))
      (node (ref "VD10") (pin "2") (pinfunction "2_2") (pintype "passive"))
      (node (ref "VD11") (pin "2") (pinfunction "2_2") (pintype "passive"))
      (node (ref "VD12") (pin "2") (pinfunction "2_2") (pintype "passive"))
      (node (ref "VD13") (pin "2") (pinfunction "2_2") (pintype "passive"))
      (node (ref "VD14") (pin "2") (pinfunction "2_2") (pintype "passive"))
      (node (ref "VD15") (pin "2") (pinfunction "2_2") (pintype "passive"))
      (node (ref "VD16") (pin "2") (pinfunction "2_2") (pintype "passive"))
      (node (ref "VD17") (pin "2") (pinfunction "2_2") (pintype "passive"))
      (node (ref "VD2") (pin "2") (pinfunction "2_2") (pintype "passive"))
      (node (ref "VD3") (pin "2") (pinfunction "2_2") (pintype "passive"))
      (node (ref "VD4") (pin "2") (pinfunction "2_2") (pintype "passive"))
      (node (ref "VD5") (pin "2") (pinfunction "2_2") (pintype "passive"))
      (node (ref "VD6") (pin "2") (pinfunction "2_2") (pintype "passive"))
      (node (ref "VD8") (pin "2") (pinfunction "2_2") (pintype "passive"))
      (node (ref "VD9") (pin "2") (pinfunction "2_2") (pintype "passive"))
    )
    (net (code "52") (name "GND") (class "Default")
      (node (ref "C10") (pin "2") (pinfunction "2_2") (pintype "passive"))
      (node (ref "C100") (pin "2") (pinfunction "2_2") (pintype "passive"))
      (node (ref "C101") (pin "2") (pinfunction "2_2") (pintype "passive"))
      (node (ref "C102") (pin "1") (pinfunction "1_1") (pintype "passive"))
      (node (ref "C103") (pin "1") (pinfunction "1_1") (pintype "passive"))
      (node (ref "C104") (pin "1") (pinfunction "1_1") (pintype "passive"))
      (node (ref "C105") (pin "2") (pinfunction "2_2") (pintype "passive"))
      (node (ref "C106") (pin "2") (pinfunction "2_2") (pintype "passive"))
      (node (ref "C107") (pin "2") (pinfunction "2_2") (pintype "passive"))
      (node (ref "C108") (pin "2") (pinfunction "2_2") (pintype "passive"))
      (node (ref "C11") (pin "1") (pinfunction "1_1") (pintype "passive"))
      (node (ref "C113") (pin "2") (pinfunction "2_2") (pintype "passive"))
      (node (ref "C114") (pin "2") (pinfunction "2_2") (pintype "passive"))
      (node (ref "C115") (pin "1") (pinfunction "1_1") (pintype "passive"))
      (node (ref "C116") (pin "1") (pinfunction "1_1") (pintype "passive"))
      (node (ref "C117") (pin "2") (pinfunction "2_2") (pintype "passive"))
      (node (ref "C118") (pin "2") (pinfunction "2_2") (pintype "passive"))
      (node (ref "C12") (pin "2") (pinfunction "2_2") (pintype "passive"))
      (node (ref "C13") (pin "2") (pinfunction "2_2") (pintype "passive"))
      (node (ref "C14") (pin "1") (pinfunction "1_1") (pintype "passive"))
      (node (ref "C19") (pin "2") (pinfunction "2_2") (pintype "passive"))
      (node (ref "C20") (pin "2") (pinfunction "2_2") (pintype "passive"))
      (node (ref "C21") (pin "1") (pinfunction "1_1") (pintype "passive"))
      (node (ref "C22") (pin "1") (pinfunction "1_1") (pintype "passive"))
      (node (ref "C23") (pin "2") (pinfunction "2_2") (pintype "passive"))
      (node (ref "C24") (pin "2") (pinfunction "2_2") (pintype "passive"))
      (node (ref "C29") (pin "2") (pinfunction "2_2") (pintype "passive"))
      (node (ref "C30") (pin "2") (pinfunction "2_2") (pintype "passive"))
      (node (ref "C31") (pin "1") (pinfunction "1_1") (pintype "passive"))
      (node (ref "C32") (pin "1") (pinfunction "1_1") (pintype "passive"))
      (node (ref "C33") (pin "2") (pinfunction "2_2") (pintype "passive"))
      (node (ref "C34") (pin "2") (pinfunction "2_2") (pintype "passive"))
      (node (ref "C35") (pin "2") (pinfunction "2_2") (pintype "passive"))
      (node (ref "C36") (pin "2") (pinfunction "2_2") (pintype "passive"))
      (node (ref "C37") (pin "2") (pinfunction "2_2") (pintype "passive"))
      (node (ref "C43") (pin "2") (pinfunction "2_2") (pintype "passive"))
      (node (ref "C44") (pin "2") (pinfunction "2_2") (pintype "passive"))
      (node (ref "C45") (pin "1") (pinfunction "1_1") (pintype "passive"))
      (node (ref "C46") (pin "1") (pinfunction "1_1") (pintype "passive"))
      (node (ref "C47") (pin "2") (pinfunction "2_2") (pintype "passive"))
      (node (ref "C48") (pin "2") (pinfunction "2_2") (pintype "passive"))
      (node (ref "C49") (pin "2") (pinfunction "2_2") (pintype "passive"))
      (node (ref "C5") (pin "2") (pinfunction "2_2") (pintype "passive"))
      (node (ref "C50") (pin "2") (pinfunction "2_2") (pintype "passive"))
      (node (ref "C51") (pin "2") (pinfunction "2_2") (pintype "passive"))
      (node (ref "C52") (pin "1") (pinfunction "1_1") (pintype "passive"))
      (node (ref "C53") (pin "1") (pinfunction "1_1") (pintype "passive"))
      (node (ref "C54") (pin "1") (pinfunction "1_1") (pintype "passive"))
      (node (ref "C55") (pin "1") (pinfunction "1_1") (pintype "passive"))
      (node (ref "C56") (pin "1") (pinfunction "1_1") (pintype "passive"))
      (node (ref "C6") (pin "2") (pinfunction "2_2") (pintype "passive"))
      (node (ref "C61") (pin "2") (pinfunction "2_2") (pintype "passive"))
      (node (ref "C62") (pin "2") (pinfunction "2_2") (pintype "passive"))
      (node (ref "C63") (pin "1") (pinfunction "1_1") (pintype "passive"))
      (node (ref "C64") (pin "1") (pinfunction "1_1") (pintype "passive"))
      (node (ref "C65") (pin "2") (pinfunction "2_2") (pintype "passive"))
      (node (ref "C66") (pin "2") (pinfunction "2_2") (pintype "passive"))
      (node (ref "C68") (pin "2") (pinfunction "2_2") (pintype "passive"))
      (node (ref "C69") (pin "2") (pinfunction "2_2") (pintype "passive"))
      (node (ref "C7") (pin "1") (pinfunction "1_1") (pintype "passive"))
      (node (ref "C70") (pin "2") (pinfunction "2_2") (pintype "passive"))
      (node (ref "C71") (pin "1") (pinfunction "1_1") (pintype "passive"))
      (node (ref "C72") (pin "1") (pinfunction "1_1") (pintype "passive"))
      (node (ref "C73") (pin "1") (pinfunction "1_1") (pintype "passive"))
      (node (ref "C74") (pin "2") (pinfunction "2_2") (pintype "passive"))
      (node (ref "C75") (pin "2") (pinfunction "2_2") (pintype "passive"))
      (node (ref "C76") (pin "1") (pinfunction "1_1") (pintype "passive"))
      (node (ref "C8") (pin "1") (pinfunction "1_1") (pintype "passive"))
      (node (ref "C81") (pin "1") (pinfunction "1_1") (pintype "passive"))
      (node (ref "C82") (pin "2") (pinfunction "2_2") (pintype "passive"))
      (node (ref "C83") (pin "2") (pinfunction "2_2") (pintype "passive"))
      (node (ref "C84") (pin "1") (pinfunction "1_1") (pintype "passive"))
      (node (ref "C85") (pin "1") (pinfunction "1_1") (pintype "passive"))
      (node (ref "C86") (pin "2") (pinfunction "2_2") (pintype "passive"))
      (node (ref "C87") (pin "2") (pinfunction "2_2") (pintype "passive"))
      (node (ref "C89") (pin "2") (pinfunction "2_2") (pintype "passive"))
      (node (ref "C9") (pin "2") (pinfunction "2_2") (pintype "passive"))
      (node (ref "C90") (pin "2") (pinfunction "2_2") (pintype "passive"))
      (node (ref "C91") (pin "2") (pinfunction "2_2") (pintype "passive"))
      (node (ref "C92") (pin "1") (pinfunction "1_1") (pintype "passive"))
      (node (ref "C93") (pin "1") (pinfunction "1_1") (pintype "passive"))
      (node (ref "C94") (pin "1") (pinfunction "1_1") (pintype "passive"))
      (node (ref "C95") (pin "1") (pinfunction "1_1") (pintype "passive"))
      (node (ref "D1") (pin "A") (pinfunction "2_A") (pintype "passive"))
      (node (ref "D2") (pin "A") (pinfunction "2_A") (pintype "passive"))
      (node (ref "D3") (pin "A") (pinfunction "2_A") (pintype "passive"))
      (node (ref "J1") (pin "29") (pinfunction "GND1_29") (pintype "bidirectional"))
      (node (ref "R23") (pin "2") (pinfunction "2_2") (pintype "passive"))
      (node (ref "R25") (pin "2") (pinfunction "2_2") (pintype "passive"))
      (node (ref "R31") (pin "2") (pinfunction "2_2") (pintype "passive"))
      (node (ref "R35") (pin "2") (pinfunction "2_2") (pintype "passive"))
      (node (ref "R41") (pin "2") (pinfunction "2_2") (pintype "passive"))
      (node (ref "R43") (pin "2") (pinfunction "2_2") (pintype "passive"))
      (node (ref "R57") (pin "2") (pinfunction "2_2") (pintype "passive"))
      (node (ref "TB1") (pin "P1_1") (pinfunction "GND_P1_1") (pintype "power_in"))
      (node (ref "TB1") (pin "P1_2") (pinfunction "GND_P1_2") (pintype "power_in"))
      (node (ref "TB1") (pin "P1_23") (pinfunction "GND_P1_23") (pintype "power_in"))
      (node (ref "TB1") (pin "P1_49") (pinfunction "GND_P1_49") (pintype "power_in"))
      (node (ref "TB1") (pin "P1_5") (pinfunction "GND_P1_5") (pintype "power_in"))
      (node (ref "TB1") (pin "P1_50") (pinfunction "GND_P1_50") (pintype "power_in"))
      (node (ref "TB1") (pin "P2_1") (pinfunction "GND_P2_1") (pintype "power_in"))
      (node (ref "TB1") (pin "P2_2") (pinfunction "GND_P2_2") (pintype "power_in"))
      (node (ref "TB1") (pin "P2_49") (pinfunction "GND_P2_49") (pintype "power_in"))
      (node (ref "TB1") (pin "P2_50") (pinfunction "GND_P2_50") (pintype "power_in"))
      (node (ref "U1") (pin "4") (pinfunction "COM_4") (pintype "passive"))
      (node (ref "U10") (pin "2") (pinfunction "GND_2") (pintype "power_in"))
      (node (ref "U11") (pin "2") (pinfunction "GND_2") (pintype "power_in"))
      (node (ref "U12") (pin "4") (pinfunction "COM_4") (pintype "passive"))
      (node (ref "U13") (pin "4") (pinfunction "COM_4") (pintype "passive"))
      (node (ref "U14") (pin "11") (pinfunction "THERMALPAD_11") (pintype "bidirectional"))
      (node (ref "U14") (pin "12") (pinfunction "THERMALPAD_12") (pintype "bidirectional"))
      (node (ref "U14") (pin "13") (pinfunction "THERMALPAD_13") (pintype "bidirectional"))
      (node (ref "U14") (pin "14") (pinfunction "THERMALPAD_14") (pintype "bidirectional"))
      (node (ref "U14") (pin "15") (pinfunction "THERMALPAD_15") (pintype "bidirectional"))
      (node (ref "U14") (pin "16") (pinfunction "THERMALPAD_16") (pintype "bidirectional"))
      (node (ref "U14") (pin "9") (pinfunction "GND_9") (pintype "power_in"))
      (node (ref "U15") (pin "4") (pinfunction "COM_4") (pintype "passive"))
      (node (ref "U16") (pin "4") (pinfunction "COM_4") (pintype "passive"))
      (node (ref "U17") (pin "11") (pinfunction "THERMALPAD_11") (pintype "bidirectional"))
      (node (ref "U17") (pin "12") (pinfunction "THERMALPAD_12") (pintype "bidirectional"))
      (node (ref "U17") (pin "13") (pinfunction "THERMALPAD_13") (pintype "bidirectional"))
      (node (ref "U17") (pin "14") (pinfunction "THERMALPAD_14") (pintype "bidirectional"))
      (node (ref "U17") (pin "15") (pinfunction "THERMALPAD_15") (pintype "bidirectional"))
      (node (ref "U17") (pin "16") (pinfunction "THERMALPAD_16") (pintype "bidirectional"))
      (node (ref "U17") (pin "9") (pinfunction "GND_9") (pintype "power_in"))
      (node (ref "U18") (pin "2") (pinfunction "GND_2") (pintype "power_in"))
      (node (ref "U19") (pin "2") (pinfunction "GND_2") (pintype "power_in"))
      (node (ref "U2") (pin "4") (pinfunction "COM_4") (pintype "passive"))
      (node (ref "U20") (pin "4") (pinfunction "COM_4") (pintype "passive"))
      (node (ref "U21") (pin "4") (pinfunction "COM_4") (pintype "passive"))
      (node (ref "U22") (pin "11") (pinfunction "THERMALPAD_11") (pintype "bidirectional"))
      (node (ref "U22") (pin "12") (pinfunction "THERMALPAD_12") (pintype "bidirectional"))
      (node (ref "U22") (pin "13") (pinfunction "THERMALPAD_13") (pintype "bidirectional"))
      (node (ref "U22") (pin "14") (pinfunction "THERMALPAD_14") (pintype "bidirectional"))
      (node (ref "U22") (pin "15") (pinfunction "THERMALPAD_15") (pintype "bidirectional"))
      (node (ref "U22") (pin "16") (pinfunction "THERMALPAD_16") (pintype "bidirectional"))
      (node (ref "U22") (pin "9") (pinfunction "GND_9") (pintype "power_in"))
      (node (ref "U23") (pin "4") (pinfunction "COM_4") (pintype "passive"))
      (node (ref "U24") (pin "4") (pinfunction "COM_4") (pintype "passive"))
      (node (ref "U25") (pin "2") (pinfunction "GND_2") (pintype "power_in"))
      (node (ref "U26") (pin "2") (pinfunction "GND_2") (pintype "power_in"))
      (node (ref "U27") (pin "4") (pinfunction "COM_4") (pintype "passive"))
      (node (ref "U28") (pin "4") (pinfunction "COM_4") (pintype "passive"))
      (node (ref "U3") (pin "2") (pinfunction "VSS_2") (pintype "power_in"))
      (node (ref "U4") (pin "2") (pinfunction "GND_2") (pintype "power_in"))
      (node (ref "U5") (pin "2") (pinfunction "GND_2") (pintype "power_in"))
      (node (ref "U6") (pin "4") (pinfunction "COM_4") (pintype "passive"))
      (node (ref "U7") (pin "4") (pinfunction "COM_4") (pintype "passive"))
      (node (ref "U8") (pin "4") (pinfunction "COM_4") (pintype "passive"))
      (node (ref "U9") (pin "4") (pinfunction "COM_4") (pintype "passive"))
      (node (ref "VT11") (pin "3") (pinfunction "3_3") (pintype "passive"))
      (node (ref "VT12") (pin "3") (pinfunction "3_3") (pintype "passive"))
      (node (ref "VT15") (pin "3") (pinfunction "3_3") (pintype "passive"))
      (node (ref "VT16") (pin "3") (pinfunction "3_3") (pintype "passive"))
      (node (ref "VT19") (pin "3") (pinfunction "3_3") (pintype "passive"))
      (node (ref "VT20") (pin "3") (pinfunction "3_3") (pintype "passive"))
      (node (ref "VT23") (pin "3") (pinfunction "3_3") (pintype "passive"))
      (node (ref "VT24") (pin "3") (pinfunction "3_3") (pintype "passive"))
      (node (ref "VT27") (pin "3") (pinfunction "3_3") (pintype "passive"))
      (node (ref "VT28") (pin "3") (pinfunction "3_3") (pintype "passive"))
      (node (ref "VT3") (pin "3") (pinfunction "3_3") (pintype "passive"))
      (node (ref "VT31") (pin "3") (pinfunction "3_3") (pintype "passive"))
      (node (ref "VT32") (pin "3") (pinfunction "3_3") (pintype "passive"))
      (node (ref "VT33") (pin "2") (pinfunction "3_2") (pintype "passive"))
      (node (ref "VT4") (pin "3") (pinfunction "3_3") (pintype "passive"))
      (node (ref "VT7") (pin "3") (pinfunction "3_3") (pintype "passive"))
      (node (ref "VT8") (pin "3") (pinfunction "3_3") (pintype "passive"))
      (node (ref "X3") (pin "4") (pinfunction "4_4") (pintype "passive"))
      (node (ref "X4") (pin "4") (pinfunction "4_4") (pintype "passive"))
      (node (ref "X5") (pin "2") (pinfunction "Bat__-_2") (pintype "power_in"))
    )
    (net (code "53") (name "Net-(C56-Pad2)") (class "Default")
      (node (ref "C56") (pin "2") (pinfunction "2_2") (pintype "passive"))
      (node (ref "R24") (pin "2") (pinfunction "2_2") (pintype "passive"))
    )
    (net (code "54") (name "Net-(C81-Pad2)") (class "Default")
      (node (ref "C81") (pin "2") (pinfunction "2_2") (pintype "passive"))
      (node (ref "R34") (pin "2") (pinfunction "2_2") (pintype "passive"))
    )
    (net (code "55") (name "Net-(C102-Pad2)") (class "Default")
      (node (ref "C102") (pin "2") (pinfunction "2_2") (pintype "passive"))
      (node (ref "R42") (pin "2") (pinfunction "2_2") (pintype "passive"))
    )
    (net (code "56") (name "Net-(D1-1)") (class "Default")
      (node (ref "C42") (pin "1") (pinfunction "1_1") (pintype "passive"))
      (node (ref "D1") (pin "C") (pinfunction "1_C") (pintype "passive"))
      (node (ref "L1") (pin "2") (pinfunction "2_2") (pintype "passive"))
      (node (ref "U14") (pin "10") (pinfunction "PH_10") (pintype "output"))
    )
    (net (code "57") (name "Net-(D2-1)") (class "Default")
      (node (ref "C67") (pin "1") (pinfunction "1_1") (pintype "passive"))
      (node (ref "D2") (pin "C") (pinfunction "1_C") (pintype "passive"))
      (node (ref "L2") (pin "2") (pinfunction "2_2") (pintype "passive"))
      (node (ref "U17") (pin "10") (pinfunction "PH_10") (pintype "output"))
    )
    (net (code "58") (name "Net-(D3-1)") (class "Default")
      (node (ref "C88") (pin "1") (pinfunction "1_1") (pintype "passive"))
      (node (ref "D3") (pin "C") (pinfunction "1_C") (pintype "passive"))
      (node (ref "L3") (pin "2") (pinfunction "2_2") (pintype "passive"))
      (node (ref "U22") (pin "10") (pinfunction "PH_10") (pintype "output"))
    )
    (net (code "59") (name "Net-(R1-Pad1)") (class "Default")
      (node (ref "R1") (pin "1") (pinfunction "1_1") (pintype "passive"))
      (node (ref "VT1") (pin "1") (pinfunction "1_1") (pintype "passive"))
    )
    (net (code "60") (name "Net-(R2-Pad1)") (class "Default")
      (node (ref "R2") (pin "1") (pinfunction "1_1") (pintype "passive"))
      (node (ref "VT2") (pin "1") (pinfunction "1_1") (pintype "passive"))
    )
    (net (code "61") (name "Net-(R3-Pad1)") (class "Default")
      (node (ref "R3") (pin "1") (pinfunction "1_1") (pintype "passive"))
      (node (ref "VT3") (pin "1") (pinfunction "1_1") (pintype "passive"))
    )
    (net (code "62") (name "Net-(R4-Pad1)") (class "Default")
      (node (ref "R4") (pin "1") (pinfunction "1_1") (pintype "passive"))
      (node (ref "VT4") (pin "1") (pinfunction "1_1") (pintype "passive"))
    )
    (net (code "63") (name "Net-(R8-Pad1)") (class "Default")
      (node (ref "R8") (pin "1") (pinfunction "1_1") (pintype "passive"))
      (node (ref "VT5") (pin "1") (pinfunction "1_1") (pintype "passive"))
    )
    (net (code "64") (name "Net-(R9-Pad1)") (class "Default")
      (node (ref "R9") (pin "1") (pinfunction "1_1") (pintype "passive"))
      (node (ref "VT6") (pin "1") (pinfunction "1_1") (pintype "passive"))
    )
    (net (code "65") (name "Net-(R10-Pad1)") (class "Default")
      (node (ref "R10") (pin "1") (pinfunction "1_1") (pintype "passive"))
      (node (ref "VT7") (pin "1") (pinfunction "1_1") (pintype "passive"))
    )
    (net (code "66") (name "Net-(R11-Pad1)") (class "Default")
      (node (ref "R11") (pin "1") (pinfunction "1_1") (pintype "passive"))
      (node (ref "VT8") (pin "1") (pinfunction "1_1") (pintype "passive"))
    )
    (net (code "67") (name "Net-(R12-Pad1)") (class "Default")
      (node (ref "R12") (pin "1") (pinfunction "1_1") (pintype "passive"))
      (node (ref "VT9") (pin "1") (pinfunction "1_1") (pintype "passive"))
    )
    (net (code "68") (name "Net-(R13-Pad1)") (class "Default")
      (node (ref "R13") (pin "1") (pinfunction "1_1") (pintype "passive"))
      (node (ref "VT10") (pin "1") (pinfunction "1_1") (pintype "passive"))
    )
    (net (code "69") (name "Net-(R14-Pad1)") (class "Default")
      (node (ref "R14") (pin "1") (pinfunction "1_1") (pintype "passive"))
      (node (ref "VT11") (pin "1") (pinfunction "1_1") (pintype "passive"))
    )
    (net (code "70") (name "Net-(R15-Pad1)") (class "Default")
      (node (ref "R15") (pin "1") (pinfunction "1_1") (pintype "passive"))
      (node (ref "VT12") (pin "1") (pinfunction "1_1") (pintype "passive"))
    )
    (net (code "71") (name "Net-(R18-Pad1)") (class "Default")
      (node (ref "R18") (pin "1") (pinfunction "1_1") (pintype "passive"))
      (node (ref "VT13") (pin "1") (pinfunction "1_1") (pintype "passive"))
    )
    (net (code "72") (name "Net-(R19-Pad1)") (class "Default")
      (node (ref "R19") (pin "1") (pinfunction "1_1") (pintype "passive"))
      (node (ref "VT14") (pin "1") (pinfunction "1_1") (pintype "passive"))
    )
    (net (code "73") (name "Net-(R21-Pad1)") (class "Default")
      (node (ref "R21") (pin "1") (pinfunction "1_1") (pintype "passive"))
      (node (ref "VT15") (pin "1") (pinfunction "1_1") (pintype "passive"))
    )
    (net (code "74") (name "Net-(R22-Pad1)") (class "Default")
      (node (ref "R22") (pin "1") (pinfunction "1_1") (pintype "passive"))
      (node (ref "VT16") (pin "1") (pinfunction "1_1") (pintype "passive"))
    )
    (net (code "75") (name "Net-(R26-Pad1)") (class "Default")
      (node (ref "R26") (pin "1") (pinfunction "1_1") (pintype "passive"))
      (node (ref "VT17") (pin "1") (pinfunction "1_1") (pintype "passive"))
    )
    (net (code "76") (name "Net-(R27-Pad1)") (class "Default")
      (node (ref "R27") (pin "1") (pinfunction "1_1") (pintype "passive"))
      (node (ref "VT18") (pin "1") (pinfunction "1_1") (pintype "passive"))
    )
    (net (code "77") (name "Net-(R29-Pad1)") (class "Default")
      (node (ref "R29") (pin "1") (pinfunction "1_1") (pintype "passive"))
      (node (ref "VT19") (pin "1") (pinfunction "1_1") (pintype "passive"))
    )
    (net (code "78") (name "Net-(R30-Pad1)") (class "Default")
      (node (ref "R30") (pin "1") (pinfunction "1_1") (pintype "passive"))
      (node (ref "VT20") (pin "1") (pinfunction "1_1") (pintype "passive"))
    )
    (net (code "79") (name "Net-(R36-Pad1)") (class "Default")
      (node (ref "R36") (pin "1") (pinfunction "1_1") (pintype "passive"))
      (node (ref "VT21") (pin "1") (pinfunction "1_1") (pintype "passive"))
    )
    (net (code "80") (name "Net-(R37-Pad1)") (class "Default")
      (node (ref "R37") (pin "1") (pinfunction "1_1") (pintype "passive"))
      (node (ref "VT22") (pin "1") (pinfunction "1_1") (pintype "passive"))
    )
    (net (code "81") (name "Net-(R38-Pad1)") (class "Default")
      (node (ref "R38") (pin "1") (pinfunction "1_1") (pintype "passive"))
      (node (ref "VT23") (pin "1") (pinfunction "1_1") (pintype "passive"))
    )
    (net (code "82") (name "Net-(R39-Pad1)") (class "Default")
      (node (ref "R39") (pin "1") (pinfunction "1_1") (pintype "passive"))
      (node (ref "VT24") (pin "1") (pinfunction "1_1") (pintype "passive"))
    )
    (net (code "83") (name "Net-(R44-Pad1)") (class "Default")
      (node (ref "R44") (pin "1") (pinfunction "1_1") (pintype "passive"))
      (node (ref "VT25") (pin "1") (pinfunction "1_1") (pintype "passive"))
    )
    (net (code "84") (name "Net-(R45-Pad1)") (class "Default")
      (node (ref "R45") (pin "1") (pinfunction "1_1") (pintype "passive"))
      (node (ref "VT26") (pin "1") (pinfunction "1_1") (pintype "passive"))
    )
    (net (code "85") (name "Net-(R46-Pad1)") (class "Default")
      (node (ref "R46") (pin "1") (pinfunction "1_1") (pintype "passive"))
      (node (ref "VT27") (pin "1") (pinfunction "1_1") (pintype "passive"))
    )
    (net (code "86") (name "Net-(R47-Pad1)") (class "Default")
      (node (ref "R47") (pin "1") (pinfunction "1_1") (pintype "passive"))
      (node (ref "VT28") (pin "1") (pinfunction "1_1") (pintype "passive"))
    )
    (net (code "87") (name "Net-(R50-Pad1)") (class "Default")
      (node (ref "R50") (pin "1") (pinfunction "1_1") (pintype "passive"))
      (node (ref "VT29") (pin "1") (pinfunction "1_1") (pintype "passive"))
    )
    (net (code "88") (name "Net-(R51-Pad1)") (class "Default")
      (node (ref "R51") (pin "1") (pinfunction "1_1") (pintype "passive"))
      (node (ref "VT30") (pin "1") (pinfunction "1_1") (pintype "passive"))
    )
    (net (code "89") (name "Net-(R52-Pad1)") (class "Default")
      (node (ref "R52") (pin "1") (pinfunction "1_1") (pintype "passive"))
      (node (ref "VT31") (pin "1") (pinfunction "1_1") (pintype "passive"))
    )
    (net (code "90") (name "Net-(R53-Pad1)") (class "Default")
      (node (ref "R53") (pin "1") (pinfunction "1_1") (pintype "passive"))
      (node (ref "VT32") (pin "1") (pinfunction "1_1") (pintype "passive"))
    )
    (net (code "91") (name "Net-(R56-Pad1)") (class "Default")
      (node (ref "R56") (pin "1") (pinfunction "1_1") (pintype "passive"))
      (node (ref "R57") (pin "1") (pinfunction "1_1") (pintype "passive"))
      (node (ref "VT33") (pin "1") (pinfunction "1_1") (pintype "passive"))
    )
    (net (code "92") (name "Net-(TB1-PA0-WKUP)") (class "Default")
      (node (ref "R54") (pin "2") (pinfunction "2_2") (pintype "passive"))
      (node (ref "TB1") (pin "P1_12") (pinfunction "PA0-WKUP_P1_12") (pintype "bidirectional"))
    )
    (net (code "93") (name "Net-(TB1-PB14)") (class "Default")
      (node (ref "R55") (pin "2") (pinfunction "2_2") (pintype "passive"))
      (node (ref "TB1") (pin "P1_38") (pinfunction "PB14_P1_38") (pintype "bidirectional"))
    )
    (net (code "94") (name "Net-(TB1-PD15)") (class "Default")
      (node (ref "R56") (pin "2") (pinfunction "2_2") (pintype "passive"))
      (node (ref "TB1") (pin "P1_47") (pinfunction "PD15_P1_47") (pintype "bidirectional"))
    )
    (net (code "95") (name "Net-(U1-HO)") (class "Default")
      (node (ref "R1") (pin "2") (pinfunction "2_2") (pintype "passive"))
      (node (ref "U1") (pin "7") (pinfunction "HO_7") (pintype "output"))
    )
    (net (code "96") (name "Net-(U1-LO)") (class "Default")
      (node (ref "R3") (pin "2") (pinfunction "2_2") (pintype "passive"))
      (node (ref "U1") (pin "5") (pinfunction "LO_5") (pintype "output"))
    )
    (net (code "97") (name "Net-(U1-Vb)") (class "Default")
      (node (ref "C1") (pin "1") (pinfunction "1_1") (pintype "passive"))
      (node (ref "C3") (pin "2") (pinfunction "2_2") (pintype "passive"))
      (node (ref "CR1") (pin "1") (pinfunction "1_1") (pintype "passive"))
      (node (ref "U1") (pin "8") (pinfunction "Vb_8") (pintype "power_in"))
      (node (ref "VD1") (pin "1") (pinfunction "1_1") (pintype "passive"))
    )
    (net (code "98") (name "Net-(U1-Vs)") (class "Default")
      (node (ref "C1") (pin "2") (pinfunction "2_2") (pintype "passive"))
      (node (ref "C3") (pin "1") (pinfunction "1_1") (pintype "passive"))
      (node (ref "CR1") (pin "2") (pinfunction "2_2") (pintype "passive"))
      (node (ref "U1") (pin "6") (pinfunction "Vs_6") (pintype "power_in"))
      (node (ref "U4") (pin "4") (pinfunction "IP-_4") (pintype "passive"))
      (node (ref "VT1") (pin "3") (pinfunction "3_3") (pintype "passive"))
      (node (ref "VT3") (pin "2") (pinfunction "2_2") (pintype "passive"))
    )
    (net (code "99") (name "Net-(U2-HO)") (class "Default")
      (node (ref "R2") (pin "2") (pinfunction "2_2") (pintype "passive"))
      (node (ref "U2") (pin "7") (pinfunction "HO_7") (pintype "output"))
    )
    (net (code "100") (name "Net-(U2-LO)") (class "Default")
      (node (ref "R4") (pin "2") (pinfunction "2_2") (pintype "passive"))
      (node (ref "U2") (pin "5") (pinfunction "LO_5") (pintype "output"))
    )
    (net (code "101") (name "Net-(U2-Vb)") (class "Default")
      (node (ref "C2") (pin "1") (pinfunction "1_1") (pintype "passive"))
      (node (ref "C4") (pin "2") (pinfunction "2_2") (pintype "passive"))
      (node (ref "CR2") (pin "1") (pinfunction "1_1") (pintype "passive"))
      (node (ref "U2") (pin "8") (pinfunction "Vb_8") (pintype "power_in"))
      (node (ref "VD2") (pin "1") (pinfunction "1_1") (pintype "passive"))
    )
    (net (code "102") (name "Net-(U2-Vs)") (class "Default")
      (node (ref "C2") (pin "2") (pinfunction "2_2") (pintype "passive"))
      (node (ref "C4") (pin "1") (pinfunction "1_1") (pintype "passive"))
      (node (ref "CR2") (pin "2") (pinfunction "2_2") (pintype "passive"))
      (node (ref "U2") (pin "6") (pinfunction "Vs_6") (pintype "power_in"))
      (node (ref "U5") (pin "4") (pinfunction "IP-_4") (pintype "passive"))
      (node (ref "VT2") (pin "3") (pinfunction "3_3") (pintype "passive"))
      (node (ref "VT4") (pin "2") (pinfunction "2_2") (pintype "passive"))
    )
    (net (code "103") (name "Net-(U4-IP+)") (class "Default")
      (node (ref "U4") (pin "5") (pinfunction "IP+_5") (pintype "passive"))
      (node (ref "X1") (pin "1") (pinfunction "1_1") (pintype "passive"))
    )
    (net (code "104") (name "Net-(U4-VIOUT)") (class "Default")
      (node (ref "R6") (pin "1") (pinfunction "1_1") (pintype "passive"))
      (node (ref "U4") (pin "3") (pinfunction "VIOUT_3") (pintype "output"))
    )
    (net (code "105") (name "Net-(U5-IP+)") (class "Default")
      (node (ref "U5") (pin "5") (pinfunction "IP+_5") (pintype "passive"))
      (node (ref "X2") (pin "1") (pinfunction "1_1") (pintype "passive"))
    )
    (net (code "106") (name "Net-(U5-VIOUT)") (class "Default")
      (node (ref "R7") (pin "1") (pinfunction "1_1") (pintype "passive"))
      (node (ref "U5") (pin "3") (pinfunction "VIOUT_3") (pintype "output"))
    )
    (net (code "107") (name "Net-(U6-HO)") (class "Default")
      (node (ref "R8") (pin "2") (pinfunction "2_2") (pintype "passive"))
      (node (ref "U6") (pin "7") (pinfunction "HO_7") (pintype "output"))
    )
    (net (code "108") (name "Net-(U6-LO)") (class "Default")
      (node (ref "R10") (pin "2") (pinfunction "2_2") (pintype "passive"))
      (node (ref "U6") (pin "5") (pinfunction "LO_5") (pintype "output"))
    )
    (net (code "109") (name "Net-(U6-Vb)") (class "Default")
      (node (ref "C15") (pin "1") (pinfunction "1_1") (pintype "passive"))
      (node (ref "C17") (pin "2") (pinfunction "2_2") (pintype "passive"))
      (node (ref "CR4") (pin "1") (pinfunction "1_1") (pintype "passive"))
      (node (ref "U6") (pin "8") (pinfunction "Vb_8") (pintype "power_in"))
      (node (ref "VD3") (pin "1") (pinfunction "1_1") (pintype "passive"))
    )
    (net (code "110") (name "Net-(U6-Vs)") (class "Default")
      (node (ref "C15") (pin "2") (pinfunction "2_2") (pintype "passive"))
      (node (ref "C17") (pin "1") (pinfunction "1_1") (pintype "passive"))
      (node (ref "CR4") (pin "2") (pinfunction "2_2") (pintype "passive"))
      (node (ref "U6") (pin "6") (pinfunction "Vs_6") (pintype "power_in"))
      (node (ref "VT5") (pin "3") (pinfunction "3_3") (pintype "passive"))
      (node (ref "VT7") (pin "2") (pinfunction "2_2") (pintype "passive"))
      (node (ref "X1") (pin "2") (pinfunction "2_2") (pintype "passive"))
    )
    (net (code "111") (name "Net-(U7-HO)") (class "Default")
      (node (ref "R9") (pin "2") (pinfunction "2_2") (pintype "passive"))
      (node (ref "U7") (pin "7") (pinfunction "HO_7") (pintype "output"))
    )
    (net (code "112") (name "Net-(U7-LO)") (class "Default")
      (node (ref "R11") (pin "2") (pinfunction "2_2") (pintype "passive"))
      (node (ref "U7") (pin "5") (pinfunction "LO_5") (pintype "output"))
    )
    (net (code "113") (name "Net-(U7-Vb)") (class "Default")
      (node (ref "C16") (pin "1") (pinfunction "1_1") (pintype "passive"))
      (node (ref "C18") (pin "2") (pinfunction "2_2") (pintype "passive"))
      (node (ref "CR5") (pin "1") (pinfunction "1_1") (pintype "passive"))
      (node (ref "U7") (pin "8") (pinfunction "Vb_8") (pintype "power_in"))
      (node (ref "VD4") (pin "1") (pinfunction "1_1") (pintype "passive"))
    )
    (net (code "114") (name "Net-(U7-Vs)") (class "Default")
      (node (ref "C16") (pin "2") (pinfunction "2_2") (pintype "passive"))
      (node (ref "C18") (pin "1") (pinfunction "1_1") (pintype "passive"))
      (node (ref "CR5") (pin "2") (pinfunction "2_2") (pintype "passive"))
      (node (ref "U7") (pin "6") (pinfunction "Vs_6") (pintype "power_in"))
      (node (ref "VT6") (pin "3") (pinfunction "3_3") (pintype "passive"))
      (node (ref "VT8") (pin "2") (pinfunction "2_2") (pintype "passive"))
      (node (ref "X2") (pin "2") (pinfunction "2_2") (pintype "passive"))
    )
    (net (code "115") (name "Net-(U8-HO)") (class "Default")
      (node (ref "R12") (pin "2") (pinfunction "2_2") (pintype "passive"))
      (node (ref "U8") (pin "7") (pinfunction "HO_7") (pintype "output"))
    )
    (net (code "116") (name "Net-(U8-LO)") (class "Default")
      (node (ref "R14") (pin "2") (pinfunction "2_2") (pintype "passive"))
      (node (ref "U8") (pin "5") (pinfunction "LO_5") (pintype "output"))
    )
    (net (code "117") (name "Net-(U8-Vb)") (class "Default")
      (node (ref "C25") (pin "1") (pinfunction "1_1") (pintype "passive"))
      (node (ref "C27") (pin "2") (pinfunction "2_2") (pintype "passive"))
      (node (ref "CR6") (pin "1") (pinfunction "1_1") (pintype "passive"))
      (node (ref "U8") (pin "8") (pinfunction "Vb_8") (pintype "power_in"))
      (node (ref "VD5") (pin "1") (pinfunction "1_1") (pintype "passive"))
    )
    (net (code "118") (name "Net-(U9-HO)") (class "Default")
      (node (ref "R13") (pin "2") (pinfunction "2_2") (pintype "passive"))
      (node (ref "U9") (pin "7") (pinfunction "HO_7") (pintype "output"))
    )
    (net (code "119") (name "Net-(U9-LO)") (class "Default")
      (node (ref "R15") (pin "2") (pinfunction "2_2") (pintype "passive"))
      (node (ref "U9") (pin "5") (pinfunction "LO_5") (pintype "output"))
    )
    (net (code "120") (name "Net-(U9-Vb)") (class "Default")
      (node (ref "C26") (pin "1") (pinfunction "1_1") (pintype "passive"))
      (node (ref "C28") (pin "2") (pinfunction "2_2") (pintype "passive"))
      (node (ref "CR7") (pin "1") (pinfunction "1_1") (pintype "passive"))
      (node (ref "U9") (pin "8") (pinfunction "Vb_8") (pintype "power_in"))
      (node (ref "VD6") (pin "1") (pinfunction "1_1") (pintype "passive"))
    )
    (net (code "121") (name "Net-(U10-IP+)") (class "Default")
      (node (ref "U10") (pin "5") (pinfunction "IP+_5") (pintype "passive"))
      (node (ref "X6") (pin "1") (pinfunction "1_1") (pintype "passive"))
    )
    (net (code "122") (name "Net-(U10-IP-)") (class "Default")
      (node (ref "C25") (pin "2") (pinfunction "2_2") (pintype "passive"))
      (node (ref "C27") (pin "1") (pinfunction "1_1") (pintype "passive"))
      (node (ref "CR6") (pin "2") (pinfunction "2_2") (pintype "passive"))
      (node (ref "U10") (pin "4") (pinfunction "IP-_4") (pintype "passive"))
      (node (ref "U8") (pin "6") (pinfunction "Vs_6") (pintype "power_in"))
      (node (ref "VT11") (pin "2") (pinfunction "2_2") (pintype "passive"))
      (node (ref "VT9") (pin "3") (pinfunction "3_3") (pintype "passive"))
    )
    (net (code "123") (name "Net-(U10-VIOUT)") (class "Default")
      (node (ref "R16") (pin "1") (pinfunction "1_1") (pintype "passive"))
      (node (ref "U10") (pin "3") (pinfunction "VIOUT_3") (pintype "output"))
    )
    (net (code "124") (name "Net-(U11-IP+)") (class "Default")
      (node (ref "U11") (pin "5") (pinfunction "IP+_5") (pintype "passive"))
      (node (ref "X7") (pin "1") (pinfunction "1_1") (pintype "passive"))
    )
    (net (code "125") (name "Net-(U11-IP-)") (class "Default")
      (node (ref "C26") (pin "2") (pinfunction "2_2") (pintype "passive"))
      (node (ref "C28") (pin "1") (pinfunction "1_1") (pintype "passive"))
      (node (ref "CR7") (pin "2") (pinfunction "2_2") (pintype "passive"))
      (node (ref "U11") (pin "4") (pinfunction "IP-_4") (pintype "passive"))
      (node (ref "U9") (pin "6") (pinfunction "Vs_6") (pintype "power_in"))
      (node (ref "VT10") (pin "3") (pinfunction "3_3") (pintype "passive"))
      (node (ref "VT12") (pin "2") (pinfunction "2_2") (pintype "passive"))
    )
    (net (code "126") (name "Net-(U11-VIOUT)") (class "Default")
      (node (ref "R17") (pin "1") (pinfunction "1_1") (pintype "passive"))
      (node (ref "U11") (pin "3") (pinfunction "VIOUT_3") (pintype "output"))
    )
    (net (code "127") (name "Net-(U12-HO)") (class "Default")
      (node (ref "R18") (pin "2") (pinfunction "2_2") (pintype "passive"))
      (node (ref "U12") (pin "7") (pinfunction "HO_7") (pintype "output"))
    )
    (net (code "128") (name "Net-(U12-LO)") (class "Default")
      (node (ref "R21") (pin "2") (pinfunction "2_2") (pintype "passive"))
      (node (ref "U12") (pin "5") (pinfunction "LO_5") (pintype "output"))
    )
    (net (code "129") (name "Net-(U12-Vb)") (class "Default")
      (node (ref "C38") (pin "1") (pinfunction "1_1") (pintype "passive"))
      (node (ref "C40") (pin "2") (pinfunction "2_2") (pintype "passive"))
      (node (ref "CR8") (pin "1") (pinfunction "1_1") (pintype "passive"))
      (node (ref "U12") (pin "8") (pinfunction "Vb_8") (pintype "power_in"))
      (node (ref "VD8") (pin "1") (pinfunction "1_1") (pintype "passive"))
    )
    (net (code "130") (name "Net-(U12-Vs)") (class "Default")
      (node (ref "C38") (pin "2") (pinfunction "2_2") (pintype "passive"))
      (node (ref "C40") (pin "1") (pinfunction "1_1") (pintype "passive"))
      (node (ref "CR8") (pin "2") (pinfunction "2_2") (pintype "passive"))
      (node (ref "U12") (pin "6") (pinfunction "Vs_6") (pintype "power_in"))
      (node (ref "VT13") (pin "3") (pinfunction "3_3") (pintype "passive"))
      (node (ref "VT15") (pin "2") (pinfunction "2_2") (pintype "passive"))
      (node (ref "X6") (pin "2") (pinfunction "2_2") (pintype "passive"))
    )
    (net (code "131") (name "Net-(U13-HO)") (class "Default")
      (node (ref "R19") (pin "2") (pinfunction "2_2") (pintype "passive"))
      (node (ref "U13") (pin "7") (pinfunction "HO_7") (pintype "output"))
    )
    (net (code "132") (name "Net-(U13-LO)") (class "Default")
      (node (ref "R22") (pin "2") (pinfunction "2_2") (pintype "passive"))
      (node (ref "U13") (pin "5") (pinfunction "LO_5") (pintype "output"))
    )
    (net (code "133") (name "Net-(U13-Vb)") (class "Default")
      (node (ref "C39") (pin "1") (pinfunction "1_1") (pintype "passive"))
      (node (ref "C41") (pin "2") (pinfunction "2_2") (pintype "passive"))
      (node (ref "CR9") (pin "1") (pinfunction "1_1") (pintype "passive"))
      (node (ref "U13") (pin "8") (pinfunction "Vb_8") (pintype "power_in"))
      (node (ref "VD9") (pin "1") (pinfunction "1_1") (pintype "passive"))
    )
    (net (code "134") (name "Net-(U13-Vs)") (class "Default")
      (node (ref "C39") (pin "2") (pinfunction "2_2") (pintype "passive"))
      (node (ref "C41") (pin "1") (pinfunction "1_1") (pintype "passive"))
      (node (ref "CR9") (pin "2") (pinfunction "2_2") (pintype "passive"))
      (node (ref "U13") (pin "6") (pinfunction "Vs_6") (pintype "power_in"))
      (node (ref "VT14") (pin "3") (pinfunction "3_3") (pintype "passive"))
      (node (ref "VT16") (pin "2") (pinfunction "2_2") (pintype "passive"))
      (node (ref "X7") (pin "2") (pinfunction "2_2") (pintype "passive"))
    )
    (net (code "135") (name "Net-(U14-BOOT)") (class "Default")
      (node (ref "C42") (pin "2") (pinfunction "2_2") (pintype "passive"))
      (node (ref "U14") (pin "1") (pinfunction "BOOT_1") (pintype "output"))
    )
    (net (code "136") (name "Net-(U14-COMP)") (class "Default")
      (node (ref "C55") (pin "2") (pinfunction "2_2") (pintype "passive"))
      (node (ref "R24") (pin "1") (pinfunction "1_1") (pintype "passive"))
      (node (ref "U14") (pin "8") (pinfunction "COMP_8") (pintype "output"))
    )
    (net (code "137") (name "Net-(U14-RT{slash}CLK)") (class "Default")
      (node (ref "R25") (pin "1") (pinfunction "1_1") (pintype "passive"))
      (node (ref "U14") (pin "5") (pinfunction "RT/CLK_5") (pintype "input"))
    )
    (net (code "138") (name "Net-(U14-SS{slash}TR)") (class "Default")
      (node (ref "C51") (pin "1") (pinfunction "1_1") (pintype "passive"))
      (node (ref "U14") (pin "4") (pinfunction "SS/TR_4") (pintype "passive"))
    )
    (net (code "139") (name "Net-(U14-VSENSE)") (class "Default")
      (node (ref "R20") (pin "2") (pinfunction "2_2") (pintype "passive"))
      (node (ref "R23") (pin "1") (pinfunction "1_1") (pintype "passive"))
      (node (ref "U14") (pin "7") (pinfunction "VSENSE_7") (pintype "input"))
    )
    (net (code "140") (name "Net-(U15-HO)") (class "Default")
      (node (ref "R26") (pin "2") (pinfunction "2_2") (pintype "passive"))
      (node (ref "U15") (pin "7") (pinfunction "HO_7") (pintype "output"))
    )
    (net (code "141") (name "Net-(U15-LO)") (class "Default")
      (node (ref "R29") (pin "2") (pinfunction "2_2") (pintype "passive"))
      (node (ref "U15") (pin "5") (pinfunction "LO_5") (pintype "output"))
    )
    (net (code "142") (name "Net-(U15-Vb)") (class "Default")
      (node (ref "C57") (pin "1") (pinfunction "1_1") (pintype "passive"))
      (node (ref "C59") (pin "2") (pinfunction "2_2") (pintype "passive"))
      (node (ref "CR10") (pin "1") (pinfunction "1_1") (pintype "passive"))
      (node (ref "U15") (pin "8") (pinfunction "Vb_8") (pintype "power_in"))
      (node (ref "VD10") (pin "1") (pinfunction "1_1") (pintype "passive"))
    )
    (net (code "143") (name "Net-(U15-Vs)") (class "Default")
      (node (ref "C57") (pin "2") (pinfunction "2_2") (pintype "passive"))
      (node (ref "C59") (pin "1") (pinfunction "1_1") (pintype "passive"))
      (node (ref "CR10") (pin "2") (pinfunction "2_2") (pintype "passive"))
      (node (ref "U15") (pin "6") (pinfunction "Vs_6") (pintype "power_in"))
      (node (ref "U18") (pin "4") (pinfunction "IP-_4") (pintype "passive"))
      (node (ref "VT17") (pin "3") (pinfunction "3_3") (pintype "passive"))
      (node (ref "VT19") (pin "2") (pinfunction "2_2") (pintype "passive"))
    )
    (net (code "144") (name "Net-(U16-HO)") (class "Default")
      (node (ref "R27") (pin "2") (pinfunction "2_2") (pintype "passive"))
      (node (ref "U16") (pin "7") (pinfunction "HO_7") (pintype "output"))
    )
    (net (code "145") (name "Net-(U16-LO)") (class "Default")
      (node (ref "R30") (pin "2") (pinfunction "2_2") (pintype "passive"))
      (node (ref "U16") (pin "5") (pinfunction "LO_5") (pintype "output"))
    )
    (net (code "146") (name "Net-(U16-Vb)") (class "Default")
      (node (ref "C58") (pin "1") (pinfunction "1_1") (pintype "passive"))
      (node (ref "C60") (pin "2") (pinfunction "2_2") (pintype "passive"))
      (node (ref "CR11") (pin "1") (pinfunction "1_1") (pintype "passive"))
      (node (ref "U16") (pin "8") (pinfunction "Vb_8") (pintype "power_in"))
      (node (ref "VD11") (pin "1") (pinfunction "1_1") (pintype "passive"))
    )
    (net (code "147") (name "Net-(U16-Vs)") (class "Default")
      (node (ref "C58") (pin "2") (pinfunction "2_2") (pintype "passive"))
      (node (ref "C60") (pin "1") (pinfunction "1_1") (pintype "passive"))
      (node (ref "CR11") (pin "2") (pinfunction "2_2") (pintype "passive"))
      (node (ref "U16") (pin "6") (pinfunction "Vs_6") (pintype "power_in"))
      (node (ref "U19") (pin "4") (pinfunction "IP-_4") (pintype "passive"))
      (node (ref "VT18") (pin "3") (pinfunction "3_3") (pintype "passive"))
      (node (ref "VT20") (pin "2") (pinfunction "2_2") (pintype "passive"))
    )
    (net (code "148") (name "Net-(U17-BOOT)") (class "Default")
      (node (ref "C67") (pin "2") (pinfunction "2_2") (pintype "passive"))
      (node (ref "U17") (pin "1") (pinfunction "BOOT_1") (pintype "output"))
    )
    (net (code "149") (name "Net-(U17-COMP)") (class "Default")
      (node (ref "C76") (pin "2") (pinfunction "2_2") (pintype "passive"))
      (node (ref "R34") (pin "1") (pinfunction "1_1") (pintype "passive"))
      (node (ref "U17") (pin "8") (pinfunction "COMP_8") (pintype "output"))
    )
    (net (code "150") (name "Net-(U17-RT{slash}CLK)") (class "Default")
      (node (ref "R35") (pin "1") (pinfunction "1_1") (pintype "passive"))
      (node (ref "U17") (pin "5") (pinfunction "RT/CLK_5") (pintype "input"))
    )
    (net (code "151") (name "Net-(U17-SS{slash}TR)") (class "Default")
      (node (ref "C70") (pin "1") (pinfunction "1_1") (pintype "passive"))
      (node (ref "U17") (pin "4") (pinfunction "SS/TR_4") (pintype "passive"))
    )
    (net (code "152") (name "Net-(U17-VSENSE)") (class "Default")
      (node (ref "R28") (pin "2") (pinfunction "2_2") (pintype "passive"))
      (node (ref "R31") (pin "1") (pinfunction "1_1") (pintype "passive"))
      (node (ref "U17") (pin "7") (pinfunction "VSENSE_7") (pintype "input"))
    )
    (net (code "153") (name "Net-(U18-IP+)") (class "Default")
      (node (ref "U18") (pin "5") (pinfunction "IP+_5") (pintype "passive"))
      (node (ref "X8") (pin "1") (pinfunction "1_1") (pintype "passive"))
    )
    (net (code "154") (name "Net-(U18-VIOUT)") (class "Default")
      (node (ref "R32") (pin "1") (pinfunction "1_1") (pintype "passive"))
      (node (ref "U18") (pin "3") (pinfunction "VIOUT_3") (pintype "output"))
    )
    (net (code "155") (name "Net-(U19-IP+)") (class "Default")
      (node (ref "U19") (pin "5") (pinfunction "IP+_5") (pintype "passive"))
      (node (ref "X9") (pin "1") (pinfunction "1_1") (pintype "passive"))
    )
    (net (code "156") (name "Net-(U19-VIOUT)") (class "Default")
      (node (ref "R33") (pin "1") (pinfunction "1_1") (pintype "passive"))
      (node (ref "U19") (pin "3") (pinfunction "VIOUT_3") (pintype "output"))
    )
    (net (code "157") (name "Net-(U20-HO)") (class "Default")
      (node (ref "R36") (pin "2") (pinfunction "2_2") (pintype "passive"))
      (node (ref "U20") (pin "7") (pinfunction "HO_7") (pintype "output"))
    )
    (net (code "158") (name "Net-(U20-LO)") (class "Default")
      (node (ref "R38") (pin "2") (pinfunction "2_2") (pintype "passive"))
      (node (ref "U20") (pin "5") (pinfunction "LO_5") (pintype "output"))
    )
    (net (code "159") (name "Net-(U20-Vb)") (class "Default")
      (node (ref "C77") (pin "1") (pinfunction "1_1") (pintype "passive"))
      (node (ref "C79") (pin "2") (pinfunction "2_2") (pintype "passive"))
      (node (ref "CR12") (pin "1") (pinfunction "1_1") (pintype "passive"))
      (node (ref "U20") (pin "8") (pinfunction "Vb_8") (pintype "power_in"))
      (node (ref "VD12") (pin "1") (pinfunction "1_1") (pintype "passive"))
    )
    (net (code "160") (name "Net-(U20-Vs)") (class "Default")
      (node (ref "C77") (pin "2") (pinfunction "2_2") (pintype "passive"))
      (node (ref "C79") (pin "1") (pinfunction "1_1") (pintype "passive"))
      (node (ref "CR12") (pin "2") (pinfunction "2_2") (pintype "passive"))
      (node (ref "U20") (pin "6") (pinfunction "Vs_6") (pintype "power_in"))
      (node (ref "VT21") (pin "3") (pinfunction "3_3") (pintype "passive"))
      (node (ref "VT23") (pin "2") (pinfunction "2_2") (pintype "passive"))
      (node (ref "X8") (pin "2") (pinfunction "2_2") (pintype "passive"))
    )
    (net (code "161") (name "Net-(U21-HO)") (class "Default")
      (node (ref "R37") (pin "2") (pinfunction "2_2") (pintype "passive"))
      (node (ref "U21") (pin "7") (pinfunction "HO_7") (pintype "output"))
    )
    (net (code "162") (name "Net-(U21-LO)") (class "Default")
      (node (ref "R39") (pin "2") (pinfunction "2_2") (pintype "passive"))
      (node (ref "U21") (pin "5") (pinfunction "LO_5") (pintype "output"))
    )
    (net (code "163") (name "Net-(U21-Vb)") (class "Default")
      (node (ref "C78") (pin "1") (pinfunction "1_1") (pintype "passive"))
      (node (ref "C80") (pin "2") (pinfunction "2_2") (pintype "passive"))
      (node (ref "CR13") (pin "1") (pinfunction "1_1") (pintype "passive"))
      (node (ref "U21") (pin "8") (pinfunction "Vb_8") (pintype "power_in"))
      (node (ref "VD13") (pin "1") (pinfunction "1_1") (pintype "passive"))
    )
    (net (code "164") (name "Net-(U21-Vs)") (class "Default")
      (node (ref "C78") (pin "2") (pinfunction "2_2") (pintype "passive"))
      (node (ref "C80") (pin "1") (pinfunction "1_1") (pintype "passive"))
      (node (ref "CR13") (pin "2") (pinfunction "2_2") (pintype "passive"))
      (node (ref "U21") (pin "6") (pinfunction "Vs_6") (pintype "power_in"))
      (node (ref "VT22") (pin "3") (pinfunction "3_3") (pintype "passive"))
      (node (ref "VT24") (pin "2") (pinfunction "2_2") (pintype "passive"))
      (node (ref "X9") (pin "2") (pinfunction "2_2") (pintype "passive"))
    )
    (net (code "165") (name "Net-(U22-BOOT)") (class "Default")
      (node (ref "C88") (pin "2") (pinfunction "2_2") (pintype "passive"))
      (node (ref "U22") (pin "1") (pinfunction "BOOT_1") (pintype "output"))
    )
    (net (code "166") (name "Net-(U22-COMP)") (class "Default")
      (node (ref "C95") (pin "2") (pinfunction "2_2") (pintype "passive"))
      (node (ref "R42") (pin "1") (pinfunction "1_1") (pintype "passive"))
      (node (ref "U22") (pin "8") (pinfunction "COMP_8") (pintype "output"))
    )
    (net (code "167") (name "Net-(U22-RT{slash}CLK)") (class "Default")
      (node (ref "R43") (pin "1") (pinfunction "1_1") (pintype "passive"))
      (node (ref "U22") (pin "5") (pinfunction "RT/CLK_5") (pintype "input"))
    )
    (net (code "168") (name "Net-(U22-SS{slash}TR)") (class "Default")
      (node (ref "C91") (pin "1") (pinfunction "1_1") (pintype "passive"))
      (node (ref "U22") (pin "4") (pinfunction "SS/TR_4") (pintype "passive"))
    )
    (net (code "169") (name "Net-(U22-VSENSE)") (class "Default")
      (node (ref "R40") (pin "2") (pinfunction "2_2") (pintype "passive"))
      (node (ref "R41") (pin "1") (pinfunction "1_1") (pintype "passive"))
      (node (ref "U22") (pin "7") (pinfunction "VSENSE_7") (pintype "input"))
    )
    (net (code "170") (name "Net-(U23-HO)") (class "Default")
      (node (ref "R44") (pin "2") (pinfunction "2_2") (pintype "passive"))
      (node (ref "U23") (pin "7") (pinfunction "HO_7") (pintype "output"))
    )
    (net (code "171") (name "Net-(U23-LO)") (class "Default")
      (node (ref "R46") (pin "2") (pinfunction "2_2") (pintype "passive"))
      (node (ref "U23") (pin "5") (pinfunction "LO_5") (pintype "output"))
    )
    (net (code "172") (name "Net-(U23-Vb)") (class "Default")
      (node (ref "C96") (pin "1") (pinfunction "1_1") (pintype "passive"))
      (node (ref "C98") (pin "2") (pinfunction "2_2") (pintype "passive"))
      (node (ref "CR14") (pin "1") (pinfunction "1_1") (pintype "passive"))
      (node (ref "U23") (pin "8") (pinfunction "Vb_8") (pintype "power_in"))
      (node (ref "VD14") (pin "1") (pinfunction "1_1") (pintype "passive"))
    )
    (net (code "173") (name "Net-(U23-Vs)") (class "Default")
      (node (ref "C96") (pin "2") (pinfunction "2_2") (pintype "passive"))
      (node (ref "C98") (pin "1") (pinfunction "1_1") (pintype "passive"))
      (node (ref "CR14") (pin "2") (pinfunction "2_2") (pintype "passive"))
      (node (ref "U23") (pin "6") (pinfunction "Vs_6") (pintype "power_in"))
      (node (ref "U25") (pin "4") (pinfunction "IP-_4") (pintype "passive"))
      (node (ref "VT25") (pin "3") (pinfunction "3_3") (pintype "passive"))
      (node (ref "VT27") (pin "2") (pinfunction "2_2") (pintype "passive"))
    )
    (net (code "174") (name "Net-(U24-HO)") (class "Default")
      (node (ref "R45") (pin "2") (pinfunction "2_2") (pintype "passive"))
      (node (ref "U24") (pin "7") (pinfunction "HO_7") (pintype "output"))
    )
    (net (code "175") (name "Net-(U24-LO)") (class "Default")
      (node (ref "R47") (pin "2") (pinfunction "2_2") (pintype "passive"))
      (node (ref "U24") (pin "5") (pinfunction "LO_5") (pintype "output"))
    )
    (net (code "176") (name "Net-(U24-Vb)") (class "Default")
      (node (ref "C97") (pin "1") (pinfunction "1_1") (pintype "passive"))
      (node (ref "C99") (pin "2") (pinfunction "2_2") (pintype "passive"))
      (node (ref "CR15") (pin "1") (pinfunction "1_1") (pintype "passive"))
      (node (ref "U24") (pin "8") (pinfunction "Vb_8") (pintype "power_in"))
      (node (ref "VD15") (pin "1") (pinfunction "1_1") (pintype "passive"))
    )
    (net (code "177") (name "Net-(U24-Vs)") (class "Default")
      (node (ref "C97") (pin "2") (pinfunction "2_2") (pintype "passive"))
      (node (ref "C99") (pin "1") (pinfunction "1_1") (pintype "passive"))
      (node (ref "CR15") (pin "2") (pinfunction "2_2") (pintype "passive"))
      (node (ref "U24") (pin "6") (pinfunction "Vs_6") (pintype "power_in"))
      (node (ref "U26") (pin "4") (pinfunction "IP-_4") (pintype "passive"))
      (node (ref "VT26") (pin "3") (pinfunction "3_3") (pintype "passive"))
      (node (ref "VT28") (pin "2") (pinfunction "2_2") (pintype "passive"))
    )
    (net (code "178") (name "Net-(U25-IP+)") (class "Default")
      (node (ref "U25") (pin "5") (pinfunction "IP+_5") (pintype "passive"))
      (node (ref "X10") (pin "1") (pinfunction "1_1") (pintype "passive"))
    )
    (net (code "179") (name "Net-(U25-VIOUT)") (class "Default")
      (node (ref "R48") (pin "1") (pinfunction "1_1") (pintype "passive"))
      (node (ref "U25") (pin "3") (pinfunction "VIOUT_3") (pintype "output"))
    )
    (net (code "180") (name "Net-(U26-IP+)") (class "Default")
      (node (ref "U26") (pin "5") (pinfunction "IP+_5") (pintype "passive"))
      (node (ref "X11") (pin "1") (pinfunction "1_1") (pintype "passive"))
    )
    (net (code "181") (name "Net-(U26-VIOUT)") (class "Default")
      (node (ref "R49") (pin "1") (pinfunction "1_1") (pintype "passive"))
      (node (ref "U26") (pin "3") (pinfunction "VIOUT_3") (pintype "output"))
    )
    (net (code "182") (name "Net-(U27-HO)") (class "Default")
      (node (ref "R50") (pin "2") (pinfunction "2_2") (pintype "passive"))
      (node (ref "U27") (pin "7") (pinfunction "HO_7") (pintype "output"))
    )
    (net (code "183") (name "Net-(U27-LO)") (class "Default")
      (node (ref "R52") (pin "2") (pinfunction "2_2") (pintype "passive"))
      (node (ref "U27") (pin "5") (pinfunction "LO_5") (pintype "output"))
    )
    (net (code "184") (name "Net-(U27-Vb)") (class "Default")
      (node (ref "C109") (pin "1") (pinfunction "1_1") (pintype "passive"))
      (node (ref "C111") (pin "2") (pinfunction "2_2") (pintype "passive"))
      (node (ref "CR16") (pin "1") (pinfunction "1_1") (pintype "passive"))
      (node (ref "U27") (pin "8") (pinfunction "Vb_8") (pintype "power_in"))
      (node (ref "VD16") (pin "1") (pinfunction "1_1") (pintype "passive"))
    )
    (net (code "185") (name "Net-(U27-Vs)") (class "Default")
      (node (ref "C109") (pin "2") (pinfunction "2_2") (pintype "passive"))
      (node (ref "C111") (pin "1") (pinfunction "1_1") (pintype "passive"))
      (node (ref "CR16") (pin "2") (pinfunction "2_2") (pintype "passive"))
      (node (ref "U27") (pin "6") (pinfunction "Vs_6") (pintype "power_in"))
      (node (ref "VT29") (pin "3") (pinfunction "3_3") (pintype "passive"))
      (node (ref "VT31") (pin "2") (pinfunction "2_2") (pintype "passive"))
      (node (ref "X10") (pin "2") (pinfunction "2_2") (pintype "passive"))
    )
    (net (code "186") (name "Net-(U28-HO)") (class "Default")
      (node (ref "R51") (pin "2") (pinfunction "2_2") (pintype "passive"))
      (node (ref "U28") (pin "7") (pinfunction "HO_7") (pintype "output"))
    )
    (net (code "187") (name "Net-(U28-LO)") (class "Default")
      (node (ref "R53") (pin "2") (pinfunction "2_2") (pintype "passive"))
      (node (ref "U28") (pin "5") (pinfunction "LO_5") (pintype "output"))
    )
    (net (code "188") (name "Net-(U28-Vb)") (class "Default")
      (node (ref "C110") (pin "1") (pinfunction "1_1") (pintype "passive"))
      (node (ref "C112") (pin "2") (pinfunction "2_2") (pintype "passive"))
      (node (ref "CR17") (pin "1") (pinfunction "1_1") (pintype "passive"))
      (node (ref "U28") (pin "8") (pinfunction "Vb_8") (pintype "power_in"))
      (node (ref "VD17") (pin "1") (pinfunction "1_1") (pintype "passive"))
    )
    (net (code "189") (name "Net-(U28-Vs)") (class "Default")
      (node (ref "C110") (pin "2") (pinfunction "2_2") (pintype "passive"))
      (node (ref "C112") (pin "1") (pinfunction "1_1") (pintype "passive"))
      (node (ref "CR17") (pin "2") (pinfunction "2_2") (pintype "passive"))
      (node (ref "U28") (pin "6") (pinfunction "Vs_6") (pintype "power_in"))
      (node (ref "VT30") (pin "3") (pinfunction "3_3") (pintype "passive"))
      (node (ref "VT32") (pin "2") (pinfunction "2_2") (pintype "passive"))
      (node (ref "X11") (pin "2") (pinfunction "2_2") (pintype "passive"))
    )
    (net (code "190") (name "Net-(VT33-2)") (class "Default")
      (node (ref "U29") (pin "1") (pinfunction "1_1") (pintype "passive"))
      (node (ref "VD7") (pin "2") (pinfunction "2_2") (pintype "passive"))
      (node (ref "VT33") (pin "3") (pinfunction "2_3") (pintype "passive"))
    )
    (net (code "191") (name "unconnected-(J1-3V3-Pad1)") (class "Default")
      (node (ref "J1") (pin "1") (pinfunction "3V3_1") (pintype "bidirectional"))
    )
    (net (code "192") (name "unconnected-(J1-EN-Pad16)") (class "Default")
      (node (ref "J1") (pin "16") (pinfunction "EN_16") (pintype "bidirectional"))
    )
    (net (code "193") (name "unconnected-(J1-GND-Pad2)") (class "Default")
      (node (ref "J1") (pin "2") (pinfunction "GND_2") (pintype "bidirectional"))
    )
    (net (code "194") (name "unconnected-(J1-IO1-Pad13)") (class "Default")
      (node (ref "J1") (pin "13") (pinfunction "IO1_13") (pintype "bidirectional"))
    )
    (net (code "195") (name "unconnected-(J1-IO2-Pad4)") (class "Default")
      (node (ref "J1") (pin "4") (pinfunction "IO2_4") (pintype "bidirectional"))
    )
    (net (code "196") (name "unconnected-(J1-IO3-Pad12)") (class "Default")
      (node (ref "J1") (pin "12") (pinfunction "IO3_12") (pintype "bidirectional"))
    )
    (net (code "197") (name "unconnected-(J1-IO4-Pad5)") (class "Default")
      (node (ref "J1") (pin "5") (pinfunction "IO4_5") (pintype "bidirectional"))
    )
    (net (code "198") (name "unconnected-(J1-IO5-Pad8)") (class "Default")
      (node (ref "J1") (pin "8") (pinfunction "IO5_8") (pintype "bidirectional"))
    )
    (net (code "199") (name "unconnected-(J1-IO12-Pad27)") (class "Default")
      (node (ref "J1") (pin "27") (pinfunction "IO12_27") (pintype "bidirectional"))
    )
    (net (code "200") (name "unconnected-(J1-IO13-Pad28)") (class "Default")
      (node (ref "J1") (pin "28") (pinfunction "IO13_28") (pintype "bidirectional"))
    )
    (net (code "201") (name "unconnected-(J1-IO14-Pad26)") (class "Default")
      (node (ref "J1") (pin "26") (pinfunction "IO14_26") (pintype "bidirectional"))
    )
    (net (code "202") (name "unconnected-(J1-IO15-Pad3)") (class "Default")
      (node (ref "J1") (pin "3") (pinfunction "IO15_3") (pintype "bidirectional"))
    )
    (net (code "203") (name "unconnected-(J1-IO18-Pad9)") (class "Default")
      (node (ref "J1") (pin "9") (pinfunction "IO18_9") (pintype "bidirectional"))
    )
    (net (code "204") (name "unconnected-(J1-IO19-Pad10)") (class "Default")
      (node (ref "J1") (pin "10") (pinfunction "IO19_10") (pintype "bidirectional"))
    )
    (net (code "205") (name "unconnected-(J1-IO21-Pad11)") (class "Default")
      (node (ref "J1") (pin "11") (pinfunction "IO21_11") (pintype "bidirectional"))
    )
    (net (code "206") (name "unconnected-(J1-IO22-Pad14)") (class "Default")
      (node (ref "J1") (pin "14") (pinfunction "IO22_14") (pintype "bidirectional"))
    )
    (net (code "207") (name "unconnected-(J1-IO23-Pad15)") (class "Default")
      (node (ref "J1") (pin "15") (pinfunction "IO23_15") (pintype "bidirectional"))
    )
    (net (code "208") (name "unconnected-(J1-IO25-Pad23)") (class "Default")
      (node (ref "J1") (pin "23") (pinfunction "IO25_23") (pintype "bidirectional"))
    )
    (net (code "209") (name "unconnected-(J1-IO26-Pad24)") (class "Default")
      (node (ref "J1") (pin "24") (pinfunction "IO26_24") (pintype "bidirectional"))
    )
    (net (code "210") (name "unconnected-(J1-IO27-Pad25)") (class "Default")
      (node (ref "J1") (pin "25") (pinfunction "IO27_25") (pintype "bidirectional"))
    )
    (net (code "211") (name "unconnected-(J1-IO32-Pad21)") (class "Default")
      (node (ref "J1") (pin "21") (pinfunction "IO32_21") (pintype "bidirectional"))
    )
    (net (code "212") (name "unconnected-(J1-IO33-Pad22)") (class "Default")
      (node (ref "J1") (pin "22") (pinfunction "IO33_22") (pintype "bidirectional"))
    )
    (net (code "213") (name "unconnected-(J1-IO34-Pad19)") (class "Default")
      (node (ref "J1") (pin "19") (pinfunction "IO34_19") (pintype "bidirectional"))
    )
    (net (code "214") (name "unconnected-(J1-IO35-Pad20)") (class "Default")
      (node (ref "J1") (pin "20") (pinfunction "IO35_20") (pintype "bidirectional"))
    )
    (net (code "215") (name "unconnected-(J1-VN-Pad18)") (class "Default")
      (node (ref "J1") (pin "18") (pinfunction "VN_18") (pintype "bidirectional"))
    )
    (net (code "216") (name "unconnected-(J1-VP-Pad17)") (class "Default")
      (node (ref "J1") (pin "17") (pinfunction "VP_17") (pintype "bidirectional"))
    )
    (net (code "217") (name "unconnected-(TB1-3V-PadP2_5)") (class "Default")
      (node (ref "TB1") (pin "P2_5") (pinfunction "3V_P2_5") (pintype "power_in"))
    )
    (net (code "218") (name "unconnected-(TB1-3V-PadP2_6)") (class "Default")
      (node (ref "TB1") (pin "P2_6") (pinfunction "3V_P2_6") (pintype "power_in"))
    )
    (net (code "219") (name "unconnected-(TB1-BOOT0-PadP2_21)") (class "Default")
      (node (ref "TB1") (pin "P2_21") (pinfunction "BOOT0_P2_21") (pintype "input"))
    )
    (net (code "220") (name "unconnected-(TB1-NRST-PadP1_6)") (class "Default")
      (node (ref "TB1") (pin "P1_6") (pinfunction "NRST_P1_6") (pintype "input"))
    )
    (net (code "221") (name "unconnected-(TB1-PA8-PadP2_43)") (class "Default")
      (node (ref "TB1") (pin "P2_43") (pinfunction "PA8_P2_43") (pintype "bidirectional"))
    )
    (net (code "222") (name "unconnected-(TB1-PA9-PadP2_44)") (class "Default")
      (node (ref "TB1") (pin "P2_44") (pinfunction "PA9_P2_44") (pintype "bidirectional"))
    )
    (net (code "223") (name "unconnected-(TB1-PA10-PadP2_41)") (class "Default")
      (node (ref "TB1") (pin "P2_41") (pinfunction "PA10_P2_41") (pintype "bidirectional"))
    )
    (net (code "224") (name "unconnected-(TB1-PA13-PadP2_42)") (class "Default")
      (node (ref "TB1") (pin "P2_42") (pinfunction "PA13_P2_42") (pintype "bidirectional"))
    )
    (net (code "225") (name "unconnected-(TB1-PA14-PadP2_39)") (class "Default")
      (node (ref "TB1") (pin "P2_39") (pinfunction "PA14_P2_39") (pintype "bidirectional"))
    )
    (net (code "226") (name "unconnected-(TB1-PA15-PadP2_40)") (class "Default")
      (node (ref "TB1") (pin "P2_40") (pinfunction "PA15_P2_40") (pintype "bidirectional"))
    )
    (net (code "227") (name "unconnected-(TB1-PB2-PadP1_24)") (class "Default")
      (node (ref "TB1") (pin "P1_24") (pinfunction "PB2_P1_24") (pintype "bidirectional"))
    )
    (net (code "228") (name "unconnected-(TB1-PB3-PadP2_28)") (class "Default")
      (node (ref "TB1") (pin "P2_28") (pinfunction "PB3_P2_28") (pintype "bidirectional"))
    )
    (net (code "229") (name "unconnected-(TB1-PB4-PadP2_25)") (class "Default")
      (node (ref "TB1") (pin "P2_25") (pinfunction "PB4_P2_25") (pintype "bidirectional"))
    )
    (net (code "230") (name "unconnected-(TB1-PB6-PadP2_23)") (class "Default")
      (node (ref "TB1") (pin "P2_23") (pinfunction "PB6_P2_23") (pintype "bidirectional"))
    )
    (net (code "231") (name "unconnected-(TB1-PB7-PadP2_24)") (class "Default")
      (node (ref "TB1") (pin "P2_24") (pinfunction "PB7_P2_24") (pintype "bidirectional"))
    )
    (net (code "232") (name "unconnected-(TB1-PB8-PadP2_19)") (class "Default")
      (node (ref "TB1") (pin "P2_19") (pinfunction "PB8_P2_19") (pintype "bidirectional"))
    )
    (net (code "233") (name "unconnected-(TB1-PB9-PadP2_20)") (class "Default")
      (node (ref "TB1") (pin "P2_20") (pinfunction "PB9_P2_20") (pintype "bidirectional"))
    )
    (net (code "234") (name "unconnected-(TB1-PB10-PadP1_34)") (class "Default")
      (node (ref "TB1") (pin "P1_34") (pinfunction "PB10_P1_34") (pintype "bidirectional"))
    )
    (net (code "235") (name "unconnected-(TB1-PB11-PadP1_35)") (class "Default")
      (node (ref "TB1") (pin "P1_35") (pinfunction "PB11_P1_35") (pintype "bidirectional"))
    )
    (net (code "236") (name "unconnected-(TB1-PB15-PadP1_39)") (class "Default")
      (node (ref "TB1") (pin "P1_39") (pinfunction "PB15_P1_39") (pintype "bidirectional"))
    )
    (net (code "237") (name "unconnected-(TB1-PC10-PadP2_37)") (class "Default")
      (node (ref "TB1") (pin "P2_37") (pinfunction "PC10_P2_37") (pintype "bidirectional"))
    )
    (net (code "238") (name "unconnected-(TB1-PC11-PadP2_38)") (class "Default")
      (node (ref "TB1") (pin "P2_38") (pinfunction "PC11_P2_38") (pintype "bidirectional"))
    )
    (net (code "239") (name "unconnected-(TB1-PC12-PadP2_35)") (class "Default")
      (node (ref "TB1") (pin "P2_35") (pinfunction "PC12_P2_35") (pintype "bidirectional"))
    )
    (net (code "240") (name "unconnected-(TB1-PC13-PadP2_12)") (class "Default")
      (node (ref "TB1") (pin "P2_12") (pinfunction "PC13_P2_12") (pintype "bidirectional"))
    )
    (net (code "241") (name "unconnected-(TB1-PC14-PadP2_9)") (class "Default")
      (node (ref "TB1") (pin "P2_9") (pinfunction "PC14_P2_9") (pintype "bidirectional"))
    )
    (net (code "242") (name "unconnected-(TB1-PC15-PadP2_10)") (class "Default")
      (node (ref "TB1") (pin "P2_10") (pinfunction "PC15_P2_10") (pintype "bidirectional"))
    )
    (net (code "243") (name "unconnected-(TB1-PD3-PadP2_31)") (class "Default")
      (node (ref "TB1") (pin "P2_31") (pinfunction "PD3_P2_31") (pintype "bidirectional"))
    )
    (net (code "244") (name "unconnected-(TB1-PD4-PadP2_32)") (class "Default")
      (node (ref "TB1") (pin "P2_32") (pinfunction "PD4_P2_32") (pintype "bidirectional"))
    )
    (net (code "245") (name "unconnected-(TB1-PD12-PadP1_44)") (class "Default")
      (node (ref "TB1") (pin "P1_44") (pinfunction "PD12_P1_44") (pintype "bidirectional"))
    )
    (net (code "246") (name "unconnected-(TB1-PD13-PadP1_45)") (class "Default")
      (node (ref "TB1") (pin "P1_45") (pinfunction "PD13_P1_45") (pintype "bidirectional"))
    )
    (net (code "247") (name "unconnected-(TB1-PD14-PadP1_46)") (class "Default")
      (node (ref "TB1") (pin "P1_46") (pinfunction "PD14_P1_46") (pintype "bidirectional"))
    )
    (net (code "248") (name "unconnected-(TB1-PE8-PadP1_26)") (class "Default")
      (node (ref "TB1") (pin "P1_26") (pinfunction "PE8_P1_26") (pintype "bidirectional"))
    )
    (net (code "249") (name "unconnected-(TB1-PE10-PadP1_28)") (class "Default")
      (node (ref "TB1") (pin "P1_28") (pinfunction "PE10_P1_28") (pintype "bidirectional"))
    )
    (net (code "250") (name "unconnected-(TB1-PE12-PadP1_30)") (class "Default")
      (node (ref "TB1") (pin "P1_30") (pinfunction "PE12_P1_30") (pintype "bidirectional"))
    )
    (net (code "251") (name "unconnected-(TB1-PE15-PadP1_33)") (class "Default")
      (node (ref "TB1") (pin "P1_33") (pinfunction "PE15_P1_33") (pintype "bidirectional"))
    )
    (net (code "252") (name "unconnected-(TB1-PH0-PadP2_7)") (class "Default")
      (node (ref "TB1") (pin "P2_7") (pinfunction "PH0_P2_7") (pintype "bidirectional"))
    )
    (net (code "253") (name "unconnected-(TB1-PH1-PadP2_8)") (class "Default")
      (node (ref "TB1") (pin "P2_8") (pinfunction "PH1_P2_8") (pintype "bidirectional"))
    )
    (net (code "254") (name "unconnected-(TB1-VDD-PadP1_3)") (class "Default")
      (node (ref "TB1") (pin "P1_3") (pinfunction "VDD_P1_3") (pintype "power_in"))
    )
    (net (code "255") (name "unconnected-(TB1-VDD-PadP1_4)") (class "Default")
      (node (ref "TB1") (pin "P1_4") (pinfunction "VDD_P1_4") (pintype "power_in"))
    )
    (net (code "256") (name "unconnected-(TB1-VDD-PadP2_22)") (class "Default")
      (node (ref "TB1") (pin "P2_22") (pinfunction "VDD_P2_22") (pintype "power_in"))
    )
    (net (code "257") (name "unconnected-(U14-EN-Pad3)") (class "Default")
      (node (ref "U14") (pin "3") (pinfunction "EN_3") (pintype "input"))
    )
    (net (code "258") (name "unconnected-(U14-PWRGD-Pad6)") (class "Default")
      (node (ref "U14") (pin "6") (pinfunction "PWRGD_6") (pintype "output"))
    )
    (net (code "259") (name "unconnected-(U17-EN-Pad3)") (class "Default")
      (node (ref "U17") (pin "3") (pinfunction "EN_3") (pintype "input"))
    )
    (net (code "260") (name "unconnected-(U17-PWRGD-Pad6)") (class "Default")
      (node (ref "U17") (pin "6") (pinfunction "PWRGD_6") (pintype "output"))
    )
    (net (code "261") (name "unconnected-(U22-EN-Pad3)") (class "Default")
      (node (ref "U22") (pin "3") (pinfunction "EN_3") (pintype "input"))
    )
    (net (code "262") (name "unconnected-(U22-PWRGD-Pad6)") (class "Default")
      (node (ref "U22") (pin "6") (pinfunction "PWRGD_6") (pintype "output"))
    )
  )
)
